# UCirKitBreadboardTop.net
KiCad netlist of a schematic drawn in EAGLE
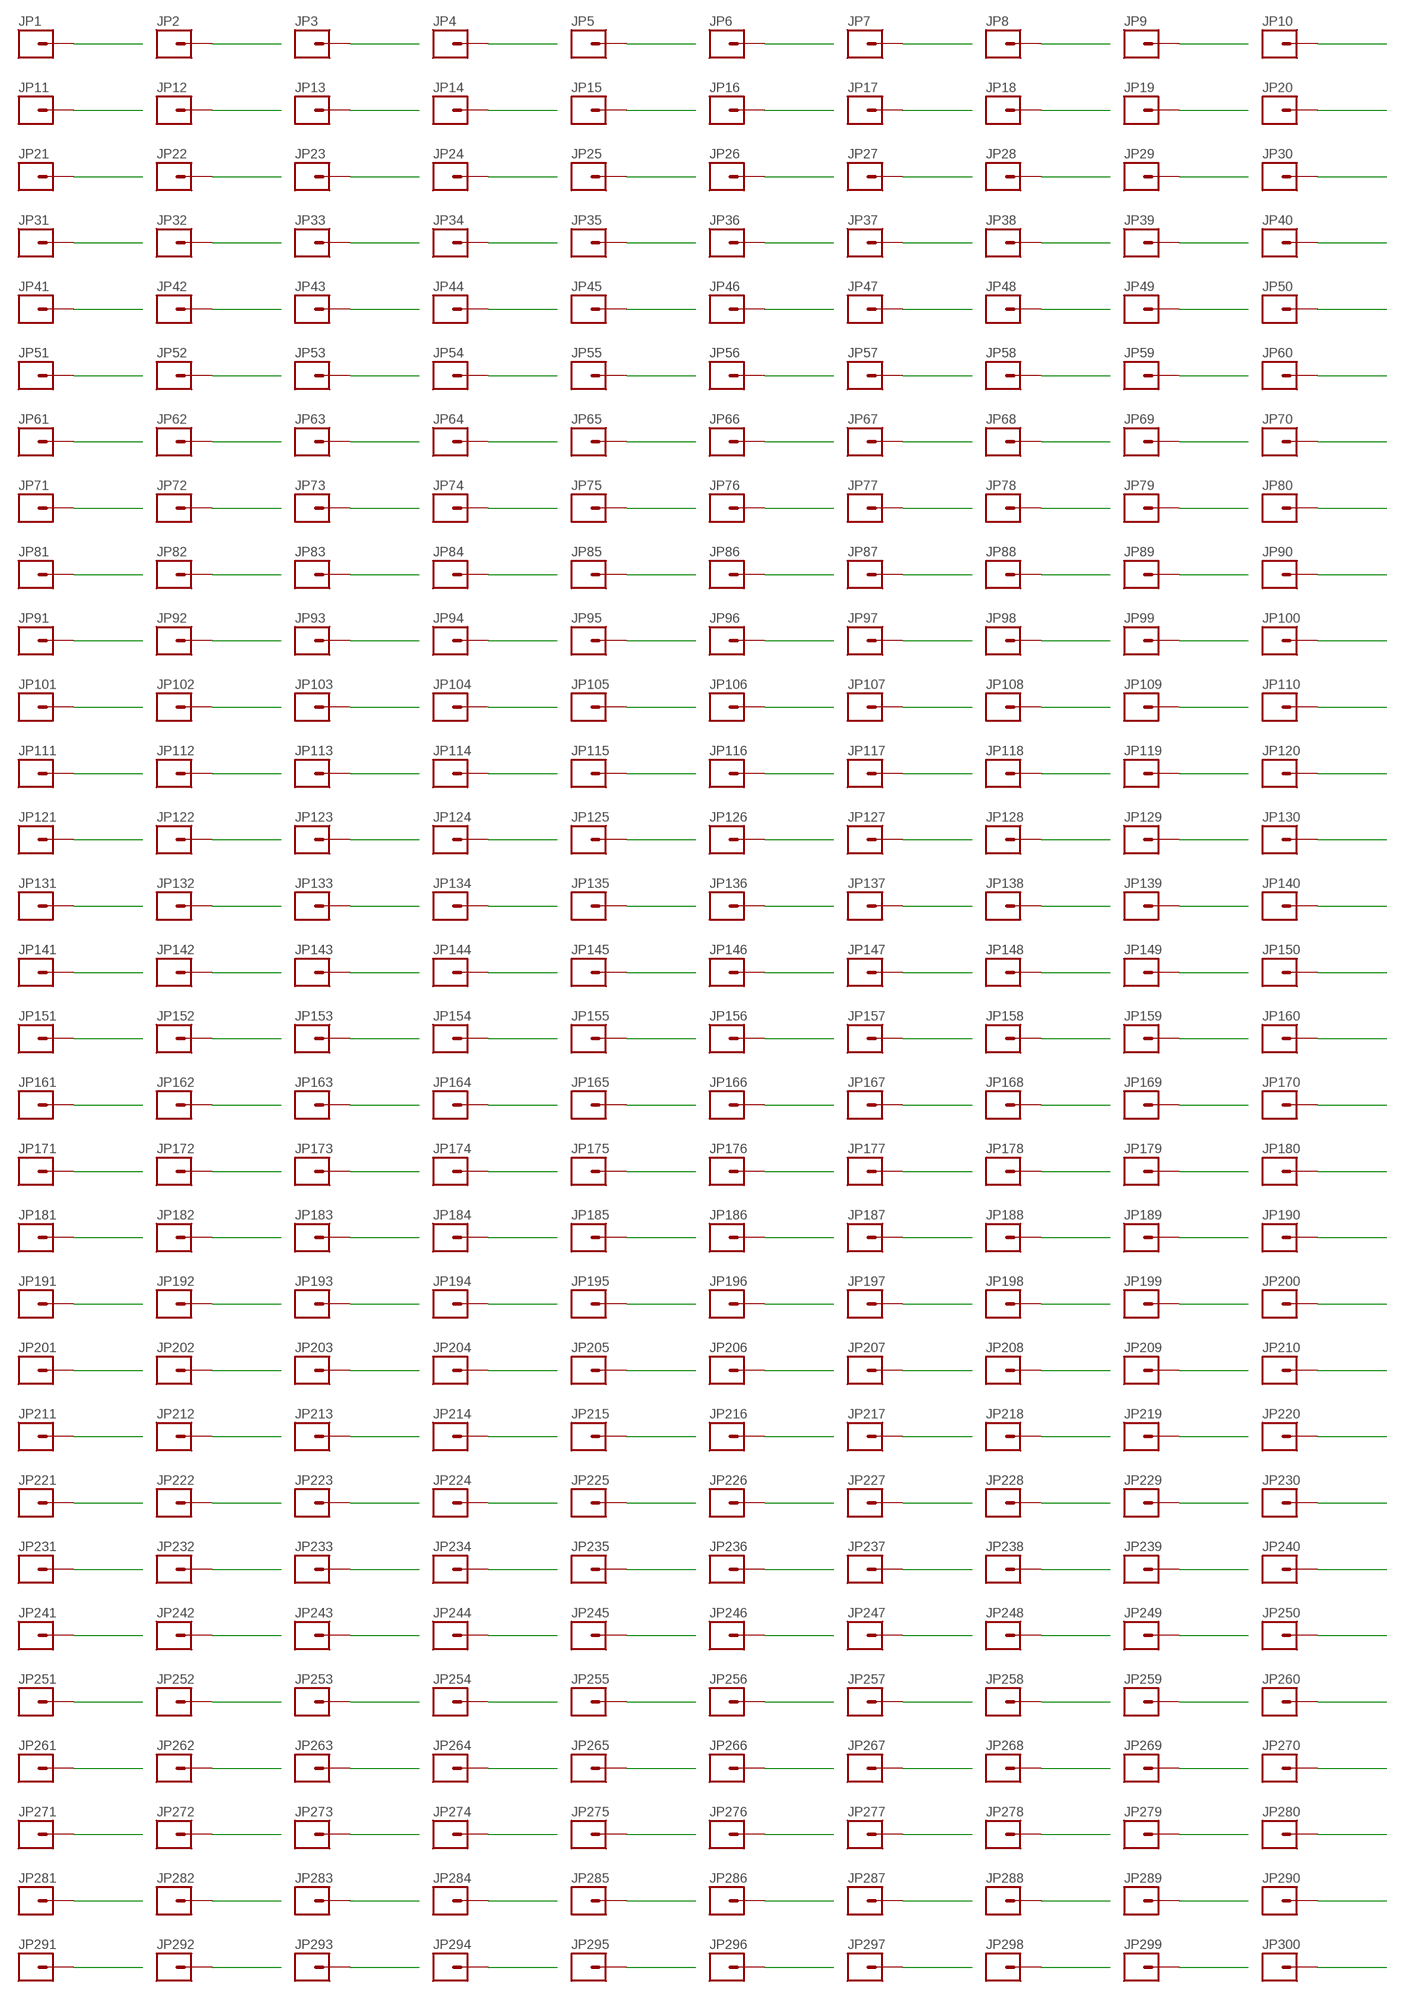
[diagram p0: schematic, sheet 1, part 1 of 2]
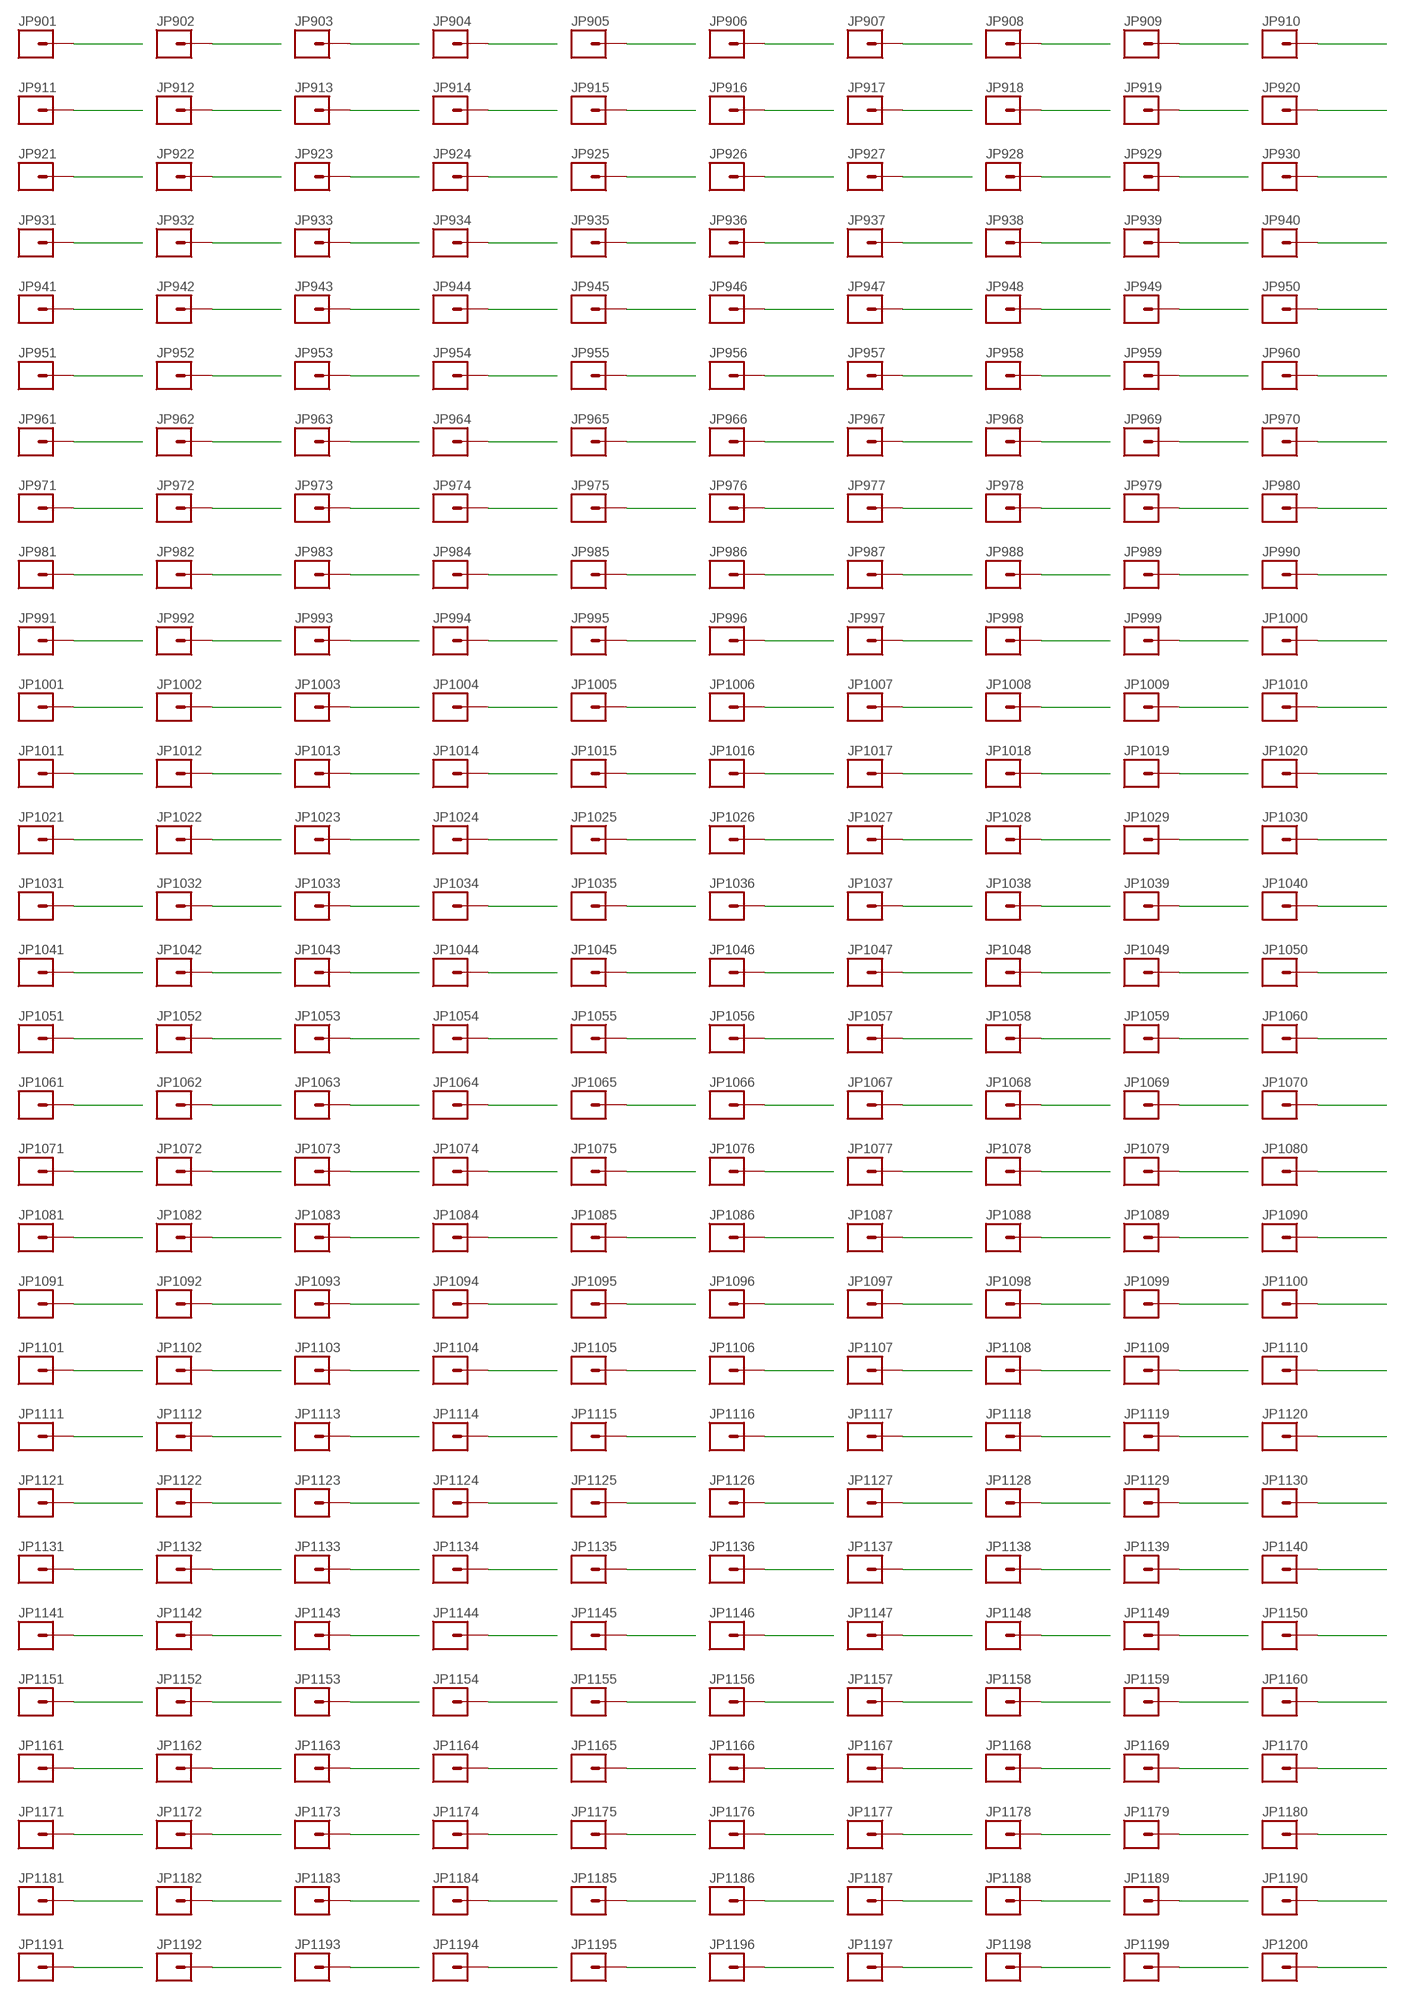
[diagram p1: schematic, sheet 1, part 2 of 2]

(export (version "E")
  (design (tool "Eeschema 10.0.6"))
  (components
    (comp (ref "JP1")
      (value "M01PTH_WITHOUT_TEXT")
      (footprint "eagle-import:1X01_WITHOUT_TEXT")
      (libsource (lib "eagle-import") (part "M01PTH_WITHOUT_TEXT"))
    )
    (comp (ref "JP2")
      (value "M01PTH_WITHOUT_TEXT")
      (footprint "eagle-import:1X01_WITHOUT_TEXT")
      (libsource (lib "eagle-import") (part "M01PTH_WITHOUT_TEXT"))
    )
    (comp (ref "JP3")
      (value "M01PTH_WITHOUT_TEXT")
      (footprint "eagle-import:1X01_WITHOUT_TEXT")
      (libsource (lib "eagle-import") (part "M01PTH_WITHOUT_TEXT"))
    )
    (comp (ref "JP4")
      (value "M01PTH_WITHOUT_TEXT")
      (footprint "eagle-import:1X01_WITHOUT_TEXT")
      (libsource (lib "eagle-import") (part "M01PTH_WITHOUT_TEXT"))
    )
    (comp (ref "JP5")
      (value "M01PTH_WITHOUT_TEXT")
      (footprint "eagle-import:1X01_WITHOUT_TEXT")
      (libsource (lib "eagle-import") (part "M01PTH_WITHOUT_TEXT"))
    )
    (comp (ref "JP6")
      (value "M01PTH_WITHOUT_TEXT")
      (footprint "eagle-import:1X01_WITHOUT_TEXT")
      (libsource (lib "eagle-import") (part "M01PTH_WITHOUT_TEXT"))
    )
    (comp (ref "JP7")
      (value "M01PTH_WITHOUT_TEXT")
      (footprint "eagle-import:1X01_WITHOUT_TEXT")
      (libsource (lib "eagle-import") (part "M01PTH_WITHOUT_TEXT"))
    )
    (comp (ref "JP8")
      (value "M01PTH_WITHOUT_TEXT")
      (footprint "eagle-import:1X01_WITHOUT_TEXT")
      (libsource (lib "eagle-import") (part "M01PTH_WITHOUT_TEXT"))
    )
    (comp (ref "JP9")
      (value "M01PTH_WITHOUT_TEXT")
      (footprint "eagle-import:1X01_WITHOUT_TEXT")
      (libsource (lib "eagle-import") (part "M01PTH_WITHOUT_TEXT"))
    )
    (comp (ref "JP10")
      (value "M01PTH_WITHOUT_TEXT")
      (footprint "eagle-import:1X01_WITHOUT_TEXT")
      (libsource (lib "eagle-import") (part "M01PTH_WITHOUT_TEXT"))
    )
    (comp (ref "JP11")
      (value "M01PTH_WITHOUT_TEXT")
      (footprint "eagle-import:1X01_WITHOUT_TEXT")
      (libsource (lib "eagle-import") (part "M01PTH_WITHOUT_TEXT"))
    )
    (comp (ref "JP12")
      (value "M01PTH_WITHOUT_TEXT")
      (footprint "eagle-import:1X01_WITHOUT_TEXT")
      (libsource (lib "eagle-import") (part "M01PTH_WITHOUT_TEXT"))
    )
    (comp (ref "JP13")
      (value "M01PTH_WITHOUT_TEXT")
      (footprint "eagle-import:1X01_WITHOUT_TEXT")
      (libsource (lib "eagle-import") (part "M01PTH_WITHOUT_TEXT"))
    )
    (comp (ref "JP14")
      (value "M01PTH_WITHOUT_TEXT")
      (footprint "eagle-import:1X01_WITHOUT_TEXT")
      (libsource (lib "eagle-import") (part "M01PTH_WITHOUT_TEXT"))
    )
    (comp (ref "JP15")
      (value "M01PTH_WITHOUT_TEXT")
      (footprint "eagle-import:1X01_WITHOUT_TEXT")
      (libsource (lib "eagle-import") (part "M01PTH_WITHOUT_TEXT"))
    )
    (comp (ref "JP16")
      (value "M01PTH_WITHOUT_TEXT")
      (footprint "eagle-import:1X01_WITHOUT_TEXT")
      (libsource (lib "eagle-import") (part "M01PTH_WITHOUT_TEXT"))
    )
    (comp (ref "JP17")
      (value "M01PTH_WITHOUT_TEXT")
      (footprint "eagle-import:1X01_WITHOUT_TEXT")
      (libsource (lib "eagle-import") (part "M01PTH_WITHOUT_TEXT"))
    )
    (comp (ref "JP18")
      (value "M01PTH_WITHOUT_TEXT")
      (footprint "eagle-import:1X01_WITHOUT_TEXT")
      (libsource (lib "eagle-import") (part "M01PTH_WITHOUT_TEXT"))
    )
    (comp (ref "JP19")
      (value "M01PTH_WITHOUT_TEXT")
      (footprint "eagle-import:1X01_WITHOUT_TEXT")
      (libsource (lib "eagle-import") (part "M01PTH_WITHOUT_TEXT"))
    )
    (comp (ref "JP20")
      (value "M01PTH_WITHOUT_TEXT")
      (footprint "eagle-import:1X01_WITHOUT_TEXT")
      (libsource (lib "eagle-import") (part "M01PTH_WITHOUT_TEXT"))
    )
    (comp (ref "JP21")
      (value "M01PTH_WITHOUT_TEXT")
      (footprint "eagle-import:1X01_WITHOUT_TEXT")
      (libsource (lib "eagle-import") (part "M01PTH_WITHOUT_TEXT"))
    )
    (comp (ref "JP22")
      (value "M01PTH_WITHOUT_TEXT")
      (footprint "eagle-import:1X01_WITHOUT_TEXT")
      (libsource (lib "eagle-import") (part "M01PTH_WITHOUT_TEXT"))
    )
    (comp (ref "JP23")
      (value "M01PTH_WITHOUT_TEXT")
      (footprint "eagle-import:1X01_WITHOUT_TEXT")
      (libsource (lib "eagle-import") (part "M01PTH_WITHOUT_TEXT"))
    )
    (comp (ref "JP24")
      (value "M01PTH_WITHOUT_TEXT")
      (footprint "eagle-import:1X01_WITHOUT_TEXT")
      (libsource (lib "eagle-import") (part "M01PTH_WITHOUT_TEXT"))
    )
    (comp (ref "JP25")
      (value "M01PTH_WITHOUT_TEXT")
      (footprint "eagle-import:1X01_WITHOUT_TEXT")
      (libsource (lib "eagle-import") (part "M01PTH_WITHOUT_TEXT"))
    )
    (comp (ref "JP26")
      (value "M01PTH_WITHOUT_TEXT")
      (footprint "eagle-import:1X01_WITHOUT_TEXT")
      (libsource (lib "eagle-import") (part "M01PTH_WITHOUT_TEXT"))
    )
    (comp (ref "JP27")
      (value "M01PTH_WITHOUT_TEXT")
      (footprint "eagle-import:1X01_WITHOUT_TEXT")
      (libsource (lib "eagle-import") (part "M01PTH_WITHOUT_TEXT"))
    )
    (comp (ref "JP28")
      (value "M01PTH_WITHOUT_TEXT")
      (footprint "eagle-import:1X01_WITHOUT_TEXT")
      (libsource (lib "eagle-import") (part "M01PTH_WITHOUT_TEXT"))
    )
    (comp (ref "JP29")
      (value "M01PTH_WITHOUT_TEXT")
      (footprint "eagle-import:1X01_WITHOUT_TEXT")
      (libsource (lib "eagle-import") (part "M01PTH_WITHOUT_TEXT"))
    )
    (comp (ref "JP30")
      (value "M01PTH_WITHOUT_TEXT")
      (footprint "eagle-import:1X01_WITHOUT_TEXT")
      (libsource (lib "eagle-import") (part "M01PTH_WITHOUT_TEXT"))
    )
    (comp (ref "JP31")
      (value "M01PTH_WITHOUT_TEXT")
      (footprint "eagle-import:1X01_WITHOUT_TEXT")
      (libsource (lib "eagle-import") (part "M01PTH_WITHOUT_TEXT"))
    )
    (comp (ref "JP32")
      (value "M01PTH_WITHOUT_TEXT")
      (footprint "eagle-import:1X01_WITHOUT_TEXT")
      (libsource (lib "eagle-import") (part "M01PTH_WITHOUT_TEXT"))
    )
    (comp (ref "JP33")
      (value "M01PTH_WITHOUT_TEXT")
      (footprint "eagle-import:1X01_WITHOUT_TEXT")
      (libsource (lib "eagle-import") (part "M01PTH_WITHOUT_TEXT"))
    )
    (comp (ref "JP34")
      (value "M01PTH_WITHOUT_TEXT")
      (footprint "eagle-import:1X01_WITHOUT_TEXT")
      (libsource (lib "eagle-import") (part "M01PTH_WITHOUT_TEXT"))
    )
    (comp (ref "JP35")
      (value "M01PTH_WITHOUT_TEXT")
      (footprint "eagle-import:1X01_WITHOUT_TEXT")
      (libsource (lib "eagle-import") (part "M01PTH_WITHOUT_TEXT"))
    )
    (comp (ref "JP36")
      (value "M01PTH_WITHOUT_TEXT")
      (footprint "eagle-import:1X01_WITHOUT_TEXT")
      (libsource (lib "eagle-import") (part "M01PTH_WITHOUT_TEXT"))
    )
    (comp (ref "JP37")
      (value "M01PTH_WITHOUT_TEXT")
      (footprint "eagle-import:1X01_WITHOUT_TEXT")
      (libsource (lib "eagle-import") (part "M01PTH_WITHOUT_TEXT"))
    )
    (comp (ref "JP38")
      (value "M01PTH_WITHOUT_TEXT")
      (footprint "eagle-import:1X01_WITHOUT_TEXT")
      (libsource (lib "eagle-import") (part "M01PTH_WITHOUT_TEXT"))
    )
    (comp (ref "JP39")
      (value "M01PTH_WITHOUT_TEXT")
      (footprint "eagle-import:1X01_WITHOUT_TEXT")
      (libsource (lib "eagle-import") (part "M01PTH_WITHOUT_TEXT"))
    )
    (comp (ref "JP40")
      (value "M01PTH_WITHOUT_TEXT")
      (footprint "eagle-import:1X01_WITHOUT_TEXT")
      (libsource (lib "eagle-import") (part "M01PTH_WITHOUT_TEXT"))
    )
    (comp (ref "JP41")
      (value "M01PTH_WITHOUT_TEXT")
      (footprint "eagle-import:1X01_WITHOUT_TEXT")
      (libsource (lib "eagle-import") (part "M01PTH_WITHOUT_TEXT"))
    )
    (comp (ref "JP42")
      (value "M01PTH_WITHOUT_TEXT")
      (footprint "eagle-import:1X01_WITHOUT_TEXT")
      (libsource (lib "eagle-import") (part "M01PTH_WITHOUT_TEXT"))
    )
    (comp (ref "JP43")
      (value "M01PTH_WITHOUT_TEXT")
      (footprint "eagle-import:1X01_WITHOUT_TEXT")
      (libsource (lib "eagle-import") (part "M01PTH_WITHOUT_TEXT"))
    )
    (comp (ref "JP44")
      (value "M01PTH_WITHOUT_TEXT")
      (footprint "eagle-import:1X01_WITHOUT_TEXT")
      (libsource (lib "eagle-import") (part "M01PTH_WITHOUT_TEXT"))
    )
    (comp (ref "JP45")
      (value "M01PTH_WITHOUT_TEXT")
      (footprint "eagle-import:1X01_WITHOUT_TEXT")
      (libsource (lib "eagle-import") (part "M01PTH_WITHOUT_TEXT"))
    )
    (comp (ref "JP46")
      (value "M01PTH_WITHOUT_TEXT")
      (footprint "eagle-import:1X01_WITHOUT_TEXT")
      (libsource (lib "eagle-import") (part "M01PTH_WITHOUT_TEXT"))
    )
    (comp (ref "JP47")
      (value "M01PTH_WITHOUT_TEXT")
      (footprint "eagle-import:1X01_WITHOUT_TEXT")
      (libsource (lib "eagle-import") (part "M01PTH_WITHOUT_TEXT"))
    )
    (comp (ref "JP48")
      (value "M01PTH_WITHOUT_TEXT")
      (footprint "eagle-import:1X01_WITHOUT_TEXT")
      (libsource (lib "eagle-import") (part "M01PTH_WITHOUT_TEXT"))
    )
    (comp (ref "JP49")
      (value "M01PTH_WITHOUT_TEXT")
      (footprint "eagle-import:1X01_WITHOUT_TEXT")
      (libsource (lib "eagle-import") (part "M01PTH_WITHOUT_TEXT"))
    )
    (comp (ref "JP50")
      (value "M01PTH_WITHOUT_TEXT")
      (footprint "eagle-import:1X01_WITHOUT_TEXT")
      (libsource (lib "eagle-import") (part "M01PTH_WITHOUT_TEXT"))
    )
    (comp (ref "JP51")
      (value "M01PTH_WITHOUT_TEXT")
      (footprint "eagle-import:1X01_WITHOUT_TEXT")
      (libsource (lib "eagle-import") (part "M01PTH_WITHOUT_TEXT"))
    )
    (comp (ref "JP52")
      (value "M01PTH_WITHOUT_TEXT")
      (footprint "eagle-import:1X01_WITHOUT_TEXT")
      (libsource (lib "eagle-import") (part "M01PTH_WITHOUT_TEXT"))
    )
    (comp (ref "JP53")
      (value "M01PTH_WITHOUT_TEXT")
      (footprint "eagle-import:1X01_WITHOUT_TEXT")
      (libsource (lib "eagle-import") (part "M01PTH_WITHOUT_TEXT"))
    )
    (comp (ref "JP54")
      (value "M01PTH_WITHOUT_TEXT")
      (footprint "eagle-import:1X01_WITHOUT_TEXT")
      (libsource (lib "eagle-import") (part "M01PTH_WITHOUT_TEXT"))
    )
    (comp (ref "JP55")
      (value "M01PTH_WITHOUT_TEXT")
      (footprint "eagle-import:1X01_WITHOUT_TEXT")
      (libsource (lib "eagle-import") (part "M01PTH_WITHOUT_TEXT"))
    )
    (comp (ref "JP56")
      (value "M01PTH_WITHOUT_TEXT")
      (footprint "eagle-import:1X01_WITHOUT_TEXT")
      (libsource (lib "eagle-import") (part "M01PTH_WITHOUT_TEXT"))
    )
    (comp (ref "JP57")
      (value "M01PTH_WITHOUT_TEXT")
      (footprint "eagle-import:1X01_WITHOUT_TEXT")
      (libsource (lib "eagle-import") (part "M01PTH_WITHOUT_TEXT"))
    )
    (comp (ref "JP58")
      (value "M01PTH_WITHOUT_TEXT")
      (footprint "eagle-import:1X01_WITHOUT_TEXT")
      (libsource (lib "eagle-import") (part "M01PTH_WITHOUT_TEXT"))
    )
    (comp (ref "JP59")
      (value "M01PTH_WITHOUT_TEXT")
      (footprint "eagle-import:1X01_WITHOUT_TEXT")
      (libsource (lib "eagle-import") (part "M01PTH_WITHOUT_TEXT"))
    )
    (comp (ref "JP60")
      (value "M01PTH_WITHOUT_TEXT")
      (footprint "eagle-import:1X01_WITHOUT_TEXT")
      (libsource (lib "eagle-import") (part "M01PTH_WITHOUT_TEXT"))
    )
    (comp (ref "JP61")
      (value "M01PTH_WITHOUT_TEXT")
      (footprint "eagle-import:1X01_WITHOUT_TEXT")
      (libsource (lib "eagle-import") (part "M01PTH_WITHOUT_TEXT"))
    )
    (comp (ref "JP62")
      (value "M01PTH_WITHOUT_TEXT")
      (footprint "eagle-import:1X01_WITHOUT_TEXT")
      (libsource (lib "eagle-import") (part "M01PTH_WITHOUT_TEXT"))
    )
    (comp (ref "JP63")
      (value "M01PTH_WITHOUT_TEXT")
      (footprint "eagle-import:1X01_WITHOUT_TEXT")
      (libsource (lib "eagle-import") (part "M01PTH_WITHOUT_TEXT"))
    )
    (comp (ref "JP64")
      (value "M01PTH_WITHOUT_TEXT")
      (footprint "eagle-import:1X01_WITHOUT_TEXT")
      (libsource (lib "eagle-import") (part "M01PTH_WITHOUT_TEXT"))
    )
    (comp (ref "JP65")
      (value "M01PTH_WITHOUT_TEXT")
      (footprint "eagle-import:1X01_WITHOUT_TEXT")
      (libsource (lib "eagle-import") (part "M01PTH_WITHOUT_TEXT"))
    )
    (comp (ref "JP66")
      (value "M01PTH_WITHOUT_TEXT")
      (footprint "eagle-import:1X01_WITHOUT_TEXT")
      (libsource (lib "eagle-import") (part "M01PTH_WITHOUT_TEXT"))
    )
    (comp (ref "JP67")
      (value "M01PTH_WITHOUT_TEXT")
      (footprint "eagle-import:1X01_WITHOUT_TEXT")
      (libsource (lib "eagle-import") (part "M01PTH_WITHOUT_TEXT"))
    )
    (comp (ref "JP68")
      (value "M01PTH_WITHOUT_TEXT")
      (footprint "eagle-import:1X01_WITHOUT_TEXT")
      (libsource (lib "eagle-import") (part "M01PTH_WITHOUT_TEXT"))
    )
    (comp (ref "JP69")
      (value "M01PTH_WITHOUT_TEXT")
      (footprint "eagle-import:1X01_WITHOUT_TEXT")
      (libsource (lib "eagle-import") (part "M01PTH_WITHOUT_TEXT"))
    )
    (comp (ref "JP70")
      (value "M01PTH_WITHOUT_TEXT")
      (footprint "eagle-import:1X01_WITHOUT_TEXT")
      (libsource (lib "eagle-import") (part "M01PTH_WITHOUT_TEXT"))
    )
    (comp (ref "JP71")
      (value "M01PTH_WITHOUT_TEXT")
      (footprint "eagle-import:1X01_WITHOUT_TEXT")
      (libsource (lib "eagle-import") (part "M01PTH_WITHOUT_TEXT"))
    )
    (comp (ref "JP72")
      (value "M01PTH_WITHOUT_TEXT")
      (footprint "eagle-import:1X01_WITHOUT_TEXT")
      (libsource (lib "eagle-import") (part "M01PTH_WITHOUT_TEXT"))
    )
    (comp (ref "JP73")
      (value "M01PTH_WITHOUT_TEXT")
      (footprint "eagle-import:1X01_WITHOUT_TEXT")
      (libsource (lib "eagle-import") (part "M01PTH_WITHOUT_TEXT"))
    )
    (comp (ref "JP74")
      (value "M01PTH_WITHOUT_TEXT")
      (footprint "eagle-import:1X01_WITHOUT_TEXT")
      (libsource (lib "eagle-import") (part "M01PTH_WITHOUT_TEXT"))
    )
    (comp (ref "JP75")
      (value "M01PTH_WITHOUT_TEXT")
      (footprint "eagle-import:1X01_WITHOUT_TEXT")
      (libsource (lib "eagle-import") (part "M01PTH_WITHOUT_TEXT"))
    )
    (comp (ref "JP76")
      (value "M01PTH_WITHOUT_TEXT")
      (footprint "eagle-import:1X01_WITHOUT_TEXT")
      (libsource (lib "eagle-import") (part "M01PTH_WITHOUT_TEXT"))
    )
    (comp (ref "JP77")
      (value "M01PTH_WITHOUT_TEXT")
      (footprint "eagle-import:1X01_WITHOUT_TEXT")
      (libsource (lib "eagle-import") (part "M01PTH_WITHOUT_TEXT"))
    )
    (comp (ref "JP78")
      (value "M01PTH_WITHOUT_TEXT")
      (footprint "eagle-import:1X01_WITHOUT_TEXT")
      (libsource (lib "eagle-import") (part "M01PTH_WITHOUT_TEXT"))
    )
    (comp (ref "JP79")
      (value "M01PTH_WITHOUT_TEXT")
      (footprint "eagle-import:1X01_WITHOUT_TEXT")
      (libsource (lib "eagle-import") (part "M01PTH_WITHOUT_TEXT"))
    )
    (comp (ref "JP80")
      (value "M01PTH_WITHOUT_TEXT")
      (footprint "eagle-import:1X01_WITHOUT_TEXT")
      (libsource (lib "eagle-import") (part "M01PTH_WITHOUT_TEXT"))
    )
    (comp (ref "JP81")
      (value "M01PTH_WITHOUT_TEXT")
      (footprint "eagle-import:1X01_WITHOUT_TEXT")
      (libsource (lib "eagle-import") (part "M01PTH_WITHOUT_TEXT"))
    )
    (comp (ref "JP82")
      (value "M01PTH_WITHOUT_TEXT")
      (footprint "eagle-import:1X01_WITHOUT_TEXT")
      (libsource (lib "eagle-import") (part "M01PTH_WITHOUT_TEXT"))
    )
    (comp (ref "JP83")
      (value "M01PTH_WITHOUT_TEXT")
      (footprint "eagle-import:1X01_WITHOUT_TEXT")
      (libsource (lib "eagle-import") (part "M01PTH_WITHOUT_TEXT"))
    )
    (comp (ref "JP84")
      (value "M01PTH_WITHOUT_TEXT")
      (footprint "eagle-import:1X01_WITHOUT_TEXT")
      (libsource (lib "eagle-import") (part "M01PTH_WITHOUT_TEXT"))
    )
    (comp (ref "JP85")
      (value "M01PTH_WITHOUT_TEXT")
      (footprint "eagle-import:1X01_WITHOUT_TEXT")
      (libsource (lib "eagle-import") (part "M01PTH_WITHOUT_TEXT"))
    )
    (comp (ref "JP86")
      (value "M01PTH_WITHOUT_TEXT")
      (footprint "eagle-import:1X01_WITHOUT_TEXT")
      (libsource (lib "eagle-import") (part "M01PTH_WITHOUT_TEXT"))
    )
    (comp (ref "JP87")
      (value "M01PTH_WITHOUT_TEXT")
      (footprint "eagle-import:1X01_WITHOUT_TEXT")
      (libsource (lib "eagle-import") (part "M01PTH_WITHOUT_TEXT"))
    )
    (comp (ref "JP88")
      (value "M01PTH_WITHOUT_TEXT")
      (footprint "eagle-import:1X01_WITHOUT_TEXT")
      (libsource (lib "eagle-import") (part "M01PTH_WITHOUT_TEXT"))
    )
    (comp (ref "JP89")
      (value "M01PTH_WITHOUT_TEXT")
      (footprint "eagle-import:1X01_WITHOUT_TEXT")
      (libsource (lib "eagle-import") (part "M01PTH_WITHOUT_TEXT"))
    )
    (comp (ref "JP90")
      (value "M01PTH_WITHOUT_TEXT")
      (footprint "eagle-import:1X01_WITHOUT_TEXT")
      (libsource (lib "eagle-import") (part "M01PTH_WITHOUT_TEXT"))
    )
    (comp (ref "JP91")
      (value "M01PTH_WITHOUT_TEXT")
      (footprint "eagle-import:1X01_WITHOUT_TEXT")
      (libsource (lib "eagle-import") (part "M01PTH_WITHOUT_TEXT"))
    )
    (comp (ref "JP92")
      (value "M01PTH_WITHOUT_TEXT")
      (footprint "eagle-import:1X01_WITHOUT_TEXT")
      (libsource (lib "eagle-import") (part "M01PTH_WITHOUT_TEXT"))
    )
    (comp (ref "JP93")
      (value "M01PTH_WITHOUT_TEXT")
      (footprint "eagle-import:1X01_WITHOUT_TEXT")
      (libsource (lib "eagle-import") (part "M01PTH_WITHOUT_TEXT"))
    )
    (comp (ref "JP94")
      (value "M01PTH_WITHOUT_TEXT")
      (footprint "eagle-import:1X01_WITHOUT_TEXT")
      (libsource (lib "eagle-import") (part "M01PTH_WITHOUT_TEXT"))
    )
    (comp (ref "JP95")
      (value "M01PTH_WITHOUT_TEXT")
      (footprint "eagle-import:1X01_WITHOUT_TEXT")
      (libsource (lib "eagle-import") (part "M01PTH_WITHOUT_TEXT"))
    )
    (comp (ref "JP96")
      (value "M01PTH_WITHOUT_TEXT")
      (footprint "eagle-import:1X01_WITHOUT_TEXT")
      (libsource (lib "eagle-import") (part "M01PTH_WITHOUT_TEXT"))
    )
    (comp (ref "JP97")
      (value "M01PTH_WITHOUT_TEXT")
      (footprint "eagle-import:1X01_WITHOUT_TEXT")
      (libsource (lib "eagle-import") (part "M01PTH_WITHOUT_TEXT"))
    )
    (comp (ref "JP98")
      (value "M01PTH_WITHOUT_TEXT")
      (footprint "eagle-import:1X01_WITHOUT_TEXT")
      (libsource (lib "eagle-import") (part "M01PTH_WITHOUT_TEXT"))
    )
    (comp (ref "JP99")
      (value "M01PTH_WITHOUT_TEXT")
      (footprint "eagle-import:1X01_WITHOUT_TEXT")
      (libsource (lib "eagle-import") (part "M01PTH_WITHOUT_TEXT"))
    )
    (comp (ref "JP100")
      (value "M01PTH_WITHOUT_TEXT")
      (footprint "eagle-import:1X01_WITHOUT_TEXT")
      (libsource (lib "eagle-import") (part "M01PTH_WITHOUT_TEXT"))
    )
    (comp (ref "JP101")
      (value "M01PTH_WITHOUT_TEXT")
      (footprint "eagle-import:1X01_WITHOUT_TEXT")
      (libsource (lib "eagle-import") (part "M01PTH_WITHOUT_TEXT"))
    )
    (comp (ref "JP102")
      (value "M01PTH_WITHOUT_TEXT")
      (footprint "eagle-import:1X01_WITHOUT_TEXT")
      (libsource (lib "eagle-import") (part "M01PTH_WITHOUT_TEXT"))
    )
    (comp (ref "JP103")
      (value "M01PTH_WITHOUT_TEXT")
      (footprint "eagle-import:1X01_WITHOUT_TEXT")
      (libsource (lib "eagle-import") (part "M01PTH_WITHOUT_TEXT"))
    )
    (comp (ref "JP104")
      (value "M01PTH_WITHOUT_TEXT")
      (footprint "eagle-import:1X01_WITHOUT_TEXT")
      (libsource (lib "eagle-import") (part "M01PTH_WITHOUT_TEXT"))
    )
    (comp (ref "JP105")
      (value "M01PTH_WITHOUT_TEXT")
      (footprint "eagle-import:1X01_WITHOUT_TEXT")
      (libsource (lib "eagle-import") (part "M01PTH_WITHOUT_TEXT"))
    )
    (comp (ref "JP106")
      (value "M01PTH_WITHOUT_TEXT")
      (footprint "eagle-import:1X01_WITHOUT_TEXT")
      (libsource (lib "eagle-import") (part "M01PTH_WITHOUT_TEXT"))
    )
    (comp (ref "JP107")
      (value "M01PTH_WITHOUT_TEXT")
      (footprint "eagle-import:1X01_WITHOUT_TEXT")
      (libsource (lib "eagle-import") (part "M01PTH_WITHOUT_TEXT"))
    )
    (comp (ref "JP108")
      (value "M01PTH_WITHOUT_TEXT")
      (footprint "eagle-import:1X01_WITHOUT_TEXT")
      (libsource (lib "eagle-import") (part "M01PTH_WITHOUT_TEXT"))
    )
    (comp (ref "JP109")
      (value "M01PTH_WITHOUT_TEXT")
      (footprint "eagle-import:1X01_WITHOUT_TEXT")
      (libsource (lib "eagle-import") (part "M01PTH_WITHOUT_TEXT"))
    )
    (comp (ref "JP110")
      (value "M01PTH_WITHOUT_TEXT")
      (footprint "eagle-import:1X01_WITHOUT_TEXT")
      (libsource (lib "eagle-import") (part "M01PTH_WITHOUT_TEXT"))
    )
    (comp (ref "JP111")
      (value "M01PTH_WITHOUT_TEXT")
      (footprint "eagle-import:1X01_WITHOUT_TEXT")
      (libsource (lib "eagle-import") (part "M01PTH_WITHOUT_TEXT"))
    )
    (comp (ref "JP112")
      (value "M01PTH_WITHOUT_TEXT")
      (footprint "eagle-import:1X01_WITHOUT_TEXT")
      (libsource (lib "eagle-import") (part "M01PTH_WITHOUT_TEXT"))
    )
    (comp (ref "JP113")
      (value "M01PTH_WITHOUT_TEXT")
      (footprint "eagle-import:1X01_WITHOUT_TEXT")
      (libsource (lib "eagle-import") (part "M01PTH_WITHOUT_TEXT"))
    )
    (comp (ref "JP114")
      (value "M01PTH_WITHOUT_TEXT")
      (footprint "eagle-import:1X01_WITHOUT_TEXT")
      (libsource (lib "eagle-import") (part "M01PTH_WITHOUT_TEXT"))
    )
    (comp (ref "JP115")
      (value "M01PTH_WITHOUT_TEXT")
      (footprint "eagle-import:1X01_WITHOUT_TEXT")
      (libsource (lib "eagle-import") (part "M01PTH_WITHOUT_TEXT"))
    )
    (comp (ref "JP116")
      (value "M01PTH_WITHOUT_TEXT")
      (footprint "eagle-import:1X01_WITHOUT_TEXT")
      (libsource (lib "eagle-import") (part "M01PTH_WITHOUT_TEXT"))
    )
    (comp (ref "JP117")
      (value "M01PTH_WITHOUT_TEXT")
      (footprint "eagle-import:1X01_WITHOUT_TEXT")
      (libsource (lib "eagle-import") (part "M01PTH_WITHOUT_TEXT"))
    )
    (comp (ref "JP118")
      (value "M01PTH_WITHOUT_TEXT")
      (footprint "eagle-import:1X01_WITHOUT_TEXT")
      (libsource (lib "eagle-import") (part "M01PTH_WITHOUT_TEXT"))
    )
    (comp (ref "JP119")
      (value "M01PTH_WITHOUT_TEXT")
      (footprint "eagle-import:1X01_WITHOUT_TEXT")
      (libsource (lib "eagle-import") (part "M01PTH_WITHOUT_TEXT"))
    )
    (comp (ref "JP120")
      (value "M01PTH_WITHOUT_TEXT")
      (footprint "eagle-import:1X01_WITHOUT_TEXT")
      (libsource (lib "eagle-import") (part "M01PTH_WITHOUT_TEXT"))
    )
    (comp (ref "JP121")
      (value "M01PTH_WITHOUT_TEXT")
      (footprint "eagle-import:1X01_WITHOUT_TEXT")
      (libsource (lib "eagle-import") (part "M01PTH_WITHOUT_TEXT"))
    )
    (comp (ref "JP122")
      (value "M01PTH_WITHOUT_TEXT")
      (footprint "eagle-import:1X01_WITHOUT_TEXT")
      (libsource (lib "eagle-import") (part "M01PTH_WITHOUT_TEXT"))
    )
    (comp (ref "JP123")
      (value "M01PTH_WITHOUT_TEXT")
      (footprint "eagle-import:1X01_WITHOUT_TEXT")
      (libsource (lib "eagle-import") (part "M01PTH_WITHOUT_TEXT"))
    )
    (comp (ref "JP124")
      (value "M01PTH_WITHOUT_TEXT")
      (footprint "eagle-import:1X01_WITHOUT_TEXT")
      (libsource (lib "eagle-import") (part "M01PTH_WITHOUT_TEXT"))
    )
    (comp (ref "JP125")
      (value "M01PTH_WITHOUT_TEXT")
      (footprint "eagle-import:1X01_WITHOUT_TEXT")
      (libsource (lib "eagle-import") (part "M01PTH_WITHOUT_TEXT"))
    )
    (comp (ref "JP126")
      (value "M01PTH_WITHOUT_TEXT")
      (footprint "eagle-import:1X01_WITHOUT_TEXT")
      (libsource (lib "eagle-import") (part "M01PTH_WITHOUT_TEXT"))
    )
    (comp (ref "JP127")
      (value "M01PTH_WITHOUT_TEXT")
      (footprint "eagle-import:1X01_WITHOUT_TEXT")
      (libsource (lib "eagle-import") (part "M01PTH_WITHOUT_TEXT"))
    )
    (comp (ref "JP128")
      (value "M01PTH_WITHOUT_TEXT")
      (footprint "eagle-import:1X01_WITHOUT_TEXT")
      (libsource (lib "eagle-import") (part "M01PTH_WITHOUT_TEXT"))
    )
    (comp (ref "JP129")
      (value "M01PTH_WITHOUT_TEXT")
      (footprint "eagle-import:1X01_WITHOUT_TEXT")
      (libsource (lib "eagle-import") (part "M01PTH_WITHOUT_TEXT"))
    )
    (comp (ref "JP130")
      (value "M01PTH_WITHOUT_TEXT")
      (footprint "eagle-import:1X01_WITHOUT_TEXT")
      (libsource (lib "eagle-import") (part "M01PTH_WITHOUT_TEXT"))
    )
    (comp (ref "JP131")
      (value "M01PTH_WITHOUT_TEXT")
      (footprint "eagle-import:1X01_WITHOUT_TEXT")
      (libsource (lib "eagle-import") (part "M01PTH_WITHOUT_TEXT"))
    )
    (comp (ref "JP132")
      (value "M01PTH_WITHOUT_TEXT")
      (footprint "eagle-import:1X01_WITHOUT_TEXT")
      (libsource (lib "eagle-import") (part "M01PTH_WITHOUT_TEXT"))
    )
    (comp (ref "JP133")
      (value "M01PTH_WITHOUT_TEXT")
      (footprint "eagle-import:1X01_WITHOUT_TEXT")
      (libsource (lib "eagle-import") (part "M01PTH_WITHOUT_TEXT"))
    )
    (comp (ref "JP134")
      (value "M01PTH_WITHOUT_TEXT")
      (footprint "eagle-import:1X01_WITHOUT_TEXT")
      (libsource (lib "eagle-import") (part "M01PTH_WITHOUT_TEXT"))
    )
    (comp (ref "JP135")
      (value "M01PTH_WITHOUT_TEXT")
      (footprint "eagle-import:1X01_WITHOUT_TEXT")
      (libsource (lib "eagle-import") (part "M01PTH_WITHOUT_TEXT"))
    )
    (comp (ref "JP136")
      (value "M01PTH_WITHOUT_TEXT")
      (footprint "eagle-import:1X01_WITHOUT_TEXT")
      (libsource (lib "eagle-import") (part "M01PTH_WITHOUT_TEXT"))
    )
    (comp (ref "JP137")
      (value "M01PTH_WITHOUT_TEXT")
      (footprint "eagle-import:1X01_WITHOUT_TEXT")
      (libsource (lib "eagle-import") (part "M01PTH_WITHOUT_TEXT"))
    )
    (comp (ref "JP138")
      (value "M01PTH_WITHOUT_TEXT")
      (footprint "eagle-import:1X01_WITHOUT_TEXT")
      (libsource (lib "eagle-import") (part "M01PTH_WITHOUT_TEXT"))
    )
    (comp (ref "JP139")
      (value "M01PTH_WITHOUT_TEXT")
      (footprint "eagle-import:1X01_WITHOUT_TEXT")
      (libsource (lib "eagle-import") (part "M01PTH_WITHOUT_TEXT"))
    )
    (comp (ref "JP140")
      (value "M01PTH_WITHOUT_TEXT")
      (footprint "eagle-import:1X01_WITHOUT_TEXT")
      (libsource (lib "eagle-import") (part "M01PTH_WITHOUT_TEXT"))
    )
    (comp (ref "JP141")
      (value "M01PTH_WITHOUT_TEXT")
      (footprint "eagle-import:1X01_WITHOUT_TEXT")
      (libsource (lib "eagle-import") (part "M01PTH_WITHOUT_TEXT"))
    )
    (comp (ref "JP142")
      (value "M01PTH_WITHOUT_TEXT")
      (footprint "eagle-import:1X01_WITHOUT_TEXT")
      (libsource (lib "eagle-import") (part "M01PTH_WITHOUT_TEXT"))
    )
    (comp (ref "JP143")
      (value "M01PTH_WITHOUT_TEXT")
      (footprint "eagle-import:1X01_WITHOUT_TEXT")
      (libsource (lib "eagle-import") (part "M01PTH_WITHOUT_TEXT"))
    )
    (comp (ref "JP144")
      (value "M01PTH_WITHOUT_TEXT")
      (footprint "eagle-import:1X01_WITHOUT_TEXT")
      (libsource (lib "eagle-import") (part "M01PTH_WITHOUT_TEXT"))
    )
    (comp (ref "JP145")
      (value "M01PTH_WITHOUT_TEXT")
      (footprint "eagle-import:1X01_WITHOUT_TEXT")
      (libsource (lib "eagle-import") (part "M01PTH_WITHOUT_TEXT"))
    )
    (comp (ref "JP146")
      (value "M01PTH_WITHOUT_TEXT")
      (footprint "eagle-import:1X01_WITHOUT_TEXT")
      (libsource (lib "eagle-import") (part "M01PTH_WITHOUT_TEXT"))
    )
    (comp (ref "JP147")
      (value "M01PTH_WITHOUT_TEXT")
      (footprint "eagle-import:1X01_WITHOUT_TEXT")
      (libsource (lib "eagle-import") (part "M01PTH_WITHOUT_TEXT"))
    )
    (comp (ref "JP148")
      (value "M01PTH_WITHOUT_TEXT")
      (footprint "eagle-import:1X01_WITHOUT_TEXT")
      (libsource (lib "eagle-import") (part "M01PTH_WITHOUT_TEXT"))
    )
    (comp (ref "JP149")
      (value "M01PTH_WITHOUT_TEXT")
      (footprint "eagle-import:1X01_WITHOUT_TEXT")
      (libsource (lib "eagle-import") (part "M01PTH_WITHOUT_TEXT"))
    )
    (comp (ref "JP150")
      (value "M01PTH_WITHOUT_TEXT")
      (footprint "eagle-import:1X01_WITHOUT_TEXT")
      (libsource (lib "eagle-import") (part "M01PTH_WITHOUT_TEXT"))
    )
    (comp (ref "JP151")
      (value "M01PTH_WITHOUT_TEXT")
      (footprint "eagle-import:1X01_WITHOUT_TEXT")
      (libsource (lib "eagle-import") (part "M01PTH_WITHOUT_TEXT"))
    )
    (comp (ref "JP152")
      (value "M01PTH_WITHOUT_TEXT")
      (footprint "eagle-import:1X01_WITHOUT_TEXT")
      (libsource (lib "eagle-import") (part "M01PTH_WITHOUT_TEXT"))
    )
    (comp (ref "JP153")
      (value "M01PTH_WITHOUT_TEXT")
      (footprint "eagle-import:1X01_WITHOUT_TEXT")
      (libsource (lib "eagle-import") (part "M01PTH_WITHOUT_TEXT"))
    )
    (comp (ref "JP154")
      (value "M01PTH_WITHOUT_TEXT")
      (footprint "eagle-import:1X01_WITHOUT_TEXT")
      (libsource (lib "eagle-import") (part "M01PTH_WITHOUT_TEXT"))
    )
    (comp (ref "JP155")
      (value "M01PTH_WITHOUT_TEXT")
      (footprint "eagle-import:1X01_WITHOUT_TEXT")
      (libsource (lib "eagle-import") (part "M01PTH_WITHOUT_TEXT"))
    )
    (comp (ref "JP156")
      (value "M01PTH_WITHOUT_TEXT")
      (footprint "eagle-import:1X01_WITHOUT_TEXT")
      (libsource (lib "eagle-import") (part "M01PTH_WITHOUT_TEXT"))
    )
    (comp (ref "JP157")
      (value "M01PTH_WITHOUT_TEXT")
      (footprint "eagle-import:1X01_WITHOUT_TEXT")
      (libsource (lib "eagle-import") (part "M01PTH_WITHOUT_TEXT"))
    )
    (comp (ref "JP158")
      (value "M01PTH_WITHOUT_TEXT")
      (footprint "eagle-import:1X01_WITHOUT_TEXT")
      (libsource (lib "eagle-import") (part "M01PTH_WITHOUT_TEXT"))
    )
    (comp (ref "JP159")
      (value "M01PTH_WITHOUT_TEXT")
      (footprint "eagle-import:1X01_WITHOUT_TEXT")
      (libsource (lib "eagle-import") (part "M01PTH_WITHOUT_TEXT"))
    )
    (comp (ref "JP160")
      (value "M01PTH_WITHOUT_TEXT")
      (footprint "eagle-import:1X01_WITHOUT_TEXT")
      (libsource (lib "eagle-import") (part "M01PTH_WITHOUT_TEXT"))
    )
    (comp (ref "JP161")
      (value "M01PTH_WITHOUT_TEXT")
      (footprint "eagle-import:1X01_WITHOUT_TEXT")
      (libsource (lib "eagle-import") (part "M01PTH_WITHOUT_TEXT"))
    )
    (comp (ref "JP162")
      (value "M01PTH_WITHOUT_TEXT")
      (footprint "eagle-import:1X01_WITHOUT_TEXT")
      (libsource (lib "eagle-import") (part "M01PTH_WITHOUT_TEXT"))
    )
    (comp (ref "JP163")
      (value "M01PTH_WITHOUT_TEXT")
      (footprint "eagle-import:1X01_WITHOUT_TEXT")
      (libsource (lib "eagle-import") (part "M01PTH_WITHOUT_TEXT"))
    )
    (comp (ref "JP164")
      (value "M01PTH_WITHOUT_TEXT")
      (footprint "eagle-import:1X01_WITHOUT_TEXT")
      (libsource (lib "eagle-import") (part "M01PTH_WITHOUT_TEXT"))
    )
    (comp (ref "JP165")
      (value "M01PTH_WITHOUT_TEXT")
      (footprint "eagle-import:1X01_WITHOUT_TEXT")
      (libsource (lib "eagle-import") (part "M01PTH_WITHOUT_TEXT"))
    )
    (comp (ref "JP166")
      (value "M01PTH_WITHOUT_TEXT")
      (footprint "eagle-import:1X01_WITHOUT_TEXT")
      (libsource (lib "eagle-import") (part "M01PTH_WITHOUT_TEXT"))
    )
    (comp (ref "JP167")
      (value "M01PTH_WITHOUT_TEXT")
      (footprint "eagle-import:1X01_WITHOUT_TEXT")
      (libsource (lib "eagle-import") (part "M01PTH_WITHOUT_TEXT"))
    )
    (comp (ref "JP168")
      (value "M01PTH_WITHOUT_TEXT")
      (footprint "eagle-import:1X01_WITHOUT_TEXT")
      (libsource (lib "eagle-import") (part "M01PTH_WITHOUT_TEXT"))
    )
    (comp (ref "JP169")
      (value "M01PTH_WITHOUT_TEXT")
      (footprint "eagle-import:1X01_WITHOUT_TEXT")
      (libsource (lib "eagle-import") (part "M01PTH_WITHOUT_TEXT"))
    )
    (comp (ref "JP170")
      (value "M01PTH_WITHOUT_TEXT")
      (footprint "eagle-import:1X01_WITHOUT_TEXT")
      (libsource (lib "eagle-import") (part "M01PTH_WITHOUT_TEXT"))
    )
    (comp (ref "JP171")
      (value "M01PTH_WITHOUT_TEXT")
      (footprint "eagle-import:1X01_WITHOUT_TEXT")
      (libsource (lib "eagle-import") (part "M01PTH_WITHOUT_TEXT"))
    )
    (comp (ref "JP172")
      (value "M01PTH_WITHOUT_TEXT")
      (footprint "eagle-import:1X01_WITHOUT_TEXT")
      (libsource (lib "eagle-import") (part "M01PTH_WITHOUT_TEXT"))
    )
    (comp (ref "JP173")
      (value "M01PTH_WITHOUT_TEXT")
      (footprint "eagle-import:1X01_WITHOUT_TEXT")
      (libsource (lib "eagle-import") (part "M01PTH_WITHOUT_TEXT"))
    )
    (comp (ref "JP174")
      (value "M01PTH_WITHOUT_TEXT")
      (footprint "eagle-import:1X01_WITHOUT_TEXT")
      (libsource (lib "eagle-import") (part "M01PTH_WITHOUT_TEXT"))
    )
    (comp (ref "JP175")
      (value "M01PTH_WITHOUT_TEXT")
      (footprint "eagle-import:1X01_WITHOUT_TEXT")
      (libsource (lib "eagle-import") (part "M01PTH_WITHOUT_TEXT"))
    )
    (comp (ref "JP176")
      (value "M01PTH_WITHOUT_TEXT")
      (footprint "eagle-import:1X01_WITHOUT_TEXT")
      (libsource (lib "eagle-import") (part "M01PTH_WITHOUT_TEXT"))
    )
    (comp (ref "JP177")
      (value "M01PTH_WITHOUT_TEXT")
      (footprint "eagle-import:1X01_WITHOUT_TEXT")
      (libsource (lib "eagle-import") (part "M01PTH_WITHOUT_TEXT"))
    )
    (comp (ref "JP178")
      (value "M01PTH_WITHOUT_TEXT")
      (footprint "eagle-import:1X01_WITHOUT_TEXT")
      (libsource (lib "eagle-import") (part "M01PTH_WITHOUT_TEXT"))
    )
    (comp (ref "JP179")
      (value "M01PTH_WITHOUT_TEXT")
      (footprint "eagle-import:1X01_WITHOUT_TEXT")
      (libsource (lib "eagle-import") (part "M01PTH_WITHOUT_TEXT"))
    )
    (comp (ref "JP180")
      (value "M01PTH_WITHOUT_TEXT")
      (footprint "eagle-import:1X01_WITHOUT_TEXT")
      (libsource (lib "eagle-import") (part "M01PTH_WITHOUT_TEXT"))
    )
    (comp (ref "JP181")
      (value "M01PTH_WITHOUT_TEXT")
      (footprint "eagle-import:1X01_WITHOUT_TEXT")
      (libsource (lib "eagle-import") (part "M01PTH_WITHOUT_TEXT"))
    )
    (comp (ref "JP182")
      (value "M01PTH_WITHOUT_TEXT")
      (footprint "eagle-import:1X01_WITHOUT_TEXT")
      (libsource (lib "eagle-import") (part "M01PTH_WITHOUT_TEXT"))
    )
    (comp (ref "JP183")
      (value "M01PTH_WITHOUT_TEXT")
      (footprint "eagle-import:1X01_WITHOUT_TEXT")
      (libsource (lib "eagle-import") (part "M01PTH_WITHOUT_TEXT"))
    )
    (comp (ref "JP184")
      (value "M01PTH_WITHOUT_TEXT")
      (footprint "eagle-import:1X01_WITHOUT_TEXT")
      (libsource (lib "eagle-import") (part "M01PTH_WITHOUT_TEXT"))
    )
    (comp (ref "JP185")
      (value "M01PTH_WITHOUT_TEXT")
      (footprint "eagle-import:1X01_WITHOUT_TEXT")
      (libsource (lib "eagle-import") (part "M01PTH_WITHOUT_TEXT"))
    )
    (comp (ref "JP186")
      (value "M01PTH_WITHOUT_TEXT")
      (footprint "eagle-import:1X01_WITHOUT_TEXT")
      (libsource (lib "eagle-import") (part "M01PTH_WITHOUT_TEXT"))
    )
    (comp (ref "JP187")
      (value "M01PTH_WITHOUT_TEXT")
      (footprint "eagle-import:1X01_WITHOUT_TEXT")
      (libsource (lib "eagle-import") (part "M01PTH_WITHOUT_TEXT"))
    )
    (comp (ref "JP188")
      (value "M01PTH_WITHOUT_TEXT")
      (footprint "eagle-import:1X01_WITHOUT_TEXT")
      (libsource (lib "eagle-import") (part "M01PTH_WITHOUT_TEXT"))
    )
    (comp (ref "JP189")
      (value "M01PTH_WITHOUT_TEXT")
      (footprint "eagle-import:1X01_WITHOUT_TEXT")
      (libsource (lib "eagle-import") (part "M01PTH_WITHOUT_TEXT"))
    )
    (comp (ref "JP190")
      (value "M01PTH_WITHOUT_TEXT")
      (footprint "eagle-import:1X01_WITHOUT_TEXT")
      (libsource (lib "eagle-import") (part "M01PTH_WITHOUT_TEXT"))
    )
    (comp (ref "JP191")
      (value "M01PTH_WITHOUT_TEXT")
      (footprint "eagle-import:1X01_WITHOUT_TEXT")
      (libsource (lib "eagle-import") (part "M01PTH_WITHOUT_TEXT"))
    )
    (comp (ref "JP192")
      (value "M01PTH_WITHOUT_TEXT")
      (footprint "eagle-import:1X01_WITHOUT_TEXT")
      (libsource (lib "eagle-import") (part "M01PTH_WITHOUT_TEXT"))
    )
    (comp (ref "JP193")
      (value "M01PTH_WITHOUT_TEXT")
      (footprint "eagle-import:1X01_WITHOUT_TEXT")
      (libsource (lib "eagle-import") (part "M01PTH_WITHOUT_TEXT"))
    )
    (comp (ref "JP194")
      (value "M01PTH_WITHOUT_TEXT")
      (footprint "eagle-import:1X01_WITHOUT_TEXT")
      (libsource (lib "eagle-import") (part "M01PTH_WITHOUT_TEXT"))
    )
    (comp (ref "JP195")
      (value "M01PTH_WITHOUT_TEXT")
      (footprint "eagle-import:1X01_WITHOUT_TEXT")
      (libsource (lib "eagle-import") (part "M01PTH_WITHOUT_TEXT"))
    )
    (comp (ref "JP196")
      (value "M01PTH_WITHOUT_TEXT")
      (footprint "eagle-import:1X01_WITHOUT_TEXT")
      (libsource (lib "eagle-import") (part "M01PTH_WITHOUT_TEXT"))
    )
    (comp (ref "JP197")
      (value "M01PTH_WITHOUT_TEXT")
      (footprint "eagle-import:1X01_WITHOUT_TEXT")
      (libsource (lib "eagle-import") (part "M01PTH_WITHOUT_TEXT"))
    )
    (comp (ref "JP198")
      (value "M01PTH_WITHOUT_TEXT")
      (footprint "eagle-import:1X01_WITHOUT_TEXT")
      (libsource (lib "eagle-import") (part "M01PTH_WITHOUT_TEXT"))
    )
    (comp (ref "JP199")
      (value "M01PTH_WITHOUT_TEXT")
      (footprint "eagle-import:1X01_WITHOUT_TEXT")
      (libsource (lib "eagle-import") (part "M01PTH_WITHOUT_TEXT"))
    )
    (comp (ref "JP200")
      (value "M01PTH_WITHOUT_TEXT")
      (footprint "eagle-import:1X01_WITHOUT_TEXT")
      (libsource (lib "eagle-import") (part "M01PTH_WITHOUT_TEXT"))
    )
    (comp (ref "JP201")
      (value "M01PTH_WITHOUT_TEXT")
      (footprint "eagle-import:1X01_WITHOUT_TEXT")
      (libsource (lib "eagle-import") (part "M01PTH_WITHOUT_TEXT"))
    )
    (comp (ref "JP202")
      (value "M01PTH_WITHOUT_TEXT")
      (footprint "eagle-import:1X01_WITHOUT_TEXT")
      (libsource (lib "eagle-import") (part "M01PTH_WITHOUT_TEXT"))
    )
    (comp (ref "JP203")
      (value "M01PTH_WITHOUT_TEXT")
      (footprint "eagle-import:1X01_WITHOUT_TEXT")
      (libsource (lib "eagle-import") (part "M01PTH_WITHOUT_TEXT"))
    )
    (comp (ref "JP204")
      (value "M01PTH_WITHOUT_TEXT")
      (footprint "eagle-import:1X01_WITHOUT_TEXT")
      (libsource (lib "eagle-import") (part "M01PTH_WITHOUT_TEXT"))
    )
    (comp (ref "JP205")
      (value "M01PTH_WITHOUT_TEXT")
      (footprint "eagle-import:1X01_WITHOUT_TEXT")
      (libsource (lib "eagle-import") (part "M01PTH_WITHOUT_TEXT"))
    )
    (comp (ref "JP206")
      (value "M01PTH_WITHOUT_TEXT")
      (footprint "eagle-import:1X01_WITHOUT_TEXT")
      (libsource (lib "eagle-import") (part "M01PTH_WITHOUT_TEXT"))
    )
    (comp (ref "JP207")
      (value "M01PTH_WITHOUT_TEXT")
      (footprint "eagle-import:1X01_WITHOUT_TEXT")
      (libsource (lib "eagle-import") (part "M01PTH_WITHOUT_TEXT"))
    )
    (comp (ref "JP208")
      (value "M01PTH_WITHOUT_TEXT")
      (footprint "eagle-import:1X01_WITHOUT_TEXT")
      (libsource (lib "eagle-import") (part "M01PTH_WITHOUT_TEXT"))
    )
    (comp (ref "JP209")
      (value "M01PTH_WITHOUT_TEXT")
      (footprint "eagle-import:1X01_WITHOUT_TEXT")
      (libsource (lib "eagle-import") (part "M01PTH_WITHOUT_TEXT"))
    )
    (comp (ref "JP210")
      (value "M01PTH_WITHOUT_TEXT")
      (footprint "eagle-import:1X01_WITHOUT_TEXT")
      (libsource (lib "eagle-import") (part "M01PTH_WITHOUT_TEXT"))
    )
    (comp (ref "JP211")
      (value "M01PTH_WITHOUT_TEXT")
      (footprint "eagle-import:1X01_WITHOUT_TEXT")
      (libsource (lib "eagle-import") (part "M01PTH_WITHOUT_TEXT"))
    )
    (comp (ref "JP212")
      (value "M01PTH_WITHOUT_TEXT")
      (footprint "eagle-import:1X01_WITHOUT_TEXT")
      (libsource (lib "eagle-import") (part "M01PTH_WITHOUT_TEXT"))
    )
    (comp (ref "JP213")
      (value "M01PTH_WITHOUT_TEXT")
      (footprint "eagle-import:1X01_WITHOUT_TEXT")
      (libsource (lib "eagle-import") (part "M01PTH_WITHOUT_TEXT"))
    )
    (comp (ref "JP214")
      (value "M01PTH_WITHOUT_TEXT")
      (footprint "eagle-import:1X01_WITHOUT_TEXT")
      (libsource (lib "eagle-import") (part "M01PTH_WITHOUT_TEXT"))
    )
    (comp (ref "JP215")
      (value "M01PTH_WITHOUT_TEXT")
      (footprint "eagle-import:1X01_WITHOUT_TEXT")
      (libsource (lib "eagle-import") (part "M01PTH_WITHOUT_TEXT"))
    )
    (comp (ref "JP216")
      (value "M01PTH_WITHOUT_TEXT")
      (footprint "eagle-import:1X01_WITHOUT_TEXT")
      (libsource (lib "eagle-import") (part "M01PTH_WITHOUT_TEXT"))
    )
    (comp (ref "JP217")
      (value "M01PTH_WITHOUT_TEXT")
      (footprint "eagle-import:1X01_WITHOUT_TEXT")
      (libsource (lib "eagle-import") (part "M01PTH_WITHOUT_TEXT"))
    )
    (comp (ref "JP218")
      (value "M01PTH_WITHOUT_TEXT")
      (footprint "eagle-import:1X01_WITHOUT_TEXT")
      (libsource (lib "eagle-import") (part "M01PTH_WITHOUT_TEXT"))
    )
    (comp (ref "JP219")
      (value "M01PTH_WITHOUT_TEXT")
      (footprint "eagle-import:1X01_WITHOUT_TEXT")
      (libsource (lib "eagle-import") (part "M01PTH_WITHOUT_TEXT"))
    )
    (comp (ref "JP220")
      (value "M01PTH_WITHOUT_TEXT")
      (footprint "eagle-import:1X01_WITHOUT_TEXT")
      (libsource (lib "eagle-import") (part "M01PTH_WITHOUT_TEXT"))
    )
    (comp (ref "JP221")
      (value "M01PTH_WITHOUT_TEXT")
      (footprint "eagle-import:1X01_WITHOUT_TEXT")
      (libsource (lib "eagle-import") (part "M01PTH_WITHOUT_TEXT"))
    )
    (comp (ref "JP222")
      (value "M01PTH_WITHOUT_TEXT")
      (footprint "eagle-import:1X01_WITHOUT_TEXT")
      (libsource (lib "eagle-import") (part "M01PTH_WITHOUT_TEXT"))
    )
    (comp (ref "JP223")
      (value "M01PTH_WITHOUT_TEXT")
      (footprint "eagle-import:1X01_WITHOUT_TEXT")
      (libsource (lib "eagle-import") (part "M01PTH_WITHOUT_TEXT"))
    )
    (comp (ref "JP224")
      (value "M01PTH_WITHOUT_TEXT")
      (footprint "eagle-import:1X01_WITHOUT_TEXT")
      (libsource (lib "eagle-import") (part "M01PTH_WITHOUT_TEXT"))
    )
    (comp (ref "JP225")
      (value "M01PTH_WITHOUT_TEXT")
      (footprint "eagle-import:1X01_WITHOUT_TEXT")
      (libsource (lib "eagle-import") (part "M01PTH_WITHOUT_TEXT"))
    )
    (comp (ref "JP226")
      (value "M01PTH_WITHOUT_TEXT")
      (footprint "eagle-import:1X01_WITHOUT_TEXT")
      (libsource (lib "eagle-import") (part "M01PTH_WITHOUT_TEXT"))
    )
    (comp (ref "JP227")
      (value "M01PTH_WITHOUT_TEXT")
      (footprint "eagle-import:1X01_WITHOUT_TEXT")
      (libsource (lib "eagle-import") (part "M01PTH_WITHOUT_TEXT"))
    )
    (comp (ref "JP228")
      (value "M01PTH_WITHOUT_TEXT")
      (footprint "eagle-import:1X01_WITHOUT_TEXT")
      (libsource (lib "eagle-import") (part "M01PTH_WITHOUT_TEXT"))
    )
    (comp (ref "JP229")
      (value "M01PTH_WITHOUT_TEXT")
      (footprint "eagle-import:1X01_WITHOUT_TEXT")
      (libsource (lib "eagle-import") (part "M01PTH_WITHOUT_TEXT"))
    )
    (comp (ref "JP230")
      (value "M01PTH_WITHOUT_TEXT")
      (footprint "eagle-import:1X01_WITHOUT_TEXT")
      (libsource (lib "eagle-import") (part "M01PTH_WITHOUT_TEXT"))
    )
    (comp (ref "JP231")
      (value "M01PTH_WITHOUT_TEXT")
      (footprint "eagle-import:1X01_WITHOUT_TEXT")
      (libsource (lib "eagle-import") (part "M01PTH_WITHOUT_TEXT"))
    )
    (comp (ref "JP232")
      (value "M01PTH_WITHOUT_TEXT")
      (footprint "eagle-import:1X01_WITHOUT_TEXT")
      (libsource (lib "eagle-import") (part "M01PTH_WITHOUT_TEXT"))
    )
    (comp (ref "JP233")
      (value "M01PTH_WITHOUT_TEXT")
      (footprint "eagle-import:1X01_WITHOUT_TEXT")
      (libsource (lib "eagle-import") (part "M01PTH_WITHOUT_TEXT"))
    )
    (comp (ref "JP234")
      (value "M01PTH_WITHOUT_TEXT")
      (footprint "eagle-import:1X01_WITHOUT_TEXT")
      (libsource (lib "eagle-import") (part "M01PTH_WITHOUT_TEXT"))
    )
    (comp (ref "JP235")
      (value "M01PTH_WITHOUT_TEXT")
      (footprint "eagle-import:1X01_WITHOUT_TEXT")
      (libsource (lib "eagle-import") (part "M01PTH_WITHOUT_TEXT"))
    )
    (comp (ref "JP236")
      (value "M01PTH_WITHOUT_TEXT")
      (footprint "eagle-import:1X01_WITHOUT_TEXT")
      (libsource (lib "eagle-import") (part "M01PTH_WITHOUT_TEXT"))
    )
    (comp (ref "JP237")
      (value "M01PTH_WITHOUT_TEXT")
      (footprint "eagle-import:1X01_WITHOUT_TEXT")
      (libsource (lib "eagle-import") (part "M01PTH_WITHOUT_TEXT"))
    )
    (comp (ref "JP238")
      (value "M01PTH_WITHOUT_TEXT")
      (footprint "eagle-import:1X01_WITHOUT_TEXT")
      (libsource (lib "eagle-import") (part "M01PTH_WITHOUT_TEXT"))
    )
    (comp (ref "JP239")
      (value "M01PTH_WITHOUT_TEXT")
      (footprint "eagle-import:1X01_WITHOUT_TEXT")
      (libsource (lib "eagle-import") (part "M01PTH_WITHOUT_TEXT"))
    )
    (comp (ref "JP240")
      (value "M01PTH_WITHOUT_TEXT")
      (footprint "eagle-import:1X01_WITHOUT_TEXT")
      (libsource (lib "eagle-import") (part "M01PTH_WITHOUT_TEXT"))
    )
    (comp (ref "JP241")
      (value "M01PTH_WITHOUT_TEXT")
      (footprint "eagle-import:1X01_WITHOUT_TEXT")
      (libsource (lib "eagle-import") (part "M01PTH_WITHOUT_TEXT"))
    )
    (comp (ref "JP242")
      (value "M01PTH_WITHOUT_TEXT")
      (footprint "eagle-import:1X01_WITHOUT_TEXT")
      (libsource (lib "eagle-import") (part "M01PTH_WITHOUT_TEXT"))
    )
    (comp (ref "JP243")
      (value "M01PTH_WITHOUT_TEXT")
      (footprint "eagle-import:1X01_WITHOUT_TEXT")
      (libsource (lib "eagle-import") (part "M01PTH_WITHOUT_TEXT"))
    )
    (comp (ref "JP244")
      (value "M01PTH_WITHOUT_TEXT")
      (footprint "eagle-import:1X01_WITHOUT_TEXT")
      (libsource (lib "eagle-import") (part "M01PTH_WITHOUT_TEXT"))
    )
    (comp (ref "JP245")
      (value "M01PTH_WITHOUT_TEXT")
      (footprint "eagle-import:1X01_WITHOUT_TEXT")
      (libsource (lib "eagle-import") (part "M01PTH_WITHOUT_TEXT"))
    )
    (comp (ref "JP246")
      (value "M01PTH_WITHOUT_TEXT")
      (footprint "eagle-import:1X01_WITHOUT_TEXT")
      (libsource (lib "eagle-import") (part "M01PTH_WITHOUT_TEXT"))
    )
    (comp (ref "JP247")
      (value "M01PTH_WITHOUT_TEXT")
      (footprint "eagle-import:1X01_WITHOUT_TEXT")
      (libsource (lib "eagle-import") (part "M01PTH_WITHOUT_TEXT"))
    )
    (comp (ref "JP248")
      (value "M01PTH_WITHOUT_TEXT")
      (footprint "eagle-import:1X01_WITHOUT_TEXT")
      (libsource (lib "eagle-import") (part "M01PTH_WITHOUT_TEXT"))
    )
    (comp (ref "JP249")
      (value "M01PTH_WITHOUT_TEXT")
      (footprint "eagle-import:1X01_WITHOUT_TEXT")
      (libsource (lib "eagle-import") (part "M01PTH_WITHOUT_TEXT"))
    )
    (comp (ref "JP250")
      (value "M01PTH_WITHOUT_TEXT")
      (footprint "eagle-import:1X01_WITHOUT_TEXT")
      (libsource (lib "eagle-import") (part "M01PTH_WITHOUT_TEXT"))
    )
    (comp (ref "JP251")
      (value "M01PTH_WITHOUT_TEXT")
      (footprint "eagle-import:1X01_WITHOUT_TEXT")
      (libsource (lib "eagle-import") (part "M01PTH_WITHOUT_TEXT"))
    )
    (comp (ref "JP252")
      (value "M01PTH_WITHOUT_TEXT")
      (footprint "eagle-import:1X01_WITHOUT_TEXT")
      (libsource (lib "eagle-import") (part "M01PTH_WITHOUT_TEXT"))
    )
    (comp (ref "JP253")
      (value "M01PTH_WITHOUT_TEXT")
      (footprint "eagle-import:1X01_WITHOUT_TEXT")
      (libsource (lib "eagle-import") (part "M01PTH_WITHOUT_TEXT"))
    )
    (comp (ref "JP254")
      (value "M01PTH_WITHOUT_TEXT")
      (footprint "eagle-import:1X01_WITHOUT_TEXT")
      (libsource (lib "eagle-import") (part "M01PTH_WITHOUT_TEXT"))
    )
    (comp (ref "JP255")
      (value "M01PTH_WITHOUT_TEXT")
      (footprint "eagle-import:1X01_WITHOUT_TEXT")
      (libsource (lib "eagle-import") (part "M01PTH_WITHOUT_TEXT"))
    )
    (comp (ref "JP256")
      (value "M01PTH_WITHOUT_TEXT")
      (footprint "eagle-import:1X01_WITHOUT_TEXT")
      (libsource (lib "eagle-import") (part "M01PTH_WITHOUT_TEXT"))
    )
    (comp (ref "JP257")
      (value "M01PTH_WITHOUT_TEXT")
      (footprint "eagle-import:1X01_WITHOUT_TEXT")
      (libsource (lib "eagle-import") (part "M01PTH_WITHOUT_TEXT"))
    )
    (comp (ref "JP258")
      (value "M01PTH_WITHOUT_TEXT")
      (footprint "eagle-import:1X01_WITHOUT_TEXT")
      (libsource (lib "eagle-import") (part "M01PTH_WITHOUT_TEXT"))
    )
    (comp (ref "JP259")
      (value "M01PTH_WITHOUT_TEXT")
      (footprint "eagle-import:1X01_WITHOUT_TEXT")
      (libsource (lib "eagle-import") (part "M01PTH_WITHOUT_TEXT"))
    )
    (comp (ref "JP260")
      (value "M01PTH_WITHOUT_TEXT")
      (footprint "eagle-import:1X01_WITHOUT_TEXT")
      (libsource (lib "eagle-import") (part "M01PTH_WITHOUT_TEXT"))
    )
    (comp (ref "JP261")
      (value "M01PTH_WITHOUT_TEXT")
      (footprint "eagle-import:1X01_WITHOUT_TEXT")
      (libsource (lib "eagle-import") (part "M01PTH_WITHOUT_TEXT"))
    )
    (comp (ref "JP262")
      (value "M01PTH_WITHOUT_TEXT")
      (footprint "eagle-import:1X01_WITHOUT_TEXT")
      (libsource (lib "eagle-import") (part "M01PTH_WITHOUT_TEXT"))
    )
    (comp (ref "JP263")
      (value "M01PTH_WITHOUT_TEXT")
      (footprint "eagle-import:1X01_WITHOUT_TEXT")
      (libsource (lib "eagle-import") (part "M01PTH_WITHOUT_TEXT"))
    )
    (comp (ref "JP264")
      (value "M01PTH_WITHOUT_TEXT")
      (footprint "eagle-import:1X01_WITHOUT_TEXT")
      (libsource (lib "eagle-import") (part "M01PTH_WITHOUT_TEXT"))
    )
    (comp (ref "JP265")
      (value "M01PTH_WITHOUT_TEXT")
      (footprint "eagle-import:1X01_WITHOUT_TEXT")
      (libsource (lib "eagle-import") (part "M01PTH_WITHOUT_TEXT"))
    )
    (comp (ref "JP266")
      (value "M01PTH_WITHOUT_TEXT")
      (footprint "eagle-import:1X01_WITHOUT_TEXT")
      (libsource (lib "eagle-import") (part "M01PTH_WITHOUT_TEXT"))
    )
    (comp (ref "JP267")
      (value "M01PTH_WITHOUT_TEXT")
      (footprint "eagle-import:1X01_WITHOUT_TEXT")
      (libsource (lib "eagle-import") (part "M01PTH_WITHOUT_TEXT"))
    )
    (comp (ref "JP268")
      (value "M01PTH_WITHOUT_TEXT")
      (footprint "eagle-import:1X01_WITHOUT_TEXT")
      (libsource (lib "eagle-import") (part "M01PTH_WITHOUT_TEXT"))
    )
    (comp (ref "JP269")
      (value "M01PTH_WITHOUT_TEXT")
      (footprint "eagle-import:1X01_WITHOUT_TEXT")
      (libsource (lib "eagle-import") (part "M01PTH_WITHOUT_TEXT"))
    )
    (comp (ref "JP270")
      (value "M01PTH_WITHOUT_TEXT")
      (footprint "eagle-import:1X01_WITHOUT_TEXT")
      (libsource (lib "eagle-import") (part "M01PTH_WITHOUT_TEXT"))
    )
    (comp (ref "JP271")
      (value "M01PTH_WITHOUT_TEXT")
      (footprint "eagle-import:1X01_WITHOUT_TEXT")
      (libsource (lib "eagle-import") (part "M01PTH_WITHOUT_TEXT"))
    )
    (comp (ref "JP272")
      (value "M01PTH_WITHOUT_TEXT")
      (footprint "eagle-import:1X01_WITHOUT_TEXT")
      (libsource (lib "eagle-import") (part "M01PTH_WITHOUT_TEXT"))
    )
    (comp (ref "JP273")
      (value "M01PTH_WITHOUT_TEXT")
      (footprint "eagle-import:1X01_WITHOUT_TEXT")
      (libsource (lib "eagle-import") (part "M01PTH_WITHOUT_TEXT"))
    )
    (comp (ref "JP274")
      (value "M01PTH_WITHOUT_TEXT")
      (footprint "eagle-import:1X01_WITHOUT_TEXT")
      (libsource (lib "eagle-import") (part "M01PTH_WITHOUT_TEXT"))
    )
    (comp (ref "JP275")
      (value "M01PTH_WITHOUT_TEXT")
      (footprint "eagle-import:1X01_WITHOUT_TEXT")
      (libsource (lib "eagle-import") (part "M01PTH_WITHOUT_TEXT"))
    )
    (comp (ref "JP276")
      (value "M01PTH_WITHOUT_TEXT")
      (footprint "eagle-import:1X01_WITHOUT_TEXT")
      (libsource (lib "eagle-import") (part "M01PTH_WITHOUT_TEXT"))
    )
    (comp (ref "JP277")
      (value "M01PTH_WITHOUT_TEXT")
      (footprint "eagle-import:1X01_WITHOUT_TEXT")
      (libsource (lib "eagle-import") (part "M01PTH_WITHOUT_TEXT"))
    )
    (comp (ref "JP278")
      (value "M01PTH_WITHOUT_TEXT")
      (footprint "eagle-import:1X01_WITHOUT_TEXT")
      (libsource (lib "eagle-import") (part "M01PTH_WITHOUT_TEXT"))
    )
    (comp (ref "JP279")
      (value "M01PTH_WITHOUT_TEXT")
      (footprint "eagle-import:1X01_WITHOUT_TEXT")
      (libsource (lib "eagle-import") (part "M01PTH_WITHOUT_TEXT"))
    )
    (comp (ref "JP280")
      (value "M01PTH_WITHOUT_TEXT")
      (footprint "eagle-import:1X01_WITHOUT_TEXT")
      (libsource (lib "eagle-import") (part "M01PTH_WITHOUT_TEXT"))
    )
    (comp (ref "JP281")
      (value "M01PTH_WITHOUT_TEXT")
      (footprint "eagle-import:1X01_WITHOUT_TEXT")
      (libsource (lib "eagle-import") (part "M01PTH_WITHOUT_TEXT"))
    )
    (comp (ref "JP282")
      (value "M01PTH_WITHOUT_TEXT")
      (footprint "eagle-import:1X01_WITHOUT_TEXT")
      (libsource (lib "eagle-import") (part "M01PTH_WITHOUT_TEXT"))
    )
    (comp (ref "JP283")
      (value "M01PTH_WITHOUT_TEXT")
      (footprint "eagle-import:1X01_WITHOUT_TEXT")
      (libsource (lib "eagle-import") (part "M01PTH_WITHOUT_TEXT"))
    )
    (comp (ref "JP284")
      (value "M01PTH_WITHOUT_TEXT")
      (footprint "eagle-import:1X01_WITHOUT_TEXT")
      (libsource (lib "eagle-import") (part "M01PTH_WITHOUT_TEXT"))
    )
    (comp (ref "JP285")
      (value "M01PTH_WITHOUT_TEXT")
      (footprint "eagle-import:1X01_WITHOUT_TEXT")
      (libsource (lib "eagle-import") (part "M01PTH_WITHOUT_TEXT"))
    )
    (comp (ref "JP286")
      (value "M01PTH_WITHOUT_TEXT")
      (footprint "eagle-import:1X01_WITHOUT_TEXT")
      (libsource (lib "eagle-import") (part "M01PTH_WITHOUT_TEXT"))
    )
    (comp (ref "JP287")
      (value "M01PTH_WITHOUT_TEXT")
      (footprint "eagle-import:1X01_WITHOUT_TEXT")
      (libsource (lib "eagle-import") (part "M01PTH_WITHOUT_TEXT"))
    )
    (comp (ref "JP288")
      (value "M01PTH_WITHOUT_TEXT")
      (footprint "eagle-import:1X01_WITHOUT_TEXT")
      (libsource (lib "eagle-import") (part "M01PTH_WITHOUT_TEXT"))
    )
    (comp (ref "JP289")
      (value "M01PTH_WITHOUT_TEXT")
      (footprint "eagle-import:1X01_WITHOUT_TEXT")
      (libsource (lib "eagle-import") (part "M01PTH_WITHOUT_TEXT"))
    )
    (comp (ref "JP290")
      (value "M01PTH_WITHOUT_TEXT")
      (footprint "eagle-import:1X01_WITHOUT_TEXT")
      (libsource (lib "eagle-import") (part "M01PTH_WITHOUT_TEXT"))
    )
    (comp (ref "JP291")
      (value "M01PTH_WITHOUT_TEXT")
      (footprint "eagle-import:1X01_WITHOUT_TEXT")
      (libsource (lib "eagle-import") (part "M01PTH_WITHOUT_TEXT"))
    )
    (comp (ref "JP292")
      (value "M01PTH_WITHOUT_TEXT")
      (footprint "eagle-import:1X01_WITHOUT_TEXT")
      (libsource (lib "eagle-import") (part "M01PTH_WITHOUT_TEXT"))
    )
    (comp (ref "JP293")
      (value "M01PTH_WITHOUT_TEXT")
      (footprint "eagle-import:1X01_WITHOUT_TEXT")
      (libsource (lib "eagle-import") (part "M01PTH_WITHOUT_TEXT"))
    )
    (comp (ref "JP294")
      (value "M01PTH_WITHOUT_TEXT")
      (footprint "eagle-import:1X01_WITHOUT_TEXT")
      (libsource (lib "eagle-import") (part "M01PTH_WITHOUT_TEXT"))
    )
    (comp (ref "JP295")
      (value "M01PTH_WITHOUT_TEXT")
      (footprint "eagle-import:1X01_WITHOUT_TEXT")
      (libsource (lib "eagle-import") (part "M01PTH_WITHOUT_TEXT"))
    )
    (comp (ref "JP296")
      (value "M01PTH_WITHOUT_TEXT")
      (footprint "eagle-import:1X01_WITHOUT_TEXT")
      (libsource (lib "eagle-import") (part "M01PTH_WITHOUT_TEXT"))
    )
    (comp (ref "JP297")
      (value "M01PTH_WITHOUT_TEXT")
      (footprint "eagle-import:1X01_WITHOUT_TEXT")
      (libsource (lib "eagle-import") (part "M01PTH_WITHOUT_TEXT"))
    )
    (comp (ref "JP298")
      (value "M01PTH_WITHOUT_TEXT")
      (footprint "eagle-import:1X01_WITHOUT_TEXT")
      (libsource (lib "eagle-import") (part "M01PTH_WITHOUT_TEXT"))
    )
    (comp (ref "JP299")
      (value "M01PTH_WITHOUT_TEXT")
      (footprint "eagle-import:1X01_WITHOUT_TEXT")
      (libsource (lib "eagle-import") (part "M01PTH_WITHOUT_TEXT"))
    )
    (comp (ref "JP300")
      (value "M01PTH_WITHOUT_TEXT")
      (footprint "eagle-import:1X01_WITHOUT_TEXT")
      (libsource (lib "eagle-import") (part "M01PTH_WITHOUT_TEXT"))
    )
    (comp (ref "JP901")
      (value "M01PTH_SMD_1.27X0.635MM_NO_SILK")
      (footprint "eagle-import:1X01_SMD_1.27X0.635MM_NO_SILK")
      (libsource (lib "eagle-import") (part "M01PTH_SMD_1.27X0.635MM_NO_SILK"))
    )
    (comp (ref "JP902")
      (value "M01PTH_SMD_1.27X0.635MM_NO_SILK")
      (footprint "eagle-import:1X01_SMD_1.27X0.635MM_NO_SILK")
      (libsource (lib "eagle-import") (part "M01PTH_SMD_1.27X0.635MM_NO_SILK"))
    )
    (comp (ref "JP903")
      (value "M01PTH_SMD_1.27X0.635MM_NO_SILK")
      (footprint "eagle-import:1X01_SMD_1.27X0.635MM_NO_SILK")
      (libsource (lib "eagle-import") (part "M01PTH_SMD_1.27X0.635MM_NO_SILK"))
    )
    (comp (ref "JP904")
      (value "M01PTH_SMD_1.27X0.635MM_NO_SILK")
      (footprint "eagle-import:1X01_SMD_1.27X0.635MM_NO_SILK")
      (libsource (lib "eagle-import") (part "M01PTH_SMD_1.27X0.635MM_NO_SILK"))
    )
    (comp (ref "JP905")
      (value "M01PTH_SMD_1.27X0.635MM_NO_SILK")
      (footprint "eagle-import:1X01_SMD_1.27X0.635MM_NO_SILK")
      (libsource (lib "eagle-import") (part "M01PTH_SMD_1.27X0.635MM_NO_SILK"))
    )
    (comp (ref "JP906")
      (value "M01PTH_SMD_1.27X0.635MM_NO_SILK")
      (footprint "eagle-import:1X01_SMD_1.27X0.635MM_NO_SILK")
      (libsource (lib "eagle-import") (part "M01PTH_SMD_1.27X0.635MM_NO_SILK"))
    )
    (comp (ref "JP907")
      (value "M01PTH_SMD_1.27X0.635MM_NO_SILK")
      (footprint "eagle-import:1X01_SMD_1.27X0.635MM_NO_SILK")
      (libsource (lib "eagle-import") (part "M01PTH_SMD_1.27X0.635MM_NO_SILK"))
    )
    (comp (ref "JP908")
      (value "M01PTH_SMD_1.27X0.635MM_NO_SILK")
      (footprint "eagle-import:1X01_SMD_1.27X0.635MM_NO_SILK")
      (libsource (lib "eagle-import") (part "M01PTH_SMD_1.27X0.635MM_NO_SILK"))
    )
    (comp (ref "JP909")
      (value "M01PTH_SMD_1.27X0.635MM_NO_SILK")
      (footprint "eagle-import:1X01_SMD_1.27X0.635MM_NO_SILK")
      (libsource (lib "eagle-import") (part "M01PTH_SMD_1.27X0.635MM_NO_SILK"))
    )
    (comp (ref "JP910")
      (value "M01PTH_SMD_1.27X0.635MM_NO_SILK")
      (footprint "eagle-import:1X01_SMD_1.27X0.635MM_NO_SILK")
      (libsource (lib "eagle-import") (part "M01PTH_SMD_1.27X0.635MM_NO_SILK"))
    )
    (comp (ref "JP911")
      (value "M01PTH_SMD_1.27X0.635MM_NO_SILK")
      (footprint "eagle-import:1X01_SMD_1.27X0.635MM_NO_SILK")
      (libsource (lib "eagle-import") (part "M01PTH_SMD_1.27X0.635MM_NO_SILK"))
    )
    (comp (ref "JP912")
      (value "M01PTH_SMD_1.27X0.635MM_NO_SILK")
      (footprint "eagle-import:1X01_SMD_1.27X0.635MM_NO_SILK")
      (libsource (lib "eagle-import") (part "M01PTH_SMD_1.27X0.635MM_NO_SILK"))
    )
    (comp (ref "JP913")
      (value "M01PTH_SMD_1.27X0.635MM_NO_SILK")
      (footprint "eagle-import:1X01_SMD_1.27X0.635MM_NO_SILK")
      (libsource (lib "eagle-import") (part "M01PTH_SMD_1.27X0.635MM_NO_SILK"))
    )
    (comp (ref "JP914")
      (value "M01PTH_SMD_1.27X0.635MM_NO_SILK")
      (footprint "eagle-import:1X01_SMD_1.27X0.635MM_NO_SILK")
      (libsource (lib "eagle-import") (part "M01PTH_SMD_1.27X0.635MM_NO_SILK"))
    )
    (comp (ref "JP915")
      (value "M01PTH_SMD_1.27X0.635MM_NO_SILK")
      (footprint "eagle-import:1X01_SMD_1.27X0.635MM_NO_SILK")
      (libsource (lib "eagle-import") (part "M01PTH_SMD_1.27X0.635MM_NO_SILK"))
    )
    (comp (ref "JP916")
      (value "M01PTH_SMD_1.27X0.635MM_NO_SILK")
      (footprint "eagle-import:1X01_SMD_1.27X0.635MM_NO_SILK")
      (libsource (lib "eagle-import") (part "M01PTH_SMD_1.27X0.635MM_NO_SILK"))
    )
    (comp (ref "JP917")
      (value "M01PTH_SMD_1.27X0.635MM_NO_SILK")
      (footprint "eagle-import:1X01_SMD_1.27X0.635MM_NO_SILK")
      (libsource (lib "eagle-import") (part "M01PTH_SMD_1.27X0.635MM_NO_SILK"))
    )
    (comp (ref "JP918")
      (value "M01PTH_SMD_1.27X0.635MM_NO_SILK")
      (footprint "eagle-import:1X01_SMD_1.27X0.635MM_NO_SILK")
      (libsource (lib "eagle-import") (part "M01PTH_SMD_1.27X0.635MM_NO_SILK"))
    )
    (comp (ref "JP919")
      (value "M01PTH_SMD_1.27X0.635MM_NO_SILK")
      (footprint "eagle-import:1X01_SMD_1.27X0.635MM_NO_SILK")
      (libsource (lib "eagle-import") (part "M01PTH_SMD_1.27X0.635MM_NO_SILK"))
    )
    (comp (ref "JP920")
      (value "M01PTH_SMD_1.27X0.635MM_NO_SILK")
      (footprint "eagle-import:1X01_SMD_1.27X0.635MM_NO_SILK")
      (libsource (lib "eagle-import") (part "M01PTH_SMD_1.27X0.635MM_NO_SILK"))
    )
    (comp (ref "JP921")
      (value "M01PTH_SMD_1.27X0.635MM_NO_SILK")
      (footprint "eagle-import:1X01_SMD_1.27X0.635MM_NO_SILK")
      (libsource (lib "eagle-import") (part "M01PTH_SMD_1.27X0.635MM_NO_SILK"))
    )
    (comp (ref "JP922")
      (value "M01PTH_SMD_1.27X0.635MM_NO_SILK")
      (footprint "eagle-import:1X01_SMD_1.27X0.635MM_NO_SILK")
      (libsource (lib "eagle-import") (part "M01PTH_SMD_1.27X0.635MM_NO_SILK"))
    )
    (comp (ref "JP923")
      (value "M01PTH_SMD_1.27X0.635MM_NO_SILK")
      (footprint "eagle-import:1X01_SMD_1.27X0.635MM_NO_SILK")
      (libsource (lib "eagle-import") (part "M01PTH_SMD_1.27X0.635MM_NO_SILK"))
    )
    (comp (ref "JP924")
      (value "M01PTH_SMD_1.27X0.635MM_NO_SILK")
      (footprint "eagle-import:1X01_SMD_1.27X0.635MM_NO_SILK")
      (libsource (lib "eagle-import") (part "M01PTH_SMD_1.27X0.635MM_NO_SILK"))
    )
    (comp (ref "JP925")
      (value "M01PTH_SMD_1.27X0.635MM_NO_SILK")
      (footprint "eagle-import:1X01_SMD_1.27X0.635MM_NO_SILK")
      (libsource (lib "eagle-import") (part "M01PTH_SMD_1.27X0.635MM_NO_SILK"))
    )
    (comp (ref "JP926")
      (value "M01PTH_SMD_1.27X0.635MM_NO_SILK")
      (footprint "eagle-import:1X01_SMD_1.27X0.635MM_NO_SILK")
      (libsource (lib "eagle-import") (part "M01PTH_SMD_1.27X0.635MM_NO_SILK"))
    )
    (comp (ref "JP927")
      (value "M01PTH_SMD_1.27X0.635MM_NO_SILK")
      (footprint "eagle-import:1X01_SMD_1.27X0.635MM_NO_SILK")
      (libsource (lib "eagle-import") (part "M01PTH_SMD_1.27X0.635MM_NO_SILK"))
    )
    (comp (ref "JP928")
      (value "M01PTH_SMD_1.27X0.635MM_NO_SILK")
      (footprint "eagle-import:1X01_SMD_1.27X0.635MM_NO_SILK")
      (libsource (lib "eagle-import") (part "M01PTH_SMD_1.27X0.635MM_NO_SILK"))
    )
    (comp (ref "JP929")
      (value "M01PTH_SMD_1.27X0.635MM_NO_SILK")
      (footprint "eagle-import:1X01_SMD_1.27X0.635MM_NO_SILK")
      (libsource (lib "eagle-import") (part "M01PTH_SMD_1.27X0.635MM_NO_SILK"))
    )
    (comp (ref "JP930")
      (value "M01PTH_SMD_1.27X0.635MM_NO_SILK")
      (footprint "eagle-import:1X01_SMD_1.27X0.635MM_NO_SILK")
      (libsource (lib "eagle-import") (part "M01PTH_SMD_1.27X0.635MM_NO_SILK"))
    )
    (comp (ref "JP931")
      (value "M01PTH_SMD_1.27X0.635MM_NO_SILK")
      (footprint "eagle-import:1X01_SMD_1.27X0.635MM_NO_SILK")
      (libsource (lib "eagle-import") (part "M01PTH_SMD_1.27X0.635MM_NO_SILK"))
    )
    (comp (ref "JP932")
      (value "M01PTH_SMD_1.27X0.635MM_NO_SILK")
      (footprint "eagle-import:1X01_SMD_1.27X0.635MM_NO_SILK")
      (libsource (lib "eagle-import") (part "M01PTH_SMD_1.27X0.635MM_NO_SILK"))
    )
    (comp (ref "JP933")
      (value "M01PTH_SMD_1.27X0.635MM_NO_SILK")
      (footprint "eagle-import:1X01_SMD_1.27X0.635MM_NO_SILK")
      (libsource (lib "eagle-import") (part "M01PTH_SMD_1.27X0.635MM_NO_SILK"))
    )
    (comp (ref "JP934")
      (value "M01PTH_SMD_1.27X0.635MM_NO_SILK")
      (footprint "eagle-import:1X01_SMD_1.27X0.635MM_NO_SILK")
      (libsource (lib "eagle-import") (part "M01PTH_SMD_1.27X0.635MM_NO_SILK"))
    )
    (comp (ref "JP935")
      (value "M01PTH_SMD_1.27X0.635MM_NO_SILK")
      (footprint "eagle-import:1X01_SMD_1.27X0.635MM_NO_SILK")
      (libsource (lib "eagle-import") (part "M01PTH_SMD_1.27X0.635MM_NO_SILK"))
    )
    (comp (ref "JP936")
      (value "M01PTH_SMD_1.27X0.635MM_NO_SILK")
      (footprint "eagle-import:1X01_SMD_1.27X0.635MM_NO_SILK")
      (libsource (lib "eagle-import") (part "M01PTH_SMD_1.27X0.635MM_NO_SILK"))
    )
    (comp (ref "JP937")
      (value "M01PTH_SMD_1.27X0.635MM_NO_SILK")
      (footprint "eagle-import:1X01_SMD_1.27X0.635MM_NO_SILK")
      (libsource (lib "eagle-import") (part "M01PTH_SMD_1.27X0.635MM_NO_SILK"))
    )
    (comp (ref "JP938")
      (value "M01PTH_SMD_1.27X0.635MM_NO_SILK")
      (footprint "eagle-import:1X01_SMD_1.27X0.635MM_NO_SILK")
      (libsource (lib "eagle-import") (part "M01PTH_SMD_1.27X0.635MM_NO_SILK"))
    )
    (comp (ref "JP939")
      (value "M01PTH_SMD_1.27X0.635MM_NO_SILK")
      (footprint "eagle-import:1X01_SMD_1.27X0.635MM_NO_SILK")
      (libsource (lib "eagle-import") (part "M01PTH_SMD_1.27X0.635MM_NO_SILK"))
    )
    (comp (ref "JP940")
      (value "M01PTH_SMD_1.27X0.635MM_NO_SILK")
      (footprint "eagle-import:1X01_SMD_1.27X0.635MM_NO_SILK")
      (libsource (lib "eagle-import") (part "M01PTH_SMD_1.27X0.635MM_NO_SILK"))
    )
    (comp (ref "JP941")
      (value "M01PTH_SMD_1.27X0.635MM_NO_SILK")
      (footprint "eagle-import:1X01_SMD_1.27X0.635MM_NO_SILK")
      (libsource (lib "eagle-import") (part "M01PTH_SMD_1.27X0.635MM_NO_SILK"))
    )
    (comp (ref "JP942")
      (value "M01PTH_SMD_1.27X0.635MM_NO_SILK")
      (footprint "eagle-import:1X01_SMD_1.27X0.635MM_NO_SILK")
      (libsource (lib "eagle-import") (part "M01PTH_SMD_1.27X0.635MM_NO_SILK"))
    )
    (comp (ref "JP943")
      (value "M01PTH_SMD_1.27X0.635MM_NO_SILK")
      (footprint "eagle-import:1X01_SMD_1.27X0.635MM_NO_SILK")
      (libsource (lib "eagle-import") (part "M01PTH_SMD_1.27X0.635MM_NO_SILK"))
    )
    (comp (ref "JP944")
      (value "M01PTH_SMD_1.27X0.635MM_NO_SILK")
      (footprint "eagle-import:1X01_SMD_1.27X0.635MM_NO_SILK")
      (libsource (lib "eagle-import") (part "M01PTH_SMD_1.27X0.635MM_NO_SILK"))
    )
    (comp (ref "JP945")
      (value "M01PTH_SMD_1.27X0.635MM_NO_SILK")
      (footprint "eagle-import:1X01_SMD_1.27X0.635MM_NO_SILK")
      (libsource (lib "eagle-import") (part "M01PTH_SMD_1.27X0.635MM_NO_SILK"))
    )
    (comp (ref "JP946")
      (value "M01PTH_SMD_1.27X0.635MM_NO_SILK")
      (footprint "eagle-import:1X01_SMD_1.27X0.635MM_NO_SILK")
      (libsource (lib "eagle-import") (part "M01PTH_SMD_1.27X0.635MM_NO_SILK"))
    )
    (comp (ref "JP947")
      (value "M01PTH_SMD_1.27X0.635MM_NO_SILK")
      (footprint "eagle-import:1X01_SMD_1.27X0.635MM_NO_SILK")
      (libsource (lib "eagle-import") (part "M01PTH_SMD_1.27X0.635MM_NO_SILK"))
    )
    (comp (ref "JP948")
      (value "M01PTH_SMD_1.27X0.635MM_NO_SILK")
      (footprint "eagle-import:1X01_SMD_1.27X0.635MM_NO_SILK")
      (libsource (lib "eagle-import") (part "M01PTH_SMD_1.27X0.635MM_NO_SILK"))
    )
    (comp (ref "JP949")
      (value "M01PTH_SMD_1.27X0.635MM_NO_SILK")
      (footprint "eagle-import:1X01_SMD_1.27X0.635MM_NO_SILK")
      (libsource (lib "eagle-import") (part "M01PTH_SMD_1.27X0.635MM_NO_SILK"))
    )
    (comp (ref "JP950")
      (value "M01PTH_SMD_1.27X0.635MM_NO_SILK")
      (footprint "eagle-import:1X01_SMD_1.27X0.635MM_NO_SILK")
      (libsource (lib "eagle-import") (part "M01PTH_SMD_1.27X0.635MM_NO_SILK"))
    )
    (comp (ref "JP951")
      (value "M01PTH_SMD_1.27X0.635MM_NO_SILK")
      (footprint "eagle-import:1X01_SMD_1.27X0.635MM_NO_SILK")
      (libsource (lib "eagle-import") (part "M01PTH_SMD_1.27X0.635MM_NO_SILK"))
    )
    (comp (ref "JP952")
      (value "M01PTH_SMD_1.27X0.635MM_NO_SILK")
      (footprint "eagle-import:1X01_SMD_1.27X0.635MM_NO_SILK")
      (libsource (lib "eagle-import") (part "M01PTH_SMD_1.27X0.635MM_NO_SILK"))
    )
    (comp (ref "JP953")
      (value "M01PTH_SMD_1.27X0.635MM_NO_SILK")
      (footprint "eagle-import:1X01_SMD_1.27X0.635MM_NO_SILK")
      (libsource (lib "eagle-import") (part "M01PTH_SMD_1.27X0.635MM_NO_SILK"))
    )
    (comp (ref "JP954")
      (value "M01PTH_SMD_1.27X0.635MM_NO_SILK")
      (footprint "eagle-import:1X01_SMD_1.27X0.635MM_NO_SILK")
      (libsource (lib "eagle-import") (part "M01PTH_SMD_1.27X0.635MM_NO_SILK"))
    )
    (comp (ref "JP955")
      (value "M01PTH_SMD_1.27X0.635MM_NO_SILK")
      (footprint "eagle-import:1X01_SMD_1.27X0.635MM_NO_SILK")
      (libsource (lib "eagle-import") (part "M01PTH_SMD_1.27X0.635MM_NO_SILK"))
    )
    (comp (ref "JP956")
      (value "M01PTH_SMD_1.27X0.635MM_NO_SILK")
      (footprint "eagle-import:1X01_SMD_1.27X0.635MM_NO_SILK")
      (libsource (lib "eagle-import") (part "M01PTH_SMD_1.27X0.635MM_NO_SILK"))
    )
    (comp (ref "JP957")
      (value "M01PTH_SMD_1.27X0.635MM_NO_SILK")
      (footprint "eagle-import:1X01_SMD_1.27X0.635MM_NO_SILK")
      (libsource (lib "eagle-import") (part "M01PTH_SMD_1.27X0.635MM_NO_SILK"))
    )
    (comp (ref "JP958")
      (value "M01PTH_SMD_1.27X0.635MM_NO_SILK")
      (footprint "eagle-import:1X01_SMD_1.27X0.635MM_NO_SILK")
      (libsource (lib "eagle-import") (part "M01PTH_SMD_1.27X0.635MM_NO_SILK"))
    )
    (comp (ref "JP959")
      (value "M01PTH_SMD_1.27X0.635MM_NO_SILK")
      (footprint "eagle-import:1X01_SMD_1.27X0.635MM_NO_SILK")
      (libsource (lib "eagle-import") (part "M01PTH_SMD_1.27X0.635MM_NO_SILK"))
    )
    (comp (ref "JP960")
      (value "M01PTH_SMD_1.27X0.635MM_NO_SILK")
      (footprint "eagle-import:1X01_SMD_1.27X0.635MM_NO_SILK")
      (libsource (lib "eagle-import") (part "M01PTH_SMD_1.27X0.635MM_NO_SILK"))
    )
    (comp (ref "JP961")
      (value "M01PTH_SMD_1.27X0.635MM_NO_SILK")
      (footprint "eagle-import:1X01_SMD_1.27X0.635MM_NO_SILK")
      (libsource (lib "eagle-import") (part "M01PTH_SMD_1.27X0.635MM_NO_SILK"))
    )
    (comp (ref "JP962")
      (value "M01PTH_SMD_1.27X0.635MM_NO_SILK")
      (footprint "eagle-import:1X01_SMD_1.27X0.635MM_NO_SILK")
      (libsource (lib "eagle-import") (part "M01PTH_SMD_1.27X0.635MM_NO_SILK"))
    )
    (comp (ref "JP963")
      (value "M01PTH_SMD_1.27X0.635MM_NO_SILK")
      (footprint "eagle-import:1X01_SMD_1.27X0.635MM_NO_SILK")
      (libsource (lib "eagle-import") (part "M01PTH_SMD_1.27X0.635MM_NO_SILK"))
    )
    (comp (ref "JP964")
      (value "M01PTH_SMD_1.27X0.635MM_NO_SILK")
      (footprint "eagle-import:1X01_SMD_1.27X0.635MM_NO_SILK")
      (libsource (lib "eagle-import") (part "M01PTH_SMD_1.27X0.635MM_NO_SILK"))
    )
    (comp (ref "JP965")
      (value "M01PTH_SMD_1.27X0.635MM_NO_SILK")
      (footprint "eagle-import:1X01_SMD_1.27X0.635MM_NO_SILK")
      (libsource (lib "eagle-import") (part "M01PTH_SMD_1.27X0.635MM_NO_SILK"))
    )
    (comp (ref "JP966")
      (value "M01PTH_SMD_1.27X0.635MM_NO_SILK")
      (footprint "eagle-import:1X01_SMD_1.27X0.635MM_NO_SILK")
      (libsource (lib "eagle-import") (part "M01PTH_SMD_1.27X0.635MM_NO_SILK"))
    )
    (comp (ref "JP967")
      (value "M01PTH_SMD_1.27X0.635MM_NO_SILK")
      (footprint "eagle-import:1X01_SMD_1.27X0.635MM_NO_SILK")
      (libsource (lib "eagle-import") (part "M01PTH_SMD_1.27X0.635MM_NO_SILK"))
    )
    (comp (ref "JP968")
      (value "M01PTH_SMD_1.27X0.635MM_NO_SILK")
      (footprint "eagle-import:1X01_SMD_1.27X0.635MM_NO_SILK")
      (libsource (lib "eagle-import") (part "M01PTH_SMD_1.27X0.635MM_NO_SILK"))
    )
    (comp (ref "JP969")
      (value "M01PTH_SMD_1.27X0.635MM_NO_SILK")
      (footprint "eagle-import:1X01_SMD_1.27X0.635MM_NO_SILK")
      (libsource (lib "eagle-import") (part "M01PTH_SMD_1.27X0.635MM_NO_SILK"))
    )
    (comp (ref "JP970")
      (value "M01PTH_SMD_1.27X0.635MM_NO_SILK")
      (footprint "eagle-import:1X01_SMD_1.27X0.635MM_NO_SILK")
      (libsource (lib "eagle-import") (part "M01PTH_SMD_1.27X0.635MM_NO_SILK"))
    )
    (comp (ref "JP971")
      (value "M01PTH_SMD_1.27X0.635MM_NO_SILK")
      (footprint "eagle-import:1X01_SMD_1.27X0.635MM_NO_SILK")
      (libsource (lib "eagle-import") (part "M01PTH_SMD_1.27X0.635MM_NO_SILK"))
    )
    (comp (ref "JP972")
      (value "M01PTH_SMD_1.27X0.635MM_NO_SILK")
      (footprint "eagle-import:1X01_SMD_1.27X0.635MM_NO_SILK")
      (libsource (lib "eagle-import") (part "M01PTH_SMD_1.27X0.635MM_NO_SILK"))
    )
    (comp (ref "JP973")
      (value "M01PTH_SMD_1.27X0.635MM_NO_SILK")
      (footprint "eagle-import:1X01_SMD_1.27X0.635MM_NO_SILK")
      (libsource (lib "eagle-import") (part "M01PTH_SMD_1.27X0.635MM_NO_SILK"))
    )
    (comp (ref "JP974")
      (value "M01PTH_SMD_1.27X0.635MM_NO_SILK")
      (footprint "eagle-import:1X01_SMD_1.27X0.635MM_NO_SILK")
      (libsource (lib "eagle-import") (part "M01PTH_SMD_1.27X0.635MM_NO_SILK"))
    )
    (comp (ref "JP975")
      (value "M01PTH_SMD_1.27X0.635MM_NO_SILK")
      (footprint "eagle-import:1X01_SMD_1.27X0.635MM_NO_SILK")
      (libsource (lib "eagle-import") (part "M01PTH_SMD_1.27X0.635MM_NO_SILK"))
    )
    (comp (ref "JP976")
      (value "M01PTH_SMD_1.27X0.635MM_NO_SILK")
      (footprint "eagle-import:1X01_SMD_1.27X0.635MM_NO_SILK")
      (libsource (lib "eagle-import") (part "M01PTH_SMD_1.27X0.635MM_NO_SILK"))
    )
    (comp (ref "JP977")
      (value "M01PTH_SMD_1.27X0.635MM_NO_SILK")
      (footprint "eagle-import:1X01_SMD_1.27X0.635MM_NO_SILK")
      (libsource (lib "eagle-import") (part "M01PTH_SMD_1.27X0.635MM_NO_SILK"))
    )
    (comp (ref "JP978")
      (value "M01PTH_SMD_1.27X0.635MM_NO_SILK")
      (footprint "eagle-import:1X01_SMD_1.27X0.635MM_NO_SILK")
      (libsource (lib "eagle-import") (part "M01PTH_SMD_1.27X0.635MM_NO_SILK"))
    )
    (comp (ref "JP979")
      (value "M01PTH_SMD_1.27X0.635MM_NO_SILK")
      (footprint "eagle-import:1X01_SMD_1.27X0.635MM_NO_SILK")
      (libsource (lib "eagle-import") (part "M01PTH_SMD_1.27X0.635MM_NO_SILK"))
    )
    (comp (ref "JP980")
      (value "M01PTH_SMD_1.27X0.635MM_NO_SILK")
      (footprint "eagle-import:1X01_SMD_1.27X0.635MM_NO_SILK")
      (libsource (lib "eagle-import") (part "M01PTH_SMD_1.27X0.635MM_NO_SILK"))
    )
    (comp (ref "JP981")
      (value "M01PTH_SMD_1.27X0.635MM_NO_SILK")
      (footprint "eagle-import:1X01_SMD_1.27X0.635MM_NO_SILK")
      (libsource (lib "eagle-import") (part "M01PTH_SMD_1.27X0.635MM_NO_SILK"))
    )
    (comp (ref "JP982")
      (value "M01PTH_SMD_1.27X0.635MM_NO_SILK")
      (footprint "eagle-import:1X01_SMD_1.27X0.635MM_NO_SILK")
      (libsource (lib "eagle-import") (part "M01PTH_SMD_1.27X0.635MM_NO_SILK"))
    )
    (comp (ref "JP983")
      (value "M01PTH_SMD_1.27X0.635MM_NO_SILK")
      (footprint "eagle-import:1X01_SMD_1.27X0.635MM_NO_SILK")
      (libsource (lib "eagle-import") (part "M01PTH_SMD_1.27X0.635MM_NO_SILK"))
    )
    (comp (ref "JP984")
      (value "M01PTH_SMD_1.27X0.635MM_NO_SILK")
      (footprint "eagle-import:1X01_SMD_1.27X0.635MM_NO_SILK")
      (libsource (lib "eagle-import") (part "M01PTH_SMD_1.27X0.635MM_NO_SILK"))
    )
    (comp (ref "JP985")
      (value "M01PTH_SMD_1.27X0.635MM_NO_SILK")
      (footprint "eagle-import:1X01_SMD_1.27X0.635MM_NO_SILK")
      (libsource (lib "eagle-import") (part "M01PTH_SMD_1.27X0.635MM_NO_SILK"))
    )
    (comp (ref "JP986")
      (value "M01PTH_SMD_1.27X0.635MM_NO_SILK")
      (footprint "eagle-import:1X01_SMD_1.27X0.635MM_NO_SILK")
      (libsource (lib "eagle-import") (part "M01PTH_SMD_1.27X0.635MM_NO_SILK"))
    )
    (comp (ref "JP987")
      (value "M01PTH_SMD_1.27X0.635MM_NO_SILK")
      (footprint "eagle-import:1X01_SMD_1.27X0.635MM_NO_SILK")
      (libsource (lib "eagle-import") (part "M01PTH_SMD_1.27X0.635MM_NO_SILK"))
    )
    (comp (ref "JP988")
      (value "M01PTH_SMD_1.27X0.635MM_NO_SILK")
      (footprint "eagle-import:1X01_SMD_1.27X0.635MM_NO_SILK")
      (libsource (lib "eagle-import") (part "M01PTH_SMD_1.27X0.635MM_NO_SILK"))
    )
    (comp (ref "JP989")
      (value "M01PTH_SMD_1.27X0.635MM_NO_SILK")
      (footprint "eagle-import:1X01_SMD_1.27X0.635MM_NO_SILK")
      (libsource (lib "eagle-import") (part "M01PTH_SMD_1.27X0.635MM_NO_SILK"))
    )
    (comp (ref "JP990")
      (value "M01PTH_SMD_1.27X0.635MM_NO_SILK")
      (footprint "eagle-import:1X01_SMD_1.27X0.635MM_NO_SILK")
      (libsource (lib "eagle-import") (part "M01PTH_SMD_1.27X0.635MM_NO_SILK"))
    )
    (comp (ref "JP991")
      (value "M01PTH_SMD_1.27X0.635MM_NO_SILK")
      (footprint "eagle-import:1X01_SMD_1.27X0.635MM_NO_SILK")
      (libsource (lib "eagle-import") (part "M01PTH_SMD_1.27X0.635MM_NO_SILK"))
    )
    (comp (ref "JP992")
      (value "M01PTH_SMD_1.27X0.635MM_NO_SILK")
      (footprint "eagle-import:1X01_SMD_1.27X0.635MM_NO_SILK")
      (libsource (lib "eagle-import") (part "M01PTH_SMD_1.27X0.635MM_NO_SILK"))
    )
    (comp (ref "JP993")
      (value "M01PTH_SMD_1.27X0.635MM_NO_SILK")
      (footprint "eagle-import:1X01_SMD_1.27X0.635MM_NO_SILK")
      (libsource (lib "eagle-import") (part "M01PTH_SMD_1.27X0.635MM_NO_SILK"))
    )
    (comp (ref "JP994")
      (value "M01PTH_SMD_1.27X0.635MM_NO_SILK")
      (footprint "eagle-import:1X01_SMD_1.27X0.635MM_NO_SILK")
      (libsource (lib "eagle-import") (part "M01PTH_SMD_1.27X0.635MM_NO_SILK"))
    )
    (comp (ref "JP995")
      (value "M01PTH_SMD_1.27X0.635MM_NO_SILK")
      (footprint "eagle-import:1X01_SMD_1.27X0.635MM_NO_SILK")
      (libsource (lib "eagle-import") (part "M01PTH_SMD_1.27X0.635MM_NO_SILK"))
    )
    (comp (ref "JP996")
      (value "M01PTH_SMD_1.27X0.635MM_NO_SILK")
      (footprint "eagle-import:1X01_SMD_1.27X0.635MM_NO_SILK")
      (libsource (lib "eagle-import") (part "M01PTH_SMD_1.27X0.635MM_NO_SILK"))
    )
    (comp (ref "JP997")
      (value "M01PTH_SMD_1.27X0.635MM_NO_SILK")
      (footprint "eagle-import:1X01_SMD_1.27X0.635MM_NO_SILK")
      (libsource (lib "eagle-import") (part "M01PTH_SMD_1.27X0.635MM_NO_SILK"))
    )
    (comp (ref "JP998")
      (value "M01PTH_SMD_1.27X0.635MM_NO_SILK")
      (footprint "eagle-import:1X01_SMD_1.27X0.635MM_NO_SILK")
      (libsource (lib "eagle-import") (part "M01PTH_SMD_1.27X0.635MM_NO_SILK"))
    )
    (comp (ref "JP999")
      (value "M01PTH_SMD_1.27X0.635MM_NO_SILK")
      (footprint "eagle-import:1X01_SMD_1.27X0.635MM_NO_SILK")
      (libsource (lib "eagle-import") (part "M01PTH_SMD_1.27X0.635MM_NO_SILK"))
    )
    (comp (ref "JP1000")
      (value "M01PTH_SMD_1.27X0.635MM_NO_SILK")
      (footprint "eagle-import:1X01_SMD_1.27X0.635MM_NO_SILK")
      (libsource (lib "eagle-import") (part "M01PTH_SMD_1.27X0.635MM_NO_SILK"))
    )
    (comp (ref "JP1001")
      (value "M01PTH_SMD_1.27X0.635MM_NO_SILK")
      (footprint "eagle-import:1X01_SMD_1.27X0.635MM_NO_SILK")
      (libsource (lib "eagle-import") (part "M01PTH_SMD_1.27X0.635MM_NO_SILK"))
    )
    (comp (ref "JP1002")
      (value "M01PTH_SMD_1.27X0.635MM_NO_SILK")
      (footprint "eagle-import:1X01_SMD_1.27X0.635MM_NO_SILK")
      (libsource (lib "eagle-import") (part "M01PTH_SMD_1.27X0.635MM_NO_SILK"))
    )
    (comp (ref "JP1003")
      (value "M01PTH_SMD_1.27X0.635MM_NO_SILK")
      (footprint "eagle-import:1X01_SMD_1.27X0.635MM_NO_SILK")
      (libsource (lib "eagle-import") (part "M01PTH_SMD_1.27X0.635MM_NO_SILK"))
    )
    (comp (ref "JP1004")
      (value "M01PTH_SMD_1.27X0.635MM_NO_SILK")
      (footprint "eagle-import:1X01_SMD_1.27X0.635MM_NO_SILK")
      (libsource (lib "eagle-import") (part "M01PTH_SMD_1.27X0.635MM_NO_SILK"))
    )
    (comp (ref "JP1005")
      (value "M01PTH_SMD_1.27X0.635MM_NO_SILK")
      (footprint "eagle-import:1X01_SMD_1.27X0.635MM_NO_SILK")
      (libsource (lib "eagle-import") (part "M01PTH_SMD_1.27X0.635MM_NO_SILK"))
    )
    (comp (ref "JP1006")
      (value "M01PTH_SMD_1.27X0.635MM_NO_SILK")
      (footprint "eagle-import:1X01_SMD_1.27X0.635MM_NO_SILK")
      (libsource (lib "eagle-import") (part "M01PTH_SMD_1.27X0.635MM_NO_SILK"))
    )
    (comp (ref "JP1007")
      (value "M01PTH_SMD_1.27X0.635MM_NO_SILK")
      (footprint "eagle-import:1X01_SMD_1.27X0.635MM_NO_SILK")
      (libsource (lib "eagle-import") (part "M01PTH_SMD_1.27X0.635MM_NO_SILK"))
    )
    (comp (ref "JP1008")
      (value "M01PTH_SMD_1.27X0.635MM_NO_SILK")
      (footprint "eagle-import:1X01_SMD_1.27X0.635MM_NO_SILK")
      (libsource (lib "eagle-import") (part "M01PTH_SMD_1.27X0.635MM_NO_SILK"))
    )
    (comp (ref "JP1009")
      (value "M01PTH_SMD_1.27X0.635MM_NO_SILK")
      (footprint "eagle-import:1X01_SMD_1.27X0.635MM_NO_SILK")
      (libsource (lib "eagle-import") (part "M01PTH_SMD_1.27X0.635MM_NO_SILK"))
    )
    (comp (ref "JP1010")
      (value "M01PTH_SMD_1.27X0.635MM_NO_SILK")
      (footprint "eagle-import:1X01_SMD_1.27X0.635MM_NO_SILK")
      (libsource (lib "eagle-import") (part "M01PTH_SMD_1.27X0.635MM_NO_SILK"))
    )
    (comp (ref "JP1011")
      (value "M01PTH_SMD_1.27X0.635MM_NO_SILK")
      (footprint "eagle-import:1X01_SMD_1.27X0.635MM_NO_SILK")
      (libsource (lib "eagle-import") (part "M01PTH_SMD_1.27X0.635MM_NO_SILK"))
    )
    (comp (ref "JP1012")
      (value "M01PTH_SMD_1.27X0.635MM_NO_SILK")
      (footprint "eagle-import:1X01_SMD_1.27X0.635MM_NO_SILK")
      (libsource (lib "eagle-import") (part "M01PTH_SMD_1.27X0.635MM_NO_SILK"))
    )
    (comp (ref "JP1013")
      (value "M01PTH_SMD_1.27X0.635MM_NO_SILK")
      (footprint "eagle-import:1X01_SMD_1.27X0.635MM_NO_SILK")
      (libsource (lib "eagle-import") (part "M01PTH_SMD_1.27X0.635MM_NO_SILK"))
    )
    (comp (ref "JP1014")
      (value "M01PTH_SMD_1.27X0.635MM_NO_SILK")
      (footprint "eagle-import:1X01_SMD_1.27X0.635MM_NO_SILK")
      (libsource (lib "eagle-import") (part "M01PTH_SMD_1.27X0.635MM_NO_SILK"))
    )
    (comp (ref "JP1015")
      (value "M01PTH_SMD_1.27X0.635MM_NO_SILK")
      (footprint "eagle-import:1X01_SMD_1.27X0.635MM_NO_SILK")
      (libsource (lib "eagle-import") (part "M01PTH_SMD_1.27X0.635MM_NO_SILK"))
    )
    (comp (ref "JP1016")
      (value "M01PTH_SMD_1.27X0.635MM_NO_SILK")
      (footprint "eagle-import:1X01_SMD_1.27X0.635MM_NO_SILK")
      (libsource (lib "eagle-import") (part "M01PTH_SMD_1.27X0.635MM_NO_SILK"))
    )
    (comp (ref "JP1017")
      (value "M01PTH_SMD_1.27X0.635MM_NO_SILK")
      (footprint "eagle-import:1X01_SMD_1.27X0.635MM_NO_SILK")
      (libsource (lib "eagle-import") (part "M01PTH_SMD_1.27X0.635MM_NO_SILK"))
    )
    (comp (ref "JP1018")
      (value "M01PTH_SMD_1.27X0.635MM_NO_SILK")
      (footprint "eagle-import:1X01_SMD_1.27X0.635MM_NO_SILK")
      (libsource (lib "eagle-import") (part "M01PTH_SMD_1.27X0.635MM_NO_SILK"))
    )
    (comp (ref "JP1019")
      (value "M01PTH_SMD_1.27X0.635MM_NO_SILK")
      (footprint "eagle-import:1X01_SMD_1.27X0.635MM_NO_SILK")
      (libsource (lib "eagle-import") (part "M01PTH_SMD_1.27X0.635MM_NO_SILK"))
    )
    (comp (ref "JP1020")
      (value "M01PTH_SMD_1.27X0.635MM_NO_SILK")
      (footprint "eagle-import:1X01_SMD_1.27X0.635MM_NO_SILK")
      (libsource (lib "eagle-import") (part "M01PTH_SMD_1.27X0.635MM_NO_SILK"))
    )
    (comp (ref "JP1021")
      (value "M01PTH_SMD_1.27X0.635MM_NO_SILK")
      (footprint "eagle-import:1X01_SMD_1.27X0.635MM_NO_SILK")
      (libsource (lib "eagle-import") (part "M01PTH_SMD_1.27X0.635MM_NO_SILK"))
    )
    (comp (ref "JP1022")
      (value "M01PTH_SMD_1.27X0.635MM_NO_SILK")
      (footprint "eagle-import:1X01_SMD_1.27X0.635MM_NO_SILK")
      (libsource (lib "eagle-import") (part "M01PTH_SMD_1.27X0.635MM_NO_SILK"))
    )
    (comp (ref "JP1023")
      (value "M01PTH_SMD_1.27X0.635MM_NO_SILK")
      (footprint "eagle-import:1X01_SMD_1.27X0.635MM_NO_SILK")
      (libsource (lib "eagle-import") (part "M01PTH_SMD_1.27X0.635MM_NO_SILK"))
    )
    (comp (ref "JP1024")
      (value "M01PTH_SMD_1.27X0.635MM_NO_SILK")
      (footprint "eagle-import:1X01_SMD_1.27X0.635MM_NO_SILK")
      (libsource (lib "eagle-import") (part "M01PTH_SMD_1.27X0.635MM_NO_SILK"))
    )
    (comp (ref "JP1025")
      (value "M01PTH_SMD_1.27X0.635MM_NO_SILK")
      (footprint "eagle-import:1X01_SMD_1.27X0.635MM_NO_SILK")
      (libsource (lib "eagle-import") (part "M01PTH_SMD_1.27X0.635MM_NO_SILK"))
    )
    (comp (ref "JP1026")
      (value "M01PTH_SMD_1.27X0.635MM_NO_SILK")
      (footprint "eagle-import:1X01_SMD_1.27X0.635MM_NO_SILK")
      (libsource (lib "eagle-import") (part "M01PTH_SMD_1.27X0.635MM_NO_SILK"))
    )
    (comp (ref "JP1027")
      (value "M01PTH_SMD_1.27X0.635MM_NO_SILK")
      (footprint "eagle-import:1X01_SMD_1.27X0.635MM_NO_SILK")
      (libsource (lib "eagle-import") (part "M01PTH_SMD_1.27X0.635MM_NO_SILK"))
    )
    (comp (ref "JP1028")
      (value "M01PTH_SMD_1.27X0.635MM_NO_SILK")
      (footprint "eagle-import:1X01_SMD_1.27X0.635MM_NO_SILK")
      (libsource (lib "eagle-import") (part "M01PTH_SMD_1.27X0.635MM_NO_SILK"))
    )
    (comp (ref "JP1029")
      (value "M01PTH_SMD_1.27X0.635MM_NO_SILK")
      (footprint "eagle-import:1X01_SMD_1.27X0.635MM_NO_SILK")
      (libsource (lib "eagle-import") (part "M01PTH_SMD_1.27X0.635MM_NO_SILK"))
    )
    (comp (ref "JP1030")
      (value "M01PTH_SMD_1.27X0.635MM_NO_SILK")
      (footprint "eagle-import:1X01_SMD_1.27X0.635MM_NO_SILK")
      (libsource (lib "eagle-import") (part "M01PTH_SMD_1.27X0.635MM_NO_SILK"))
    )
    (comp (ref "JP1031")
      (value "M01PTH_SMD_1.27X0.635MM_NO_SILK")
      (footprint "eagle-import:1X01_SMD_1.27X0.635MM_NO_SILK")
      (libsource (lib "eagle-import") (part "M01PTH_SMD_1.27X0.635MM_NO_SILK"))
    )
    (comp (ref "JP1032")
      (value "M01PTH_SMD_1.27X0.635MM_NO_SILK")
      (footprint "eagle-import:1X01_SMD_1.27X0.635MM_NO_SILK")
      (libsource (lib "eagle-import") (part "M01PTH_SMD_1.27X0.635MM_NO_SILK"))
    )
    (comp (ref "JP1033")
      (value "M01PTH_SMD_1.27X0.635MM_NO_SILK")
      (footprint "eagle-import:1X01_SMD_1.27X0.635MM_NO_SILK")
      (libsource (lib "eagle-import") (part "M01PTH_SMD_1.27X0.635MM_NO_SILK"))
    )
    (comp (ref "JP1034")
      (value "M01PTH_SMD_1.27X0.635MM_NO_SILK")
      (footprint "eagle-import:1X01_SMD_1.27X0.635MM_NO_SILK")
      (libsource (lib "eagle-import") (part "M01PTH_SMD_1.27X0.635MM_NO_SILK"))
    )
    (comp (ref "JP1035")
      (value "M01PTH_SMD_1.27X0.635MM_NO_SILK")
      (footprint "eagle-import:1X01_SMD_1.27X0.635MM_NO_SILK")
      (libsource (lib "eagle-import") (part "M01PTH_SMD_1.27X0.635MM_NO_SILK"))
    )
    (comp (ref "JP1036")
      (value "M01PTH_SMD_1.27X0.635MM_NO_SILK")
      (footprint "eagle-import:1X01_SMD_1.27X0.635MM_NO_SILK")
      (libsource (lib "eagle-import") (part "M01PTH_SMD_1.27X0.635MM_NO_SILK"))
    )
    (comp (ref "JP1037")
      (value "M01PTH_SMD_1.27X0.635MM_NO_SILK")
      (footprint "eagle-import:1X01_SMD_1.27X0.635MM_NO_SILK")
      (libsource (lib "eagle-import") (part "M01PTH_SMD_1.27X0.635MM_NO_SILK"))
    )
    (comp (ref "JP1038")
      (value "M01PTH_SMD_1.27X0.635MM_NO_SILK")
      (footprint "eagle-import:1X01_SMD_1.27X0.635MM_NO_SILK")
      (libsource (lib "eagle-import") (part "M01PTH_SMD_1.27X0.635MM_NO_SILK"))
    )
    (comp (ref "JP1039")
      (value "M01PTH_SMD_1.27X0.635MM_NO_SILK")
      (footprint "eagle-import:1X01_SMD_1.27X0.635MM_NO_SILK")
      (libsource (lib "eagle-import") (part "M01PTH_SMD_1.27X0.635MM_NO_SILK"))
    )
    (comp (ref "JP1040")
      (value "M01PTH_SMD_1.27X0.635MM_NO_SILK")
      (footprint "eagle-import:1X01_SMD_1.27X0.635MM_NO_SILK")
      (libsource (lib "eagle-import") (part "M01PTH_SMD_1.27X0.635MM_NO_SILK"))
    )
    (comp (ref "JP1041")
      (value "M01PTH_SMD_1.27X0.635MM_NO_SILK")
      (footprint "eagle-import:1X01_SMD_1.27X0.635MM_NO_SILK")
      (libsource (lib "eagle-import") (part "M01PTH_SMD_1.27X0.635MM_NO_SILK"))
    )
    (comp (ref "JP1042")
      (value "M01PTH_SMD_1.27X0.635MM_NO_SILK")
      (footprint "eagle-import:1X01_SMD_1.27X0.635MM_NO_SILK")
      (libsource (lib "eagle-import") (part "M01PTH_SMD_1.27X0.635MM_NO_SILK"))
    )
    (comp (ref "JP1043")
      (value "M01PTH_SMD_1.27X0.635MM_NO_SILK")
      (footprint "eagle-import:1X01_SMD_1.27X0.635MM_NO_SILK")
      (libsource (lib "eagle-import") (part "M01PTH_SMD_1.27X0.635MM_NO_SILK"))
    )
    (comp (ref "JP1044")
      (value "M01PTH_SMD_1.27X0.635MM_NO_SILK")
      (footprint "eagle-import:1X01_SMD_1.27X0.635MM_NO_SILK")
      (libsource (lib "eagle-import") (part "M01PTH_SMD_1.27X0.635MM_NO_SILK"))
    )
    (comp (ref "JP1045")
      (value "M01PTH_SMD_1.27X0.635MM_NO_SILK")
      (footprint "eagle-import:1X01_SMD_1.27X0.635MM_NO_SILK")
      (libsource (lib "eagle-import") (part "M01PTH_SMD_1.27X0.635MM_NO_SILK"))
    )
    (comp (ref "JP1046")
      (value "M01PTH_SMD_1.27X0.635MM_NO_SILK")
      (footprint "eagle-import:1X01_SMD_1.27X0.635MM_NO_SILK")
      (libsource (lib "eagle-import") (part "M01PTH_SMD_1.27X0.635MM_NO_SILK"))
    )
    (comp (ref "JP1047")
      (value "M01PTH_SMD_1.27X0.635MM_NO_SILK")
      (footprint "eagle-import:1X01_SMD_1.27X0.635MM_NO_SILK")
      (libsource (lib "eagle-import") (part "M01PTH_SMD_1.27X0.635MM_NO_SILK"))
    )
    (comp (ref "JP1048")
      (value "M01PTH_SMD_1.27X0.635MM_NO_SILK")
      (footprint "eagle-import:1X01_SMD_1.27X0.635MM_NO_SILK")
      (libsource (lib "eagle-import") (part "M01PTH_SMD_1.27X0.635MM_NO_SILK"))
    )
    (comp (ref "JP1049")
      (value "M01PTH_SMD_1.27X0.635MM_NO_SILK")
      (footprint "eagle-import:1X01_SMD_1.27X0.635MM_NO_SILK")
      (libsource (lib "eagle-import") (part "M01PTH_SMD_1.27X0.635MM_NO_SILK"))
    )
    (comp (ref "JP1050")
      (value "M01PTH_SMD_1.27X0.635MM_NO_SILK")
      (footprint "eagle-import:1X01_SMD_1.27X0.635MM_NO_SILK")
      (libsource (lib "eagle-import") (part "M01PTH_SMD_1.27X0.635MM_NO_SILK"))
    )
    (comp (ref "JP1051")
      (value "M01PTH_SMD_1.27X0.635MM_NO_SILK")
      (footprint "eagle-import:1X01_SMD_1.27X0.635MM_NO_SILK")
      (libsource (lib "eagle-import") (part "M01PTH_SMD_1.27X0.635MM_NO_SILK"))
    )
    (comp (ref "JP1052")
      (value "M01PTH_SMD_1.27X0.635MM_NO_SILK")
      (footprint "eagle-import:1X01_SMD_1.27X0.635MM_NO_SILK")
      (libsource (lib "eagle-import") (part "M01PTH_SMD_1.27X0.635MM_NO_SILK"))
    )
    (comp (ref "JP1053")
      (value "M01PTH_SMD_1.27X0.635MM_NO_SILK")
      (footprint "eagle-import:1X01_SMD_1.27X0.635MM_NO_SILK")
      (libsource (lib "eagle-import") (part "M01PTH_SMD_1.27X0.635MM_NO_SILK"))
    )
    (comp (ref "JP1054")
      (value "M01PTH_SMD_1.27X0.635MM_NO_SILK")
      (footprint "eagle-import:1X01_SMD_1.27X0.635MM_NO_SILK")
      (libsource (lib "eagle-import") (part "M01PTH_SMD_1.27X0.635MM_NO_SILK"))
    )
    (comp (ref "JP1055")
      (value "M01PTH_SMD_1.27X0.635MM_NO_SILK")
      (footprint "eagle-import:1X01_SMD_1.27X0.635MM_NO_SILK")
      (libsource (lib "eagle-import") (part "M01PTH_SMD_1.27X0.635MM_NO_SILK"))
    )
    (comp (ref "JP1056")
      (value "M01PTH_SMD_1.27X0.635MM_NO_SILK")
      (footprint "eagle-import:1X01_SMD_1.27X0.635MM_NO_SILK")
      (libsource (lib "eagle-import") (part "M01PTH_SMD_1.27X0.635MM_NO_SILK"))
    )
    (comp (ref "JP1057")
      (value "M01PTH_SMD_1.27X0.635MM_NO_SILK")
      (footprint "eagle-import:1X01_SMD_1.27X0.635MM_NO_SILK")
      (libsource (lib "eagle-import") (part "M01PTH_SMD_1.27X0.635MM_NO_SILK"))
    )
    (comp (ref "JP1058")
      (value "M01PTH_SMD_1.27X0.635MM_NO_SILK")
      (footprint "eagle-import:1X01_SMD_1.27X0.635MM_NO_SILK")
      (libsource (lib "eagle-import") (part "M01PTH_SMD_1.27X0.635MM_NO_SILK"))
    )
    (comp (ref "JP1059")
      (value "M01PTH_SMD_1.27X0.635MM_NO_SILK")
      (footprint "eagle-import:1X01_SMD_1.27X0.635MM_NO_SILK")
      (libsource (lib "eagle-import") (part "M01PTH_SMD_1.27X0.635MM_NO_SILK"))
    )
    (comp (ref "JP1060")
      (value "M01PTH_SMD_1.27X0.635MM_NO_SILK")
      (footprint "eagle-import:1X01_SMD_1.27X0.635MM_NO_SILK")
      (libsource (lib "eagle-import") (part "M01PTH_SMD_1.27X0.635MM_NO_SILK"))
    )
    (comp (ref "JP1061")
      (value "M01PTH_SMD_1.27X0.635MM_NO_SILK")
      (footprint "eagle-import:1X01_SMD_1.27X0.635MM_NO_SILK")
      (libsource (lib "eagle-import") (part "M01PTH_SMD_1.27X0.635MM_NO_SILK"))
    )
    (comp (ref "JP1062")
      (value "M01PTH_SMD_1.27X0.635MM_NO_SILK")
      (footprint "eagle-import:1X01_SMD_1.27X0.635MM_NO_SILK")
      (libsource (lib "eagle-import") (part "M01PTH_SMD_1.27X0.635MM_NO_SILK"))
    )
    (comp (ref "JP1063")
      (value "M01PTH_SMD_1.27X0.635MM_NO_SILK")
      (footprint "eagle-import:1X01_SMD_1.27X0.635MM_NO_SILK")
      (libsource (lib "eagle-import") (part "M01PTH_SMD_1.27X0.635MM_NO_SILK"))
    )
    (comp (ref "JP1064")
      (value "M01PTH_SMD_1.27X0.635MM_NO_SILK")
      (footprint "eagle-import:1X01_SMD_1.27X0.635MM_NO_SILK")
      (libsource (lib "eagle-import") (part "M01PTH_SMD_1.27X0.635MM_NO_SILK"))
    )
    (comp (ref "JP1065")
      (value "M01PTH_SMD_1.27X0.635MM_NO_SILK")
      (footprint "eagle-import:1X01_SMD_1.27X0.635MM_NO_SILK")
      (libsource (lib "eagle-import") (part "M01PTH_SMD_1.27X0.635MM_NO_SILK"))
    )
    (comp (ref "JP1066")
      (value "M01PTH_SMD_1.27X0.635MM_NO_SILK")
      (footprint "eagle-import:1X01_SMD_1.27X0.635MM_NO_SILK")
      (libsource (lib "eagle-import") (part "M01PTH_SMD_1.27X0.635MM_NO_SILK"))
    )
    (comp (ref "JP1067")
      (value "M01PTH_SMD_1.27X0.635MM_NO_SILK")
      (footprint "eagle-import:1X01_SMD_1.27X0.635MM_NO_SILK")
      (libsource (lib "eagle-import") (part "M01PTH_SMD_1.27X0.635MM_NO_SILK"))
    )
    (comp (ref "JP1068")
      (value "M01PTH_SMD_1.27X0.635MM_NO_SILK")
      (footprint "eagle-import:1X01_SMD_1.27X0.635MM_NO_SILK")
      (libsource (lib "eagle-import") (part "M01PTH_SMD_1.27X0.635MM_NO_SILK"))
    )
    (comp (ref "JP1069")
      (value "M01PTH_SMD_1.27X0.635MM_NO_SILK")
      (footprint "eagle-import:1X01_SMD_1.27X0.635MM_NO_SILK")
      (libsource (lib "eagle-import") (part "M01PTH_SMD_1.27X0.635MM_NO_SILK"))
    )
    (comp (ref "JP1070")
      (value "M01PTH_SMD_1.27X0.635MM_NO_SILK")
      (footprint "eagle-import:1X01_SMD_1.27X0.635MM_NO_SILK")
      (libsource (lib "eagle-import") (part "M01PTH_SMD_1.27X0.635MM_NO_SILK"))
    )
    (comp (ref "JP1071")
      (value "M01PTH_SMD_1.27X0.635MM_NO_SILK")
      (footprint "eagle-import:1X01_SMD_1.27X0.635MM_NO_SILK")
      (libsource (lib "eagle-import") (part "M01PTH_SMD_1.27X0.635MM_NO_SILK"))
    )
    (comp (ref "JP1072")
      (value "M01PTH_SMD_1.27X0.635MM_NO_SILK")
      (footprint "eagle-import:1X01_SMD_1.27X0.635MM_NO_SILK")
      (libsource (lib "eagle-import") (part "M01PTH_SMD_1.27X0.635MM_NO_SILK"))
    )
    (comp (ref "JP1073")
      (value "M01PTH_SMD_1.27X0.635MM_NO_SILK")
      (footprint "eagle-import:1X01_SMD_1.27X0.635MM_NO_SILK")
      (libsource (lib "eagle-import") (part "M01PTH_SMD_1.27X0.635MM_NO_SILK"))
    )
    (comp (ref "JP1074")
      (value "M01PTH_SMD_1.27X0.635MM_NO_SILK")
      (footprint "eagle-import:1X01_SMD_1.27X0.635MM_NO_SILK")
      (libsource (lib "eagle-import") (part "M01PTH_SMD_1.27X0.635MM_NO_SILK"))
    )
    (comp (ref "JP1075")
      (value "M01PTH_SMD_1.27X0.635MM_NO_SILK")
      (footprint "eagle-import:1X01_SMD_1.27X0.635MM_NO_SILK")
      (libsource (lib "eagle-import") (part "M01PTH_SMD_1.27X0.635MM_NO_SILK"))
    )
    (comp (ref "JP1076")
      (value "M01PTH_SMD_1.27X0.635MM_NO_SILK")
      (footprint "eagle-import:1X01_SMD_1.27X0.635MM_NO_SILK")
      (libsource (lib "eagle-import") (part "M01PTH_SMD_1.27X0.635MM_NO_SILK"))
    )
    (comp (ref "JP1077")
      (value "M01PTH_SMD_1.27X0.635MM_NO_SILK")
      (footprint "eagle-import:1X01_SMD_1.27X0.635MM_NO_SILK")
      (libsource (lib "eagle-import") (part "M01PTH_SMD_1.27X0.635MM_NO_SILK"))
    )
    (comp (ref "JP1078")
      (value "M01PTH_SMD_1.27X0.635MM_NO_SILK")
      (footprint "eagle-import:1X01_SMD_1.27X0.635MM_NO_SILK")
      (libsource (lib "eagle-import") (part "M01PTH_SMD_1.27X0.635MM_NO_SILK"))
    )
    (comp (ref "JP1079")
      (value "M01PTH_SMD_1.27X0.635MM_NO_SILK")
      (footprint "eagle-import:1X01_SMD_1.27X0.635MM_NO_SILK")
      (libsource (lib "eagle-import") (part "M01PTH_SMD_1.27X0.635MM_NO_SILK"))
    )
    (comp (ref "JP1080")
      (value "M01PTH_SMD_1.27X0.635MM_NO_SILK")
      (footprint "eagle-import:1X01_SMD_1.27X0.635MM_NO_SILK")
      (libsource (lib "eagle-import") (part "M01PTH_SMD_1.27X0.635MM_NO_SILK"))
    )
    (comp (ref "JP1081")
      (value "M01PTH_SMD_1.27X0.635MM_NO_SILK")
      (footprint "eagle-import:1X01_SMD_1.27X0.635MM_NO_SILK")
      (libsource (lib "eagle-import") (part "M01PTH_SMD_1.27X0.635MM_NO_SILK"))
    )
    (comp (ref "JP1082")
      (value "M01PTH_SMD_1.27X0.635MM_NO_SILK")
      (footprint "eagle-import:1X01_SMD_1.27X0.635MM_NO_SILK")
      (libsource (lib "eagle-import") (part "M01PTH_SMD_1.27X0.635MM_NO_SILK"))
    )
    (comp (ref "JP1083")
      (value "M01PTH_SMD_1.27X0.635MM_NO_SILK")
      (footprint "eagle-import:1X01_SMD_1.27X0.635MM_NO_SILK")
      (libsource (lib "eagle-import") (part "M01PTH_SMD_1.27X0.635MM_NO_SILK"))
    )
    (comp (ref "JP1084")
      (value "M01PTH_SMD_1.27X0.635MM_NO_SILK")
      (footprint "eagle-import:1X01_SMD_1.27X0.635MM_NO_SILK")
      (libsource (lib "eagle-import") (part "M01PTH_SMD_1.27X0.635MM_NO_SILK"))
    )
    (comp (ref "JP1085")
      (value "M01PTH_SMD_1.27X0.635MM_NO_SILK")
      (footprint "eagle-import:1X01_SMD_1.27X0.635MM_NO_SILK")
      (libsource (lib "eagle-import") (part "M01PTH_SMD_1.27X0.635MM_NO_SILK"))
    )
    (comp (ref "JP1086")
      (value "M01PTH_SMD_1.27X0.635MM_NO_SILK")
      (footprint "eagle-import:1X01_SMD_1.27X0.635MM_NO_SILK")
      (libsource (lib "eagle-import") (part "M01PTH_SMD_1.27X0.635MM_NO_SILK"))
    )
    (comp (ref "JP1087")
      (value "M01PTH_SMD_1.27X0.635MM_NO_SILK")
      (footprint "eagle-import:1X01_SMD_1.27X0.635MM_NO_SILK")
      (libsource (lib "eagle-import") (part "M01PTH_SMD_1.27X0.635MM_NO_SILK"))
    )
    (comp (ref "JP1088")
      (value "M01PTH_SMD_1.27X0.635MM_NO_SILK")
      (footprint "eagle-import:1X01_SMD_1.27X0.635MM_NO_SILK")
      (libsource (lib "eagle-import") (part "M01PTH_SMD_1.27X0.635MM_NO_SILK"))
    )
    (comp (ref "JP1089")
      (value "M01PTH_SMD_1.27X0.635MM_NO_SILK")
      (footprint "eagle-import:1X01_SMD_1.27X0.635MM_NO_SILK")
      (libsource (lib "eagle-import") (part "M01PTH_SMD_1.27X0.635MM_NO_SILK"))
    )
    (comp (ref "JP1090")
      (value "M01PTH_SMD_1.27X0.635MM_NO_SILK")
      (footprint "eagle-import:1X01_SMD_1.27X0.635MM_NO_SILK")
      (libsource (lib "eagle-import") (part "M01PTH_SMD_1.27X0.635MM_NO_SILK"))
    )
    (comp (ref "JP1091")
      (value "M01PTH_SMD_1.27X0.635MM_NO_SILK")
      (footprint "eagle-import:1X01_SMD_1.27X0.635MM_NO_SILK")
      (libsource (lib "eagle-import") (part "M01PTH_SMD_1.27X0.635MM_NO_SILK"))
    )
    (comp (ref "JP1092")
      (value "M01PTH_SMD_1.27X0.635MM_NO_SILK")
      (footprint "eagle-import:1X01_SMD_1.27X0.635MM_NO_SILK")
      (libsource (lib "eagle-import") (part "M01PTH_SMD_1.27X0.635MM_NO_SILK"))
    )
    (comp (ref "JP1093")
      (value "M01PTH_SMD_1.27X0.635MM_NO_SILK")
      (footprint "eagle-import:1X01_SMD_1.27X0.635MM_NO_SILK")
      (libsource (lib "eagle-import") (part "M01PTH_SMD_1.27X0.635MM_NO_SILK"))
    )
    (comp (ref "JP1094")
      (value "M01PTH_SMD_1.27X0.635MM_NO_SILK")
      (footprint "eagle-import:1X01_SMD_1.27X0.635MM_NO_SILK")
      (libsource (lib "eagle-import") (part "M01PTH_SMD_1.27X0.635MM_NO_SILK"))
    )
    (comp (ref "JP1095")
      (value "M01PTH_SMD_1.27X0.635MM_NO_SILK")
      (footprint "eagle-import:1X01_SMD_1.27X0.635MM_NO_SILK")
      (libsource (lib "eagle-import") (part "M01PTH_SMD_1.27X0.635MM_NO_SILK"))
    )
    (comp (ref "JP1096")
      (value "M01PTH_SMD_1.27X0.635MM_NO_SILK")
      (footprint "eagle-import:1X01_SMD_1.27X0.635MM_NO_SILK")
      (libsource (lib "eagle-import") (part "M01PTH_SMD_1.27X0.635MM_NO_SILK"))
    )
    (comp (ref "JP1097")
      (value "M01PTH_SMD_1.27X0.635MM_NO_SILK")
      (footprint "eagle-import:1X01_SMD_1.27X0.635MM_NO_SILK")
      (libsource (lib "eagle-import") (part "M01PTH_SMD_1.27X0.635MM_NO_SILK"))
    )
    (comp (ref "JP1098")
      (value "M01PTH_SMD_1.27X0.635MM_NO_SILK")
      (footprint "eagle-import:1X01_SMD_1.27X0.635MM_NO_SILK")
      (libsource (lib "eagle-import") (part "M01PTH_SMD_1.27X0.635MM_NO_SILK"))
    )
    (comp (ref "JP1099")
      (value "M01PTH_SMD_1.27X0.635MM_NO_SILK")
      (footprint "eagle-import:1X01_SMD_1.27X0.635MM_NO_SILK")
      (libsource (lib "eagle-import") (part "M01PTH_SMD_1.27X0.635MM_NO_SILK"))
    )
    (comp (ref "JP1100")
      (value "M01PTH_SMD_1.27X0.635MM_NO_SILK")
      (footprint "eagle-import:1X01_SMD_1.27X0.635MM_NO_SILK")
      (libsource (lib "eagle-import") (part "M01PTH_SMD_1.27X0.635MM_NO_SILK"))
    )
    (comp (ref "JP1101")
      (value "M01PTH_SMD_1.27X0.635MM_NO_SILK")
      (footprint "eagle-import:1X01_SMD_1.27X0.635MM_NO_SILK")
      (libsource (lib "eagle-import") (part "M01PTH_SMD_1.27X0.635MM_NO_SILK"))
    )
    (comp (ref "JP1102")
      (value "M01PTH_SMD_1.27X0.635MM_NO_SILK")
      (footprint "eagle-import:1X01_SMD_1.27X0.635MM_NO_SILK")
      (libsource (lib "eagle-import") (part "M01PTH_SMD_1.27X0.635MM_NO_SILK"))
    )
    (comp (ref "JP1103")
      (value "M01PTH_SMD_1.27X0.635MM_NO_SILK")
      (footprint "eagle-import:1X01_SMD_1.27X0.635MM_NO_SILK")
      (libsource (lib "eagle-import") (part "M01PTH_SMD_1.27X0.635MM_NO_SILK"))
    )
    (comp (ref "JP1104")
      (value "M01PTH_SMD_1.27X0.635MM_NO_SILK")
      (footprint "eagle-import:1X01_SMD_1.27X0.635MM_NO_SILK")
      (libsource (lib "eagle-import") (part "M01PTH_SMD_1.27X0.635MM_NO_SILK"))
    )
    (comp (ref "JP1105")
      (value "M01PTH_SMD_1.27X0.635MM_NO_SILK")
      (footprint "eagle-import:1X01_SMD_1.27X0.635MM_NO_SILK")
      (libsource (lib "eagle-import") (part "M01PTH_SMD_1.27X0.635MM_NO_SILK"))
    )
    (comp (ref "JP1106")
      (value "M01PTH_SMD_1.27X0.635MM_NO_SILK")
      (footprint "eagle-import:1X01_SMD_1.27X0.635MM_NO_SILK")
      (libsource (lib "eagle-import") (part "M01PTH_SMD_1.27X0.635MM_NO_SILK"))
    )
    (comp (ref "JP1107")
      (value "M01PTH_SMD_1.27X0.635MM_NO_SILK")
      (footprint "eagle-import:1X01_SMD_1.27X0.635MM_NO_SILK")
      (libsource (lib "eagle-import") (part "M01PTH_SMD_1.27X0.635MM_NO_SILK"))
    )
    (comp (ref "JP1108")
      (value "M01PTH_SMD_1.27X0.635MM_NO_SILK")
      (footprint "eagle-import:1X01_SMD_1.27X0.635MM_NO_SILK")
      (libsource (lib "eagle-import") (part "M01PTH_SMD_1.27X0.635MM_NO_SILK"))
    )
    (comp (ref "JP1109")
      (value "M01PTH_SMD_1.27X0.635MM_NO_SILK")
      (footprint "eagle-import:1X01_SMD_1.27X0.635MM_NO_SILK")
      (libsource (lib "eagle-import") (part "M01PTH_SMD_1.27X0.635MM_NO_SILK"))
    )
    (comp (ref "JP1110")
      (value "M01PTH_SMD_1.27X0.635MM_NO_SILK")
      (footprint "eagle-import:1X01_SMD_1.27X0.635MM_NO_SILK")
      (libsource (lib "eagle-import") (part "M01PTH_SMD_1.27X0.635MM_NO_SILK"))
    )
    (comp (ref "JP1111")
      (value "M01PTH_SMD_1.27X0.635MM_NO_SILK")
      (footprint "eagle-import:1X01_SMD_1.27X0.635MM_NO_SILK")
      (libsource (lib "eagle-import") (part "M01PTH_SMD_1.27X0.635MM_NO_SILK"))
    )
    (comp (ref "JP1112")
      (value "M01PTH_SMD_1.27X0.635MM_NO_SILK")
      (footprint "eagle-import:1X01_SMD_1.27X0.635MM_NO_SILK")
      (libsource (lib "eagle-import") (part "M01PTH_SMD_1.27X0.635MM_NO_SILK"))
    )
    (comp (ref "JP1113")
      (value "M01PTH_SMD_1.27X0.635MM_NO_SILK")
      (footprint "eagle-import:1X01_SMD_1.27X0.635MM_NO_SILK")
      (libsource (lib "eagle-import") (part "M01PTH_SMD_1.27X0.635MM_NO_SILK"))
    )
    (comp (ref "JP1114")
      (value "M01PTH_SMD_1.27X0.635MM_NO_SILK")
      (footprint "eagle-import:1X01_SMD_1.27X0.635MM_NO_SILK")
      (libsource (lib "eagle-import") (part "M01PTH_SMD_1.27X0.635MM_NO_SILK"))
    )
    (comp (ref "JP1115")
      (value "M01PTH_SMD_1.27X0.635MM_NO_SILK")
      (footprint "eagle-import:1X01_SMD_1.27X0.635MM_NO_SILK")
      (libsource (lib "eagle-import") (part "M01PTH_SMD_1.27X0.635MM_NO_SILK"))
    )
    (comp (ref "JP1116")
      (value "M01PTH_SMD_1.27X0.635MM_NO_SILK")
      (footprint "eagle-import:1X01_SMD_1.27X0.635MM_NO_SILK")
      (libsource (lib "eagle-import") (part "M01PTH_SMD_1.27X0.635MM_NO_SILK"))
    )
    (comp (ref "JP1117")
      (value "M01PTH_SMD_1.27X0.635MM_NO_SILK")
      (footprint "eagle-import:1X01_SMD_1.27X0.635MM_NO_SILK")
      (libsource (lib "eagle-import") (part "M01PTH_SMD_1.27X0.635MM_NO_SILK"))
    )
    (comp (ref "JP1118")
      (value "M01PTH_SMD_1.27X0.635MM_NO_SILK")
      (footprint "eagle-import:1X01_SMD_1.27X0.635MM_NO_SILK")
      (libsource (lib "eagle-import") (part "M01PTH_SMD_1.27X0.635MM_NO_SILK"))
    )
    (comp (ref "JP1119")
      (value "M01PTH_SMD_1.27X0.635MM_NO_SILK")
      (footprint "eagle-import:1X01_SMD_1.27X0.635MM_NO_SILK")
      (libsource (lib "eagle-import") (part "M01PTH_SMD_1.27X0.635MM_NO_SILK"))
    )
    (comp (ref "JP1120")
      (value "M01PTH_SMD_1.27X0.635MM_NO_SILK")
      (footprint "eagle-import:1X01_SMD_1.27X0.635MM_NO_SILK")
      (libsource (lib "eagle-import") (part "M01PTH_SMD_1.27X0.635MM_NO_SILK"))
    )
    (comp (ref "JP1121")
      (value "M01PTH_SMD_1.27X0.635MM_NO_SILK")
      (footprint "eagle-import:1X01_SMD_1.27X0.635MM_NO_SILK")
      (libsource (lib "eagle-import") (part "M01PTH_SMD_1.27X0.635MM_NO_SILK"))
    )
    (comp (ref "JP1122")
      (value "M01PTH_SMD_1.27X0.635MM_NO_SILK")
      (footprint "eagle-import:1X01_SMD_1.27X0.635MM_NO_SILK")
      (libsource (lib "eagle-import") (part "M01PTH_SMD_1.27X0.635MM_NO_SILK"))
    )
    (comp (ref "JP1123")
      (value "M01PTH_SMD_1.27X0.635MM_NO_SILK")
      (footprint "eagle-import:1X01_SMD_1.27X0.635MM_NO_SILK")
      (libsource (lib "eagle-import") (part "M01PTH_SMD_1.27X0.635MM_NO_SILK"))
    )
    (comp (ref "JP1124")
      (value "M01PTH_SMD_1.27X0.635MM_NO_SILK")
      (footprint "eagle-import:1X01_SMD_1.27X0.635MM_NO_SILK")
      (libsource (lib "eagle-import") (part "M01PTH_SMD_1.27X0.635MM_NO_SILK"))
    )
    (comp (ref "JP1125")
      (value "M01PTH_SMD_1.27X0.635MM_NO_SILK")
      (footprint "eagle-import:1X01_SMD_1.27X0.635MM_NO_SILK")
      (libsource (lib "eagle-import") (part "M01PTH_SMD_1.27X0.635MM_NO_SILK"))
    )
    (comp (ref "JP1126")
      (value "M01PTH_SMD_1.27X0.635MM_NO_SILK")
      (footprint "eagle-import:1X01_SMD_1.27X0.635MM_NO_SILK")
      (libsource (lib "eagle-import") (part "M01PTH_SMD_1.27X0.635MM_NO_SILK"))
    )
    (comp (ref "JP1127")
      (value "M01PTH_SMD_1.27X0.635MM_NO_SILK")
      (footprint "eagle-import:1X01_SMD_1.27X0.635MM_NO_SILK")
      (libsource (lib "eagle-import") (part "M01PTH_SMD_1.27X0.635MM_NO_SILK"))
    )
    (comp (ref "JP1128")
      (value "M01PTH_SMD_1.27X0.635MM_NO_SILK")
      (footprint "eagle-import:1X01_SMD_1.27X0.635MM_NO_SILK")
      (libsource (lib "eagle-import") (part "M01PTH_SMD_1.27X0.635MM_NO_SILK"))
    )
    (comp (ref "JP1129")
      (value "M01PTH_SMD_1.27X0.635MM_NO_SILK")
      (footprint "eagle-import:1X01_SMD_1.27X0.635MM_NO_SILK")
      (libsource (lib "eagle-import") (part "M01PTH_SMD_1.27X0.635MM_NO_SILK"))
    )
    (comp (ref "JP1130")
      (value "M01PTH_SMD_1.27X0.635MM_NO_SILK")
      (footprint "eagle-import:1X01_SMD_1.27X0.635MM_NO_SILK")
      (libsource (lib "eagle-import") (part "M01PTH_SMD_1.27X0.635MM_NO_SILK"))
    )
    (comp (ref "JP1131")
      (value "M01PTH_SMD_1.27X0.635MM_NO_SILK")
      (footprint "eagle-import:1X01_SMD_1.27X0.635MM_NO_SILK")
      (libsource (lib "eagle-import") (part "M01PTH_SMD_1.27X0.635MM_NO_SILK"))
    )
    (comp (ref "JP1132")
      (value "M01PTH_SMD_1.27X0.635MM_NO_SILK")
      (footprint "eagle-import:1X01_SMD_1.27X0.635MM_NO_SILK")
      (libsource (lib "eagle-import") (part "M01PTH_SMD_1.27X0.635MM_NO_SILK"))
    )
    (comp (ref "JP1133")
      (value "M01PTH_SMD_1.27X0.635MM_NO_SILK")
      (footprint "eagle-import:1X01_SMD_1.27X0.635MM_NO_SILK")
      (libsource (lib "eagle-import") (part "M01PTH_SMD_1.27X0.635MM_NO_SILK"))
    )
    (comp (ref "JP1134")
      (value "M01PTH_SMD_1.27X0.635MM_NO_SILK")
      (footprint "eagle-import:1X01_SMD_1.27X0.635MM_NO_SILK")
      (libsource (lib "eagle-import") (part "M01PTH_SMD_1.27X0.635MM_NO_SILK"))
    )
    (comp (ref "JP1135")
      (value "M01PTH_SMD_1.27X0.635MM_NO_SILK")
      (footprint "eagle-import:1X01_SMD_1.27X0.635MM_NO_SILK")
      (libsource (lib "eagle-import") (part "M01PTH_SMD_1.27X0.635MM_NO_SILK"))
    )
    (comp (ref "JP1136")
      (value "M01PTH_SMD_1.27X0.635MM_NO_SILK")
      (footprint "eagle-import:1X01_SMD_1.27X0.635MM_NO_SILK")
      (libsource (lib "eagle-import") (part "M01PTH_SMD_1.27X0.635MM_NO_SILK"))
    )
    (comp (ref "JP1137")
      (value "M01PTH_SMD_1.27X0.635MM_NO_SILK")
      (footprint "eagle-import:1X01_SMD_1.27X0.635MM_NO_SILK")
      (libsource (lib "eagle-import") (part "M01PTH_SMD_1.27X0.635MM_NO_SILK"))
    )
    (comp (ref "JP1138")
      (value "M01PTH_SMD_1.27X0.635MM_NO_SILK")
      (footprint "eagle-import:1X01_SMD_1.27X0.635MM_NO_SILK")
      (libsource (lib "eagle-import") (part "M01PTH_SMD_1.27X0.635MM_NO_SILK"))
    )
    (comp (ref "JP1139")
      (value "M01PTH_SMD_1.27X0.635MM_NO_SILK")
      (footprint "eagle-import:1X01_SMD_1.27X0.635MM_NO_SILK")
      (libsource (lib "eagle-import") (part "M01PTH_SMD_1.27X0.635MM_NO_SILK"))
    )
    (comp (ref "JP1140")
      (value "M01PTH_SMD_1.27X0.635MM_NO_SILK")
      (footprint "eagle-import:1X01_SMD_1.27X0.635MM_NO_SILK")
      (libsource (lib "eagle-import") (part "M01PTH_SMD_1.27X0.635MM_NO_SILK"))
    )
    (comp (ref "JP1141")
      (value "M01PTH_SMD_1.27X0.635MM_NO_SILK")
      (footprint "eagle-import:1X01_SMD_1.27X0.635MM_NO_SILK")
      (libsource (lib "eagle-import") (part "M01PTH_SMD_1.27X0.635MM_NO_SILK"))
    )
    (comp (ref "JP1142")
      (value "M01PTH_SMD_1.27X0.635MM_NO_SILK")
      (footprint "eagle-import:1X01_SMD_1.27X0.635MM_NO_SILK")
      (libsource (lib "eagle-import") (part "M01PTH_SMD_1.27X0.635MM_NO_SILK"))
    )
    (comp (ref "JP1143")
      (value "M01PTH_SMD_1.27X0.635MM_NO_SILK")
      (footprint "eagle-import:1X01_SMD_1.27X0.635MM_NO_SILK")
      (libsource (lib "eagle-import") (part "M01PTH_SMD_1.27X0.635MM_NO_SILK"))
    )
    (comp (ref "JP1144")
      (value "M01PTH_SMD_1.27X0.635MM_NO_SILK")
      (footprint "eagle-import:1X01_SMD_1.27X0.635MM_NO_SILK")
      (libsource (lib "eagle-import") (part "M01PTH_SMD_1.27X0.635MM_NO_SILK"))
    )
    (comp (ref "JP1145")
      (value "M01PTH_SMD_1.27X0.635MM_NO_SILK")
      (footprint "eagle-import:1X01_SMD_1.27X0.635MM_NO_SILK")
      (libsource (lib "eagle-import") (part "M01PTH_SMD_1.27X0.635MM_NO_SILK"))
    )
    (comp (ref "JP1146")
      (value "M01PTH_SMD_1.27X0.635MM_NO_SILK")
      (footprint "eagle-import:1X01_SMD_1.27X0.635MM_NO_SILK")
      (libsource (lib "eagle-import") (part "M01PTH_SMD_1.27X0.635MM_NO_SILK"))
    )
    (comp (ref "JP1147")
      (value "M01PTH_SMD_1.27X0.635MM_NO_SILK")
      (footprint "eagle-import:1X01_SMD_1.27X0.635MM_NO_SILK")
      (libsource (lib "eagle-import") (part "M01PTH_SMD_1.27X0.635MM_NO_SILK"))
    )
    (comp (ref "JP1148")
      (value "M01PTH_SMD_1.27X0.635MM_NO_SILK")
      (footprint "eagle-import:1X01_SMD_1.27X0.635MM_NO_SILK")
      (libsource (lib "eagle-import") (part "M01PTH_SMD_1.27X0.635MM_NO_SILK"))
    )
    (comp (ref "JP1149")
      (value "M01PTH_SMD_1.27X0.635MM_NO_SILK")
      (footprint "eagle-import:1X01_SMD_1.27X0.635MM_NO_SILK")
      (libsource (lib "eagle-import") (part "M01PTH_SMD_1.27X0.635MM_NO_SILK"))
    )
    (comp (ref "JP1150")
      (value "M01PTH_SMD_1.27X0.635MM_NO_SILK")
      (footprint "eagle-import:1X01_SMD_1.27X0.635MM_NO_SILK")
      (libsource (lib "eagle-import") (part "M01PTH_SMD_1.27X0.635MM_NO_SILK"))
    )
    (comp (ref "JP1151")
      (value "M01PTH_SMD_1.27X0.635MM_NO_SILK")
      (footprint "eagle-import:1X01_SMD_1.27X0.635MM_NO_SILK")
      (libsource (lib "eagle-import") (part "M01PTH_SMD_1.27X0.635MM_NO_SILK"))
    )
    (comp (ref "JP1152")
      (value "M01PTH_SMD_1.27X0.635MM_NO_SILK")
      (footprint "eagle-import:1X01_SMD_1.27X0.635MM_NO_SILK")
      (libsource (lib "eagle-import") (part "M01PTH_SMD_1.27X0.635MM_NO_SILK"))
    )
    (comp (ref "JP1153")
      (value "M01PTH_SMD_1.27X0.635MM_NO_SILK")
      (footprint "eagle-import:1X01_SMD_1.27X0.635MM_NO_SILK")
      (libsource (lib "eagle-import") (part "M01PTH_SMD_1.27X0.635MM_NO_SILK"))
    )
    (comp (ref "JP1154")
      (value "M01PTH_SMD_1.27X0.635MM_NO_SILK")
      (footprint "eagle-import:1X01_SMD_1.27X0.635MM_NO_SILK")
      (libsource (lib "eagle-import") (part "M01PTH_SMD_1.27X0.635MM_NO_SILK"))
    )
    (comp (ref "JP1155")
      (value "M01PTH_SMD_1.27X0.635MM_NO_SILK")
      (footprint "eagle-import:1X01_SMD_1.27X0.635MM_NO_SILK")
      (libsource (lib "eagle-import") (part "M01PTH_SMD_1.27X0.635MM_NO_SILK"))
    )
    (comp (ref "JP1156")
      (value "M01PTH_SMD_1.27X0.635MM_NO_SILK")
      (footprint "eagle-import:1X01_SMD_1.27X0.635MM_NO_SILK")
      (libsource (lib "eagle-import") (part "M01PTH_SMD_1.27X0.635MM_NO_SILK"))
    )
    (comp (ref "JP1157")
      (value "M01PTH_SMD_1.27X0.635MM_NO_SILK")
      (footprint "eagle-import:1X01_SMD_1.27X0.635MM_NO_SILK")
      (libsource (lib "eagle-import") (part "M01PTH_SMD_1.27X0.635MM_NO_SILK"))
    )
    (comp (ref "JP1158")
      (value "M01PTH_SMD_1.27X0.635MM_NO_SILK")
      (footprint "eagle-import:1X01_SMD_1.27X0.635MM_NO_SILK")
      (libsource (lib "eagle-import") (part "M01PTH_SMD_1.27X0.635MM_NO_SILK"))
    )
    (comp (ref "JP1159")
      (value "M01PTH_SMD_1.27X0.635MM_NO_SILK")
      (footprint "eagle-import:1X01_SMD_1.27X0.635MM_NO_SILK")
      (libsource (lib "eagle-import") (part "M01PTH_SMD_1.27X0.635MM_NO_SILK"))
    )
    (comp (ref "JP1160")
      (value "M01PTH_SMD_1.27X0.635MM_NO_SILK")
      (footprint "eagle-import:1X01_SMD_1.27X0.635MM_NO_SILK")
      (libsource (lib "eagle-import") (part "M01PTH_SMD_1.27X0.635MM_NO_SILK"))
    )
    (comp (ref "JP1161")
      (value "M01PTH_SMD_1.27X0.635MM_NO_SILK")
      (footprint "eagle-import:1X01_SMD_1.27X0.635MM_NO_SILK")
      (libsource (lib "eagle-import") (part "M01PTH_SMD_1.27X0.635MM_NO_SILK"))
    )
    (comp (ref "JP1162")
      (value "M01PTH_SMD_1.27X0.635MM_NO_SILK")
      (footprint "eagle-import:1X01_SMD_1.27X0.635MM_NO_SILK")
      (libsource (lib "eagle-import") (part "M01PTH_SMD_1.27X0.635MM_NO_SILK"))
    )
    (comp (ref "JP1163")
      (value "M01PTH_SMD_1.27X0.635MM_NO_SILK")
      (footprint "eagle-import:1X01_SMD_1.27X0.635MM_NO_SILK")
      (libsource (lib "eagle-import") (part "M01PTH_SMD_1.27X0.635MM_NO_SILK"))
    )
    (comp (ref "JP1164")
      (value "M01PTH_SMD_1.27X0.635MM_NO_SILK")
      (footprint "eagle-import:1X01_SMD_1.27X0.635MM_NO_SILK")
      (libsource (lib "eagle-import") (part "M01PTH_SMD_1.27X0.635MM_NO_SILK"))
    )
    (comp (ref "JP1165")
      (value "M01PTH_SMD_1.27X0.635MM_NO_SILK")
      (footprint "eagle-import:1X01_SMD_1.27X0.635MM_NO_SILK")
      (libsource (lib "eagle-import") (part "M01PTH_SMD_1.27X0.635MM_NO_SILK"))
    )
    (comp (ref "JP1166")
      (value "M01PTH_SMD_1.27X0.635MM_NO_SILK")
      (footprint "eagle-import:1X01_SMD_1.27X0.635MM_NO_SILK")
      (libsource (lib "eagle-import") (part "M01PTH_SMD_1.27X0.635MM_NO_SILK"))
    )
    (comp (ref "JP1167")
      (value "M01PTH_SMD_1.27X0.635MM_NO_SILK")
      (footprint "eagle-import:1X01_SMD_1.27X0.635MM_NO_SILK")
      (libsource (lib "eagle-import") (part "M01PTH_SMD_1.27X0.635MM_NO_SILK"))
    )
    (comp (ref "JP1168")
      (value "M01PTH_SMD_1.27X0.635MM_NO_SILK")
      (footprint "eagle-import:1X01_SMD_1.27X0.635MM_NO_SILK")
      (libsource (lib "eagle-import") (part "M01PTH_SMD_1.27X0.635MM_NO_SILK"))
    )
    (comp (ref "JP1169")
      (value "M01PTH_SMD_1.27X0.635MM_NO_SILK")
      (footprint "eagle-import:1X01_SMD_1.27X0.635MM_NO_SILK")
      (libsource (lib "eagle-import") (part "M01PTH_SMD_1.27X0.635MM_NO_SILK"))
    )
    (comp (ref "JP1170")
      (value "M01PTH_SMD_1.27X0.635MM_NO_SILK")
      (footprint "eagle-import:1X01_SMD_1.27X0.635MM_NO_SILK")
      (libsource (lib "eagle-import") (part "M01PTH_SMD_1.27X0.635MM_NO_SILK"))
    )
    (comp (ref "JP1171")
      (value "M01PTH_SMD_1.27X0.635MM_NO_SILK")
      (footprint "eagle-import:1X01_SMD_1.27X0.635MM_NO_SILK")
      (libsource (lib "eagle-import") (part "M01PTH_SMD_1.27X0.635MM_NO_SILK"))
    )
    (comp (ref "JP1172")
      (value "M01PTH_SMD_1.27X0.635MM_NO_SILK")
      (footprint "eagle-import:1X01_SMD_1.27X0.635MM_NO_SILK")
      (libsource (lib "eagle-import") (part "M01PTH_SMD_1.27X0.635MM_NO_SILK"))
    )
    (comp (ref "JP1173")
      (value "M01PTH_SMD_1.27X0.635MM_NO_SILK")
      (footprint "eagle-import:1X01_SMD_1.27X0.635MM_NO_SILK")
      (libsource (lib "eagle-import") (part "M01PTH_SMD_1.27X0.635MM_NO_SILK"))
    )
    (comp (ref "JP1174")
      (value "M01PTH_SMD_1.27X0.635MM_NO_SILK")
      (footprint "eagle-import:1X01_SMD_1.27X0.635MM_NO_SILK")
      (libsource (lib "eagle-import") (part "M01PTH_SMD_1.27X0.635MM_NO_SILK"))
    )
    (comp (ref "JP1175")
      (value "M01PTH_SMD_1.27X0.635MM_NO_SILK")
      (footprint "eagle-import:1X01_SMD_1.27X0.635MM_NO_SILK")
      (libsource (lib "eagle-import") (part "M01PTH_SMD_1.27X0.635MM_NO_SILK"))
    )
    (comp (ref "JP1176")
      (value "M01PTH_SMD_1.27X0.635MM_NO_SILK")
      (footprint "eagle-import:1X01_SMD_1.27X0.635MM_NO_SILK")
      (libsource (lib "eagle-import") (part "M01PTH_SMD_1.27X0.635MM_NO_SILK"))
    )
    (comp (ref "JP1177")
      (value "M01PTH_SMD_1.27X0.635MM_NO_SILK")
      (footprint "eagle-import:1X01_SMD_1.27X0.635MM_NO_SILK")
      (libsource (lib "eagle-import") (part "M01PTH_SMD_1.27X0.635MM_NO_SILK"))
    )
    (comp (ref "JP1178")
      (value "M01PTH_SMD_1.27X0.635MM_NO_SILK")
      (footprint "eagle-import:1X01_SMD_1.27X0.635MM_NO_SILK")
      (libsource (lib "eagle-import") (part "M01PTH_SMD_1.27X0.635MM_NO_SILK"))
    )
    (comp (ref "JP1179")
      (value "M01PTH_SMD_1.27X0.635MM_NO_SILK")
      (footprint "eagle-import:1X01_SMD_1.27X0.635MM_NO_SILK")
      (libsource (lib "eagle-import") (part "M01PTH_SMD_1.27X0.635MM_NO_SILK"))
    )
    (comp (ref "JP1180")
      (value "M01PTH_SMD_1.27X0.635MM_NO_SILK")
      (footprint "eagle-import:1X01_SMD_1.27X0.635MM_NO_SILK")
      (libsource (lib "eagle-import") (part "M01PTH_SMD_1.27X0.635MM_NO_SILK"))
    )
    (comp (ref "JP1181")
      (value "M01PTH_SMD_1.27X0.635MM_NO_SILK")
      (footprint "eagle-import:1X01_SMD_1.27X0.635MM_NO_SILK")
      (libsource (lib "eagle-import") (part "M01PTH_SMD_1.27X0.635MM_NO_SILK"))
    )
    (comp (ref "JP1182")
      (value "M01PTH_SMD_1.27X0.635MM_NO_SILK")
      (footprint "eagle-import:1X01_SMD_1.27X0.635MM_NO_SILK")
      (libsource (lib "eagle-import") (part "M01PTH_SMD_1.27X0.635MM_NO_SILK"))
    )
    (comp (ref "JP1183")
      (value "M01PTH_SMD_1.27X0.635MM_NO_SILK")
      (footprint "eagle-import:1X01_SMD_1.27X0.635MM_NO_SILK")
      (libsource (lib "eagle-import") (part "M01PTH_SMD_1.27X0.635MM_NO_SILK"))
    )
    (comp (ref "JP1184")
      (value "M01PTH_SMD_1.27X0.635MM_NO_SILK")
      (footprint "eagle-import:1X01_SMD_1.27X0.635MM_NO_SILK")
      (libsource (lib "eagle-import") (part "M01PTH_SMD_1.27X0.635MM_NO_SILK"))
    )
    (comp (ref "JP1185")
      (value "M01PTH_SMD_1.27X0.635MM_NO_SILK")
      (footprint "eagle-import:1X01_SMD_1.27X0.635MM_NO_SILK")
      (libsource (lib "eagle-import") (part "M01PTH_SMD_1.27X0.635MM_NO_SILK"))
    )
    (comp (ref "JP1186")
      (value "M01PTH_SMD_1.27X0.635MM_NO_SILK")
      (footprint "eagle-import:1X01_SMD_1.27X0.635MM_NO_SILK")
      (libsource (lib "eagle-import") (part "M01PTH_SMD_1.27X0.635MM_NO_SILK"))
    )
    (comp (ref "JP1187")
      (value "M01PTH_SMD_1.27X0.635MM_NO_SILK")
      (footprint "eagle-import:1X01_SMD_1.27X0.635MM_NO_SILK")
      (libsource (lib "eagle-import") (part "M01PTH_SMD_1.27X0.635MM_NO_SILK"))
    )
    (comp (ref "JP1188")
      (value "M01PTH_SMD_1.27X0.635MM_NO_SILK")
      (footprint "eagle-import:1X01_SMD_1.27X0.635MM_NO_SILK")
      (libsource (lib "eagle-import") (part "M01PTH_SMD_1.27X0.635MM_NO_SILK"))
    )
    (comp (ref "JP1189")
      (value "M01PTH_SMD_1.27X0.635MM_NO_SILK")
      (footprint "eagle-import:1X01_SMD_1.27X0.635MM_NO_SILK")
      (libsource (lib "eagle-import") (part "M01PTH_SMD_1.27X0.635MM_NO_SILK"))
    )
    (comp (ref "JP1190")
      (value "M01PTH_SMD_1.27X0.635MM_NO_SILK")
      (footprint "eagle-import:1X01_SMD_1.27X0.635MM_NO_SILK")
      (libsource (lib "eagle-import") (part "M01PTH_SMD_1.27X0.635MM_NO_SILK"))
    )
    (comp (ref "JP1191")
      (value "M01PTH_SMD_1.27X0.635MM_NO_SILK")
      (footprint "eagle-import:1X01_SMD_1.27X0.635MM_NO_SILK")
      (libsource (lib "eagle-import") (part "M01PTH_SMD_1.27X0.635MM_NO_SILK"))
    )
    (comp (ref "JP1192")
      (value "M01PTH_SMD_1.27X0.635MM_NO_SILK")
      (footprint "eagle-import:1X01_SMD_1.27X0.635MM_NO_SILK")
      (libsource (lib "eagle-import") (part "M01PTH_SMD_1.27X0.635MM_NO_SILK"))
    )
    (comp (ref "JP1193")
      (value "M01PTH_SMD_1.27X0.635MM_NO_SILK")
      (footprint "eagle-import:1X01_SMD_1.27X0.635MM_NO_SILK")
      (libsource (lib "eagle-import") (part "M01PTH_SMD_1.27X0.635MM_NO_SILK"))
    )
    (comp (ref "JP1194")
      (value "M01PTH_SMD_1.27X0.635MM_NO_SILK")
      (footprint "eagle-import:1X01_SMD_1.27X0.635MM_NO_SILK")
      (libsource (lib "eagle-import") (part "M01PTH_SMD_1.27X0.635MM_NO_SILK"))
    )
    (comp (ref "JP1195")
      (value "M01PTH_SMD_1.27X0.635MM_NO_SILK")
      (footprint "eagle-import:1X01_SMD_1.27X0.635MM_NO_SILK")
      (libsource (lib "eagle-import") (part "M01PTH_SMD_1.27X0.635MM_NO_SILK"))
    )
    (comp (ref "JP1196")
      (value "M01PTH_SMD_1.27X0.635MM_NO_SILK")
      (footprint "eagle-import:1X01_SMD_1.27X0.635MM_NO_SILK")
      (libsource (lib "eagle-import") (part "M01PTH_SMD_1.27X0.635MM_NO_SILK"))
    )
    (comp (ref "JP1197")
      (value "M01PTH_SMD_1.27X0.635MM_NO_SILK")
      (footprint "eagle-import:1X01_SMD_1.27X0.635MM_NO_SILK")
      (libsource (lib "eagle-import") (part "M01PTH_SMD_1.27X0.635MM_NO_SILK"))
    )
    (comp (ref "JP1198")
      (value "M01PTH_SMD_1.27X0.635MM_NO_SILK")
      (footprint "eagle-import:1X01_SMD_1.27X0.635MM_NO_SILK")
      (libsource (lib "eagle-import") (part "M01PTH_SMD_1.27X0.635MM_NO_SILK"))
    )
    (comp (ref "JP1199")
      (value "M01PTH_SMD_1.27X0.635MM_NO_SILK")
      (footprint "eagle-import:1X01_SMD_1.27X0.635MM_NO_SILK")
      (libsource (lib "eagle-import") (part "M01PTH_SMD_1.27X0.635MM_NO_SILK"))
    )
    (comp (ref "JP1200")
      (value "M01PTH_SMD_1.27X0.635MM_NO_SILK")
      (footprint "eagle-import:1X01_SMD_1.27X0.635MM_NO_SILK")
      (libsource (lib "eagle-import") (part "M01PTH_SMD_1.27X0.635MM_NO_SILK"))
    )
  )
  (nets
    (net (code "1") (name "/0_1439385713") (class "Default")
      (node (ref "JP1") (pin "1") (pinfunction "1_1") (pintype "passive"))
      (node (ref "JP961") (pin "P$2") (pinfunction "1_P$2") (pintype "passive"))
    )
    (net (code "2") (name "/0_1439385741") (class "Default")
      (node (ref "JP1141") (pin "P$2") (pinfunction "1_P$2") (pintype "passive"))
      (node (ref "JP2") (pin "1") (pinfunction "1_1") (pintype "passive"))
    )
    (net (code "3") (name "/0_1439385772") (class "Default")
      (node (ref "JP63") (pin "1") (pinfunction "1_1") (pintype "passive"))
      (node (ref "JP901") (pin "P$2") (pinfunction "1_P$2") (pintype "passive"))
    )
    (net (code "4") (name "/0_1439385798") (class "Default")
      (node (ref "JP10") (pin "1") (pinfunction "1_1") (pintype "passive"))
      (node (ref "JP1021") (pin "P$2") (pinfunction "1_P$2") (pintype "passive"))
    )
    (net (code "5") (name "/0_1439385823") (class "Default")
      (node (ref "JP1161") (pin "P$2") (pinfunction "1_P$2") (pintype "passive"))
      (node (ref "JP6") (pin "1") (pinfunction "1_1") (pintype "passive"))
    )
    (net (code "6") (name "/0_1439385849") (class "Default")
      (node (ref "JP1081") (pin "P$2") (pinfunction "1_P$2") (pintype "passive"))
      (node (ref "JP68") (pin "1") (pinfunction "1_1") (pintype "passive"))
    )
    (net (code "7") (name "/1_1439385713") (class "Default")
      (node (ref "JP11") (pin "1") (pinfunction "1_1") (pintype "passive"))
      (node (ref "JP962") (pin "P$2") (pinfunction "1_P$2") (pintype "passive"))
    )
    (net (code "8") (name "/1_1439385741") (class "Default")
      (node (ref "JP1142") (pin "P$2") (pinfunction "1_P$2") (pintype "passive"))
      (node (ref "JP3") (pin "1") (pinfunction "1_1") (pintype "passive"))
    )
    (net (code "9") (name "/1_1439385772") (class "Default")
      (node (ref "JP73") (pin "1") (pinfunction "1_1") (pintype "passive"))
      (node (ref "JP902") (pin "P$2") (pinfunction "1_P$2") (pintype "passive"))
    )
    (net (code "10") (name "/1_1439385798") (class "Default")
      (node (ref "JP1022") (pin "P$2") (pinfunction "1_P$2") (pintype "passive"))
      (node (ref "JP20") (pin "1") (pinfunction "1_1") (pintype "passive"))
    )
    (net (code "11") (name "/1_1439385823") (class "Default")
      (node (ref "JP1162") (pin "P$2") (pinfunction "1_P$2") (pintype "passive"))
      (node (ref "JP7") (pin "1") (pinfunction "1_1") (pintype "passive"))
    )
    (net (code "12") (name "/1_1439385849") (class "Default")
      (node (ref "JP1082") (pin "P$2") (pinfunction "1_P$2") (pintype "passive"))
      (node (ref "JP78") (pin "1") (pinfunction "1_1") (pintype "passive"))
    )
    (net (code "13") (name "/2_1439385713") (class "Default")
      (node (ref "JP21") (pin "1") (pinfunction "1_1") (pintype "passive"))
      (node (ref "JP963") (pin "P$2") (pinfunction "1_P$2") (pintype "passive"))
    )
    (net (code "14") (name "/2_1439385741") (class "Default")
      (node (ref "JP1143") (pin "P$2") (pinfunction "1_P$2") (pintype "passive"))
      (node (ref "JP4") (pin "1") (pinfunction "1_1") (pintype "passive"))
    )
    (net (code "15") (name "/2_1439385772") (class "Default")
      (node (ref "JP64") (pin "1") (pinfunction "1_1") (pintype "passive"))
      (node (ref "JP903") (pin "P$2") (pinfunction "1_P$2") (pintype "passive"))
    )
    (net (code "16") (name "/2_1439385798") (class "Default")
      (node (ref "JP1023") (pin "P$2") (pinfunction "1_P$2") (pintype "passive"))
      (node (ref "JP30") (pin "1") (pinfunction "1_1") (pintype "passive"))
    )
    (net (code "17") (name "/2_1439385823") (class "Default")
      (node (ref "JP1163") (pin "P$2") (pinfunction "1_P$2") (pintype "passive"))
      (node (ref "JP8") (pin "1") (pinfunction "1_1") (pintype "passive"))
    )
    (net (code "18") (name "/2_1439385849") (class "Default")
      (node (ref "JP1083") (pin "P$2") (pinfunction "1_P$2") (pintype "passive"))
      (node (ref "JP67") (pin "1") (pinfunction "1_1") (pintype "passive"))
    )
    (net (code "19") (name "/3_1439385713") (class "Default")
      (node (ref "JP31") (pin "1") (pinfunction "1_1") (pintype "passive"))
      (node (ref "JP964") (pin "P$2") (pinfunction "1_P$2") (pintype "passive"))
    )
    (net (code "20") (name "/3_1439385741") (class "Default")
      (node (ref "JP1144") (pin "P$2") (pinfunction "1_P$2") (pintype "passive"))
      (node (ref "JP5") (pin "1") (pinfunction "1_1") (pintype "passive"))
    )
    (net (code "21") (name "/3_1439385772") (class "Default")
      (node (ref "JP83") (pin "1") (pinfunction "1_1") (pintype "passive"))
      (node (ref "JP904") (pin "P$2") (pinfunction "1_P$2") (pintype "passive"))
    )
    (net (code "22") (name "/3_1439385798") (class "Default")
      (node (ref "JP1024") (pin "P$2") (pinfunction "1_P$2") (pintype "passive"))
      (node (ref "JP40") (pin "1") (pinfunction "1_1") (pintype "passive"))
    )
    (net (code "23") (name "/3_1439385823") (class "Default")
      (node (ref "JP1164") (pin "P$2") (pinfunction "1_P$2") (pintype "passive"))
      (node (ref "JP9") (pin "1") (pinfunction "1_1") (pintype "passive"))
    )
    (net (code "24") (name "/3_1439385849") (class "Default")
      (node (ref "JP1084") (pin "P$2") (pinfunction "1_P$2") (pintype "passive"))
      (node (ref "JP88") (pin "1") (pinfunction "1_1") (pintype "passive"))
    )
    (net (code "25") (name "/4_1439385713") (class "Default")
      (node (ref "JP41") (pin "1") (pinfunction "1_1") (pintype "passive"))
      (node (ref "JP965") (pin "P$2") (pinfunction "1_P$2") (pintype "passive"))
    )
    (net (code "26") (name "/4_1439385741") (class "Default")
      (node (ref "JP1145") (pin "P$2") (pinfunction "1_P$2") (pintype "passive"))
      (node (ref "JP13") (pin "1") (pinfunction "1_1") (pintype "passive"))
    )
    (net (code "27") (name "/4_1439385772") (class "Default")
      (node (ref "JP74") (pin "1") (pinfunction "1_1") (pintype "passive"))
      (node (ref "JP905") (pin "P$2") (pinfunction "1_P$2") (pintype "passive"))
    )
    (net (code "28") (name "/4_1439385798") (class "Default")
      (node (ref "JP1025") (pin "P$2") (pinfunction "1_P$2") (pintype "passive"))
      (node (ref "JP50") (pin "1") (pinfunction "1_1") (pintype "passive"))
    )
    (net (code "29") (name "/4_1439385823") (class "Default")
      (node (ref "JP1165") (pin "P$2") (pinfunction "1_P$2") (pintype "passive"))
      (node (ref "JP18") (pin "1") (pinfunction "1_1") (pintype "passive"))
    )
    (net (code "30") (name "/4_1439385849") (class "Default")
      (node (ref "JP1085") (pin "P$2") (pinfunction "1_P$2") (pintype "passive"))
      (node (ref "JP77") (pin "1") (pinfunction "1_1") (pintype "passive"))
    )
    (net (code "31") (name "/5_1439385713") (class "Default")
      (node (ref "JP22") (pin "1") (pinfunction "1_1") (pintype "passive"))
      (node (ref "JP966") (pin "P$2") (pinfunction "1_P$2") (pintype "passive"))
    )
    (net (code "32") (name "/5_1439385741") (class "Default")
      (node (ref "JP1146") (pin "P$2") (pinfunction "1_P$2") (pintype "passive"))
      (node (ref "JP14") (pin "1") (pinfunction "1_1") (pintype "passive"))
    )
    (net (code "33") (name "/5_1439385772") (class "Default")
      (node (ref "JP65") (pin "1") (pinfunction "1_1") (pintype "passive"))
      (node (ref "JP906") (pin "P$2") (pinfunction "1_P$2") (pintype "passive"))
    )
    (net (code "34") (name "/5_1439385798") (class "Default")
      (node (ref "JP1026") (pin "P$2") (pinfunction "1_P$2") (pintype "passive"))
      (node (ref "JP29") (pin "1") (pinfunction "1_1") (pintype "passive"))
    )
    (net (code "35") (name "/5_1439385823") (class "Default")
      (node (ref "JP1166") (pin "P$2") (pinfunction "1_P$2") (pintype "passive"))
      (node (ref "JP19") (pin "1") (pinfunction "1_1") (pintype "passive"))
    )
    (net (code "36") (name "/5_1439385849") (class "Default")
      (node (ref "JP1086") (pin "P$2") (pinfunction "1_P$2") (pintype "passive"))
      (node (ref "JP66") (pin "1") (pinfunction "1_1") (pintype "passive"))
    )
    (net (code "37") (name "/6_1439385713") (class "Default")
      (node (ref "JP51") (pin "1") (pinfunction "1_1") (pintype "passive"))
      (node (ref "JP967") (pin "P$2") (pinfunction "1_P$2") (pintype "passive"))
    )
    (net (code "38") (name "/6_1439385741") (class "Default")
      (node (ref "JP1147") (pin "P$2") (pinfunction "1_P$2") (pintype "passive"))
      (node (ref "JP15") (pin "1") (pinfunction "1_1") (pintype "passive"))
    )
    (net (code "39") (name "/6_1439385772") (class "Default")
      (node (ref "JP907") (pin "P$2") (pinfunction "1_P$2") (pintype "passive"))
      (node (ref "JP93") (pin "1") (pinfunction "1_1") (pintype "passive"))
    )
    (net (code "40") (name "/6_1439385798") (class "Default")
      (node (ref "JP1027") (pin "P$2") (pinfunction "1_P$2") (pintype "passive"))
      (node (ref "JP60") (pin "1") (pinfunction "1_1") (pintype "passive"))
    )
    (net (code "41") (name "/6_1439385823") (class "Default")
      (node (ref "JP1167") (pin "P$2") (pinfunction "1_P$2") (pintype "passive"))
      (node (ref "JP17") (pin "1") (pinfunction "1_1") (pintype "passive"))
    )
    (net (code "42") (name "/6_1439385849") (class "Default")
      (node (ref "JP1087") (pin "P$2") (pinfunction "1_P$2") (pintype "passive"))
      (node (ref "JP98") (pin "1") (pinfunction "1_1") (pintype "passive"))
    )
    (net (code "43") (name "/7_1439385713") (class "Default")
      (node (ref "JP32") (pin "1") (pinfunction "1_1") (pintype "passive"))
      (node (ref "JP968") (pin "P$2") (pinfunction "1_P$2") (pintype "passive"))
    )
    (net (code "44") (name "/7_1439385741") (class "Default")
      (node (ref "JP1148") (pin "P$2") (pinfunction "1_P$2") (pintype "passive"))
      (node (ref "JP12") (pin "1") (pinfunction "1_1") (pintype "passive"))
    )
    (net (code "45") (name "/7_1439385772") (class "Default")
      (node (ref "JP84") (pin "1") (pinfunction "1_1") (pintype "passive"))
      (node (ref "JP908") (pin "P$2") (pinfunction "1_P$2") (pintype "passive"))
    )
    (net (code "46") (name "/7_1439385798") (class "Default")
      (node (ref "JP1028") (pin "P$2") (pinfunction "1_P$2") (pintype "passive"))
      (node (ref "JP39") (pin "1") (pinfunction "1_1") (pintype "passive"))
    )
    (net (code "47") (name "/7_1439385823") (class "Default")
      (node (ref "JP1168") (pin "P$2") (pinfunction "1_P$2") (pintype "passive"))
      (node (ref "JP16") (pin "1") (pinfunction "1_1") (pintype "passive"))
    )
    (net (code "48") (name "/7_1439385849") (class "Default")
      (node (ref "JP1088") (pin "P$2") (pinfunction "1_P$2") (pintype "passive"))
      (node (ref "JP87") (pin "1") (pinfunction "1_1") (pintype "passive"))
    )
    (net (code "49") (name "/8_1439385713") (class "Default")
      (node (ref "JP61") (pin "1") (pinfunction "1_1") (pintype "passive"))
      (node (ref "JP969") (pin "P$2") (pinfunction "1_P$2") (pintype "passive"))
    )
    (net (code "50") (name "/8_1439385741") (class "Default")
      (node (ref "JP1149") (pin "P$2") (pinfunction "1_P$2") (pintype "passive"))
      (node (ref "JP25") (pin "1") (pinfunction "1_1") (pintype "passive"))
    )
    (net (code "51") (name "/8_1439385772") (class "Default")
      (node (ref "JP75") (pin "1") (pinfunction "1_1") (pintype "passive"))
      (node (ref "JP909") (pin "P$2") (pinfunction "1_P$2") (pintype "passive"))
    )
    (net (code "52") (name "/8_1439385798") (class "Default")
      (node (ref "JP1029") (pin "P$2") (pinfunction "1_P$2") (pintype "passive"))
      (node (ref "JP70") (pin "1") (pinfunction "1_1") (pintype "passive"))
    )
    (net (code "53") (name "/8_1439385823") (class "Default")
      (node (ref "JP1169") (pin "P$2") (pinfunction "1_P$2") (pintype "passive"))
      (node (ref "JP28") (pin "1") (pinfunction "1_1") (pintype "passive"))
    )
    (net (code "54") (name "/8_1439385849") (class "Default")
      (node (ref "JP1089") (pin "P$2") (pinfunction "1_P$2") (pintype "passive"))
      (node (ref "JP76") (pin "1") (pinfunction "1_1") (pintype "passive"))
    )
    (net (code "55") (name "/9_1439385713") (class "Default")
      (node (ref "JP42") (pin "1") (pinfunction "1_1") (pintype "passive"))
      (node (ref "JP970") (pin "P$2") (pinfunction "1_P$2") (pintype "passive"))
    )
    (net (code "56") (name "/9_1439385741") (class "Default")
      (node (ref "JP1150") (pin "P$2") (pinfunction "1_P$2") (pintype "passive"))
      (node (ref "JP24") (pin "1") (pinfunction "1_1") (pintype "passive"))
    )
    (net (code "57") (name "/9_1439385772") (class "Default")
      (node (ref "JP103") (pin "1") (pinfunction "1_1") (pintype "passive"))
      (node (ref "JP910") (pin "P$2") (pinfunction "1_P$2") (pintype "passive"))
    )
    (net (code "58") (name "/9_1439385798") (class "Default")
      (node (ref "JP1030") (pin "P$2") (pinfunction "1_P$2") (pintype "passive"))
      (node (ref "JP49") (pin "1") (pinfunction "1_1") (pintype "passive"))
    )
    (net (code "59") (name "/9_1439385823") (class "Default")
      (node (ref "JP1170") (pin "P$2") (pinfunction "1_P$2") (pintype "passive"))
      (node (ref "JP27") (pin "1") (pinfunction "1_1") (pintype "passive"))
    )
    (net (code "60") (name "/9_1439385849") (class "Default")
      (node (ref "JP108") (pin "1") (pinfunction "1_1") (pintype "passive"))
      (node (ref "JP1090") (pin "P$2") (pinfunction "1_P$2") (pintype "passive"))
    )
    (net (code "61") (name "/10_1439385713") (class "Default")
      (node (ref "JP71") (pin "1") (pinfunction "1_1") (pintype "passive"))
      (node (ref "JP971") (pin "P$2") (pinfunction "1_P$2") (pintype "passive"))
    )
    (net (code "62") (name "/10_1439385741") (class "Default")
      (node (ref "JP1151") (pin "P$2") (pinfunction "1_P$2") (pintype "passive"))
      (node (ref "JP23") (pin "1") (pinfunction "1_1") (pintype "passive"))
    )
    (net (code "63") (name "/10_1439385772") (class "Default")
      (node (ref "JP911") (pin "P$2") (pinfunction "1_P$2") (pintype "passive"))
      (node (ref "JP94") (pin "1") (pinfunction "1_1") (pintype "passive"))
    )
    (net (code "64") (name "/10_1439385798") (class "Default")
      (node (ref "JP1031") (pin "P$2") (pinfunction "1_P$2") (pintype "passive"))
      (node (ref "JP80") (pin "1") (pinfunction "1_1") (pintype "passive"))
    )
    (net (code "65") (name "/10_1439385823") (class "Default")
      (node (ref "JP1171") (pin "P$2") (pinfunction "1_P$2") (pintype "passive"))
      (node (ref "JP26") (pin "1") (pinfunction "1_1") (pintype "passive"))
    )
    (net (code "66") (name "/10_1439385849") (class "Default")
      (node (ref "JP1091") (pin "P$2") (pinfunction "1_P$2") (pintype "passive"))
      (node (ref "JP97") (pin "1") (pinfunction "1_1") (pintype "passive"))
    )
    (net (code "67") (name "/11_1439385713") (class "Default")
      (node (ref "JP52") (pin "1") (pinfunction "1_1") (pintype "passive"))
      (node (ref "JP972") (pin "P$2") (pinfunction "1_P$2") (pintype "passive"))
    )
    (net (code "68") (name "/11_1439385741") (class "Default")
      (node (ref "JP1152") (pin "P$2") (pinfunction "1_P$2") (pintype "passive"))
      (node (ref "JP33") (pin "1") (pinfunction "1_1") (pintype "passive"))
    )
    (net (code "69") (name "/11_1439385772") (class "Default")
      (node (ref "JP113") (pin "1") (pinfunction "1_1") (pintype "passive"))
      (node (ref "JP912") (pin "P$2") (pinfunction "1_P$2") (pintype "passive"))
    )
    (net (code "70") (name "/11_1439385798") (class "Default")
      (node (ref "JP1032") (pin "P$2") (pinfunction "1_P$2") (pintype "passive"))
      (node (ref "JP59") (pin "1") (pinfunction "1_1") (pintype "passive"))
    )
    (net (code "71") (name "/11_1439385823") (class "Default")
      (node (ref "JP1172") (pin "P$2") (pinfunction "1_P$2") (pintype "passive"))
      (node (ref "JP36") (pin "1") (pinfunction "1_1") (pintype "passive"))
    )
    (net (code "72") (name "/11_1439385849") (class "Default")
      (node (ref "JP1092") (pin "P$2") (pinfunction "1_P$2") (pintype "passive"))
      (node (ref "JP118") (pin "1") (pinfunction "1_1") (pintype "passive"))
    )
    (net (code "73") (name "/12_1439385713") (class "Default")
      (node (ref "JP81") (pin "1") (pinfunction "1_1") (pintype "passive"))
      (node (ref "JP973") (pin "P$2") (pinfunction "1_P$2") (pintype "passive"))
    )
    (net (code "74") (name "/12_1439385741") (class "Default")
      (node (ref "JP1153") (pin "P$2") (pinfunction "1_P$2") (pintype "passive"))
      (node (ref "JP34") (pin "1") (pinfunction "1_1") (pintype "passive"))
    )
    (net (code "75") (name "/12_1439385772") (class "Default")
      (node (ref "JP104") (pin "1") (pinfunction "1_1") (pintype "passive"))
      (node (ref "JP913") (pin "P$2") (pinfunction "1_P$2") (pintype "passive"))
    )
    (net (code "76") (name "/12_1439385798") (class "Default")
      (node (ref "JP1033") (pin "P$2") (pinfunction "1_P$2") (pintype "passive"))
      (node (ref "JP90") (pin "1") (pinfunction "1_1") (pintype "passive"))
    )
    (net (code "77") (name "/12_1439385823") (class "Default")
      (node (ref "JP1173") (pin "P$2") (pinfunction "1_P$2") (pintype "passive"))
      (node (ref "JP37") (pin "1") (pinfunction "1_1") (pintype "passive"))
    )
    (net (code "78") (name "/12_1439385849") (class "Default")
      (node (ref "JP107") (pin "1") (pinfunction "1_1") (pintype "passive"))
      (node (ref "JP1093") (pin "P$2") (pinfunction "1_P$2") (pintype "passive"))
    )
    (net (code "79") (name "/13_1439385713") (class "Default")
      (node (ref "JP62") (pin "1") (pinfunction "1_1") (pintype "passive"))
      (node (ref "JP974") (pin "P$2") (pinfunction "1_P$2") (pintype "passive"))
    )
    (net (code "80") (name "/13_1439385741") (class "Default")
      (node (ref "JP1154") (pin "P$2") (pinfunction "1_P$2") (pintype "passive"))
      (node (ref "JP35") (pin "1") (pinfunction "1_1") (pintype "passive"))
    )
    (net (code "81") (name "/13_1439385772") (class "Default")
      (node (ref "JP85") (pin "1") (pinfunction "1_1") (pintype "passive"))
      (node (ref "JP914") (pin "P$2") (pinfunction "1_P$2") (pintype "passive"))
    )
    (net (code "82") (name "/13_1439385798") (class "Default")
      (node (ref "JP1034") (pin "P$2") (pinfunction "1_P$2") (pintype "passive"))
      (node (ref "JP69") (pin "1") (pinfunction "1_1") (pintype "passive"))
    )
    (net (code "83") (name "/13_1439385823") (class "Default")
      (node (ref "JP1174") (pin "P$2") (pinfunction "1_P$2") (pintype "passive"))
      (node (ref "JP38") (pin "1") (pinfunction "1_1") (pintype "passive"))
    )
    (net (code "84") (name "/13_1439385849") (class "Default")
      (node (ref "JP1094") (pin "P$2") (pinfunction "1_P$2") (pintype "passive"))
      (node (ref "JP86") (pin "1") (pinfunction "1_1") (pintype "passive"))
    )
    (net (code "85") (name "/14_1439385713") (class "Default")
      (node (ref "JP91") (pin "1") (pinfunction "1_1") (pintype "passive"))
      (node (ref "JP975") (pin "P$2") (pinfunction "1_P$2") (pintype "passive"))
    )
    (net (code "86") (name "/14_1439385741") (class "Default")
      (node (ref "JP1155") (pin "P$2") (pinfunction "1_P$2") (pintype "passive"))
      (node (ref "JP43") (pin "1") (pinfunction "1_1") (pintype "passive"))
    )
    (net (code "87") (name "/14_1439385772") (class "Default")
      (node (ref "JP123") (pin "1") (pinfunction "1_1") (pintype "passive"))
      (node (ref "JP915") (pin "P$2") (pinfunction "1_P$2") (pintype "passive"))
    )
    (net (code "88") (name "/14_1439385798") (class "Default")
      (node (ref "JP100") (pin "1") (pinfunction "1_1") (pintype "passive"))
      (node (ref "JP1035") (pin "P$2") (pinfunction "1_P$2") (pintype "passive"))
    )
    (net (code "89") (name "/14_1439385823") (class "Default")
      (node (ref "JP1175") (pin "P$2") (pinfunction "1_P$2") (pintype "passive"))
      (node (ref "JP48") (pin "1") (pinfunction "1_1") (pintype "passive"))
    )
    (net (code "90") (name "/14_1439385849") (class "Default")
      (node (ref "JP1095") (pin "P$2") (pinfunction "1_P$2") (pintype "passive"))
      (node (ref "JP128") (pin "1") (pinfunction "1_1") (pintype "passive"))
    )
    (net (code "91") (name "/15_1439385713") (class "Default")
      (node (ref "JP72") (pin "1") (pinfunction "1_1") (pintype "passive"))
      (node (ref "JP976") (pin "P$2") (pinfunction "1_P$2") (pintype "passive"))
    )
    (net (code "92") (name "/15_1439385741") (class "Default")
      (node (ref "JP1156") (pin "P$2") (pinfunction "1_P$2") (pintype "passive"))
      (node (ref "JP44") (pin "1") (pinfunction "1_1") (pintype "passive"))
    )
    (net (code "93") (name "/15_1439385772") (class "Default")
      (node (ref "JP114") (pin "1") (pinfunction "1_1") (pintype "passive"))
      (node (ref "JP916") (pin "P$2") (pinfunction "1_P$2") (pintype "passive"))
    )
    (net (code "94") (name "/15_1439385798") (class "Default")
      (node (ref "JP1036") (pin "P$2") (pinfunction "1_P$2") (pintype "passive"))
      (node (ref "JP79") (pin "1") (pinfunction "1_1") (pintype "passive"))
    )
    (net (code "95") (name "/15_1439385823") (class "Default")
      (node (ref "JP1176") (pin "P$2") (pinfunction "1_P$2") (pintype "passive"))
      (node (ref "JP47") (pin "1") (pinfunction "1_1") (pintype "passive"))
    )
    (net (code "96") (name "/15_1439385849") (class "Default")
      (node (ref "JP1096") (pin "P$2") (pinfunction "1_P$2") (pintype "passive"))
      (node (ref "JP117") (pin "1") (pinfunction "1_1") (pintype "passive"))
    )
    (net (code "97") (name "/16_1439385713") (class "Default")
      (node (ref "JP101") (pin "1") (pinfunction "1_1") (pintype "passive"))
      (node (ref "JP977") (pin "P$2") (pinfunction "1_P$2") (pintype "passive"))
    )
    (net (code "98") (name "/16_1439385741") (class "Default")
      (node (ref "JP1157") (pin "P$2") (pinfunction "1_P$2") (pintype "passive"))
      (node (ref "JP45") (pin "1") (pinfunction "1_1") (pintype "passive"))
    )
    (net (code "99") (name "/16_1439385772") (class "Default")
      (node (ref "JP133") (pin "1") (pinfunction "1_1") (pintype "passive"))
      (node (ref "JP917") (pin "P$2") (pinfunction "1_P$2") (pintype "passive"))
    )
    (net (code "100") (name "/16_1439385798") (class "Default")
      (node (ref "JP1037") (pin "P$2") (pinfunction "1_P$2") (pintype "passive"))
      (node (ref "JP110") (pin "1") (pinfunction "1_1") (pintype "passive"))
    )
    (net (code "101") (name "/16_1439385823") (class "Default")
      (node (ref "JP1177") (pin "P$2") (pinfunction "1_P$2") (pintype "passive"))
      (node (ref "JP46") (pin "1") (pinfunction "1_1") (pintype "passive"))
    )
    (net (code "102") (name "/16_1439385849") (class "Default")
      (node (ref "JP1097") (pin "P$2") (pinfunction "1_P$2") (pintype "passive"))
      (node (ref "JP138") (pin "1") (pinfunction "1_1") (pintype "passive"))
    )
    (net (code "103") (name "/17_1439385713") (class "Default")
      (node (ref "JP82") (pin "1") (pinfunction "1_1") (pintype "passive"))
      (node (ref "JP978") (pin "P$2") (pinfunction "1_P$2") (pintype "passive"))
    )
    (net (code "104") (name "/17_1439385741") (class "Default")
      (node (ref "JP1158") (pin "P$2") (pinfunction "1_P$2") (pintype "passive"))
      (node (ref "JP54") (pin "1") (pinfunction "1_1") (pintype "passive"))
    )
    (net (code "105") (name "/17_1439385772") (class "Default")
      (node (ref "JP124") (pin "1") (pinfunction "1_1") (pintype "passive"))
      (node (ref "JP918") (pin "P$2") (pinfunction "1_P$2") (pintype "passive"))
    )
    (net (code "106") (name "/17_1439385798") (class "Default")
      (node (ref "JP1038") (pin "P$2") (pinfunction "1_P$2") (pintype "passive"))
      (node (ref "JP89") (pin "1") (pinfunction "1_1") (pintype "passive"))
    )
    (net (code "107") (name "/17_1439385823") (class "Default")
      (node (ref "JP1178") (pin "P$2") (pinfunction "1_P$2") (pintype "passive"))
      (node (ref "JP58") (pin "1") (pinfunction "1_1") (pintype "passive"))
    )
    (net (code "108") (name "/17_1439385849") (class "Default")
      (node (ref "JP1098") (pin "P$2") (pinfunction "1_P$2") (pintype "passive"))
      (node (ref "JP127") (pin "1") (pinfunction "1_1") (pintype "passive"))
    )
    (net (code "109") (name "/18_1439385713") (class "Default")
      (node (ref "JP111") (pin "1") (pinfunction "1_1") (pintype "passive"))
      (node (ref "JP979") (pin "P$2") (pinfunction "1_P$2") (pintype "passive"))
    )
    (net (code "110") (name "/18_1439385741") (class "Default")
      (node (ref "JP1159") (pin "P$2") (pinfunction "1_P$2") (pintype "passive"))
      (node (ref "JP55") (pin "1") (pinfunction "1_1") (pintype "passive"))
    )
    (net (code "111") (name "/18_1439385772") (class "Default")
      (node (ref "JP143") (pin "1") (pinfunction "1_1") (pintype "passive"))
      (node (ref "JP919") (pin "P$2") (pinfunction "1_P$2") (pintype "passive"))
    )
    (net (code "112") (name "/18_1439385798") (class "Default")
      (node (ref "JP1039") (pin "P$2") (pinfunction "1_P$2") (pintype "passive"))
      (node (ref "JP120") (pin "1") (pinfunction "1_1") (pintype "passive"))
    )
    (net (code "113") (name "/18_1439385823") (class "Default")
      (node (ref "JP1179") (pin "P$2") (pinfunction "1_P$2") (pintype "passive"))
      (node (ref "JP57") (pin "1") (pinfunction "1_1") (pintype "passive"))
    )
    (net (code "114") (name "/18_1439385849") (class "Default")
      (node (ref "JP1099") (pin "P$2") (pinfunction "1_P$2") (pintype "passive"))
      (node (ref "JP96") (pin "1") (pinfunction "1_1") (pintype "passive"))
    )
    (net (code "115") (name "/19_1439385713") (class "Default")
      (node (ref "JP92") (pin "1") (pinfunction "1_1") (pintype "passive"))
      (node (ref "JP980") (pin "P$2") (pinfunction "1_P$2") (pintype "passive"))
    )
    (net (code "116") (name "/19_1439385741") (class "Default")
      (node (ref "JP1160") (pin "P$2") (pinfunction "1_P$2") (pintype "passive"))
      (node (ref "JP53") (pin "1") (pinfunction "1_1") (pintype "passive"))
    )
    (net (code "117") (name "/19_1439385772") (class "Default")
      (node (ref "JP134") (pin "1") (pinfunction "1_1") (pintype "passive"))
      (node (ref "JP920") (pin "P$2") (pinfunction "1_P$2") (pintype "passive"))
    )
    (net (code "118") (name "/19_1439385798") (class "Default")
      (node (ref "JP1040") (pin "P$2") (pinfunction "1_P$2") (pintype "passive"))
      (node (ref "JP99") (pin "1") (pinfunction "1_1") (pintype "passive"))
    )
    (net (code "119") (name "/19_1439385823") (class "Default")
      (node (ref "JP1180") (pin "P$2") (pinfunction "1_P$2") (pintype "passive"))
      (node (ref "JP56") (pin "1") (pinfunction "1_1") (pintype "passive"))
    )
    (net (code "120") (name "/19_1439385849") (class "Default")
      (node (ref "JP1100") (pin "P$2") (pinfunction "1_P$2") (pintype "passive"))
      (node (ref "JP148") (pin "1") (pinfunction "1_1") (pintype "passive"))
    )
    (net (code "121") (name "/20_1439385713") (class "Default")
      (node (ref "JP121") (pin "1") (pinfunction "1_1") (pintype "passive"))
      (node (ref "JP981") (pin "P$2") (pinfunction "1_P$2") (pintype "passive"))
    )
    (net (code "122") (name "/20_1439385741") (class "Default")
      (node (ref "JP1181") (pin "P$2") (pinfunction "1_P$2") (pintype "passive"))
      (node (ref "JP294") (pin "1") (pinfunction "1_1") (pintype "passive"))
    )
    (net (code "123") (name "/20_1439385772") (class "Default")
      (node (ref "JP153") (pin "1") (pinfunction "1_1") (pintype "passive"))
      (node (ref "JP921") (pin "P$2") (pinfunction "1_P$2") (pintype "passive"))
    )
    (net (code "124") (name "/20_1439385798") (class "Default")
      (node (ref "JP1041") (pin "P$2") (pinfunction "1_P$2") (pintype "passive"))
      (node (ref "JP130") (pin "1") (pinfunction "1_1") (pintype "passive"))
    )
    (net (code "125") (name "/20_1439385823") (class "Default")
      (node (ref "JP1191") (pin "P$2") (pinfunction "1_P$2") (pintype "passive"))
      (node (ref "JP296") (pin "1") (pinfunction "1_1") (pintype "passive"))
    )
    (net (code "126") (name "/20_1439385849") (class "Default")
      (node (ref "JP1101") (pin "P$2") (pinfunction "1_P$2") (pintype "passive"))
      (node (ref "JP137") (pin "1") (pinfunction "1_1") (pintype "passive"))
    )
    (net (code "127") (name "/21_1439385713") (class "Default")
      (node (ref "JP102") (pin "1") (pinfunction "1_1") (pintype "passive"))
      (node (ref "JP982") (pin "P$2") (pinfunction "1_P$2") (pintype "passive"))
    )
    (net (code "128") (name "/21_1439385741") (class "Default")
      (node (ref "JP1182") (pin "P$2") (pinfunction "1_P$2") (pintype "passive"))
      (node (ref "JP284") (pin "1") (pinfunction "1_1") (pintype "passive"))
    )
    (net (code "129") (name "/21_1439385772") (class "Default")
      (node (ref "JP144") (pin "1") (pinfunction "1_1") (pintype "passive"))
      (node (ref "JP922") (pin "P$2") (pinfunction "1_P$2") (pintype "passive"))
    )
    (net (code "130") (name "/21_1439385798") (class "Default")
      (node (ref "JP1042") (pin "P$2") (pinfunction "1_P$2") (pintype "passive"))
      (node (ref "JP109") (pin "1") (pinfunction "1_1") (pintype "passive"))
    )
    (net (code "131") (name "/21_1439385823") (class "Default")
      (node (ref "JP1192") (pin "P$2") (pinfunction "1_P$2") (pintype "passive"))
      (node (ref "JP297") (pin "1") (pinfunction "1_1") (pintype "passive"))
    )
    (net (code "132") (name "/21_1439385849") (class "Default")
      (node (ref "JP1102") (pin "P$2") (pinfunction "1_P$2") (pintype "passive"))
      (node (ref "JP158") (pin "1") (pinfunction "1_1") (pintype "passive"))
    )
    (net (code "133") (name "/22_1439385713") (class "Default")
      (node (ref "JP131") (pin "1") (pinfunction "1_1") (pintype "passive"))
      (node (ref "JP983") (pin "P$2") (pinfunction "1_P$2") (pintype "passive"))
    )
    (net (code "134") (name "/22_1439385741") (class "Default")
      (node (ref "JP1183") (pin "P$2") (pinfunction "1_P$2") (pintype "passive"))
      (node (ref "JP295") (pin "1") (pinfunction "1_1") (pintype "passive"))
    )
    (net (code "135") (name "/22_1439385772") (class "Default")
      (node (ref "JP163") (pin "1") (pinfunction "1_1") (pintype "passive"))
      (node (ref "JP923") (pin "P$2") (pinfunction "1_P$2") (pintype "passive"))
    )
    (net (code "136") (name "/22_1439385798") (class "Default")
      (node (ref "JP1043") (pin "P$2") (pinfunction "1_P$2") (pintype "passive"))
      (node (ref "JP140") (pin "1") (pinfunction "1_1") (pintype "passive"))
    )
    (net (code "137") (name "/22_1439385823") (class "Default")
      (node (ref "JP1193") (pin "P$2") (pinfunction "1_P$2") (pintype "passive"))
      (node (ref "JP287") (pin "1") (pinfunction "1_1") (pintype "passive"))
    )
    (net (code "138") (name "/22_1439385849") (class "Default")
      (node (ref "JP1103") (pin "P$2") (pinfunction "1_P$2") (pintype "passive"))
      (node (ref "JP147") (pin "1") (pinfunction "1_1") (pintype "passive"))
    )
    (net (code "139") (name "/23_1439385713") (class "Default")
      (node (ref "JP112") (pin "1") (pinfunction "1_1") (pintype "passive"))
      (node (ref "JP984") (pin "P$2") (pinfunction "1_P$2") (pintype "passive"))
    )
    (net (code "140") (name "/23_1439385741") (class "Default")
      (node (ref "JP1184") (pin "P$2") (pinfunction "1_P$2") (pintype "passive"))
      (node (ref "JP285") (pin "1") (pinfunction "1_1") (pintype "passive"))
    )
    (net (code "141") (name "/23_1439385772") (class "Default")
      (node (ref "JP154") (pin "1") (pinfunction "1_1") (pintype "passive"))
      (node (ref "JP924") (pin "P$2") (pinfunction "1_P$2") (pintype "passive"))
    )
    (net (code "142") (name "/23_1439385798") (class "Default")
      (node (ref "JP1044") (pin "P$2") (pinfunction "1_P$2") (pintype "passive"))
      (node (ref "JP119") (pin "1") (pinfunction "1_1") (pintype "passive"))
    )
    (net (code "143") (name "/23_1439385823") (class "Default")
      (node (ref "JP1194") (pin "P$2") (pinfunction "1_P$2") (pintype "passive"))
      (node (ref "JP286") (pin "1") (pinfunction "1_1") (pintype "passive"))
    )
    (net (code "144") (name "/23_1439385849") (class "Default")
      (node (ref "JP1104") (pin "P$2") (pinfunction "1_P$2") (pintype "passive"))
      (node (ref "JP168") (pin "1") (pinfunction "1_1") (pintype "passive"))
    )
    (net (code "145") (name "/24_1439385713") (class "Default")
      (node (ref "JP141") (pin "1") (pinfunction "1_1") (pintype "passive"))
      (node (ref "JP985") (pin "P$2") (pinfunction "1_P$2") (pintype "passive"))
    )
    (net (code "146") (name "/24_1439385741") (class "Default")
      (node (ref "JP1185") (pin "P$2") (pinfunction "1_P$2") (pintype "passive"))
      (node (ref "JP273") (pin "1") (pinfunction "1_1") (pintype "passive"))
    )
    (net (code "147") (name "/24_1439385772") (class "Default")
      (node (ref "JP173") (pin "1") (pinfunction "1_1") (pintype "passive"))
      (node (ref "JP925") (pin "P$2") (pinfunction "1_P$2") (pintype "passive"))
    )
    (net (code "148") (name "/24_1439385798") (class "Default")
      (node (ref "JP1045") (pin "P$2") (pinfunction "1_P$2") (pintype "passive"))
      (node (ref "JP150") (pin "1") (pinfunction "1_1") (pintype "passive"))
    )
    (net (code "149") (name "/24_1439385823") (class "Default")
      (node (ref "JP1195") (pin "P$2") (pinfunction "1_P$2") (pintype "passive"))
      (node (ref "JP278") (pin "1") (pinfunction "1_1") (pintype "passive"))
    )
    (net (code "150") (name "/24_1439385849") (class "Default")
      (node (ref "JP1105") (pin "P$2") (pinfunction "1_P$2") (pintype "passive"))
      (node (ref "JP157") (pin "1") (pinfunction "1_1") (pintype "passive"))
    )
    (net (code "151") (name "/25_1439385713") (class "Default")
      (node (ref "JP122") (pin "1") (pinfunction "1_1") (pintype "passive"))
      (node (ref "JP986") (pin "P$2") (pinfunction "1_P$2") (pintype "passive"))
    )
    (net (code "152") (name "/25_1439385741") (class "Default")
      (node (ref "JP1186") (pin "P$2") (pinfunction "1_P$2") (pintype "passive"))
      (node (ref "JP274") (pin "1") (pinfunction "1_1") (pintype "passive"))
    )
    (net (code "153") (name "/25_1439385772") (class "Default")
      (node (ref "JP164") (pin "1") (pinfunction "1_1") (pintype "passive"))
      (node (ref "JP926") (pin "P$2") (pinfunction "1_P$2") (pintype "passive"))
    )
    (net (code "154") (name "/25_1439385798") (class "Default")
      (node (ref "JP1046") (pin "P$2") (pinfunction "1_P$2") (pintype "passive"))
      (node (ref "JP129") (pin "1") (pinfunction "1_1") (pintype "passive"))
    )
    (net (code "155") (name "/25_1439385823") (class "Default")
      (node (ref "JP1196") (pin "P$2") (pinfunction "1_P$2") (pintype "passive"))
      (node (ref "JP277") (pin "1") (pinfunction "1_1") (pintype "passive"))
    )
    (net (code "156") (name "/25_1439385849") (class "Default")
      (node (ref "JP1106") (pin "P$2") (pinfunction "1_P$2") (pintype "passive"))
      (node (ref "JP178") (pin "1") (pinfunction "1_1") (pintype "passive"))
    )
    (net (code "157") (name "/26_1439385713") (class "Default")
      (node (ref "JP151") (pin "1") (pinfunction "1_1") (pintype "passive"))
      (node (ref "JP987") (pin "P$2") (pinfunction "1_P$2") (pintype "passive"))
    )
    (net (code "158") (name "/26_1439385741") (class "Default")
      (node (ref "JP1187") (pin "P$2") (pinfunction "1_P$2") (pintype "passive"))
      (node (ref "JP275") (pin "1") (pinfunction "1_1") (pintype "passive"))
    )
    (net (code "159") (name "/26_1439385772") (class "Default")
      (node (ref "JP183") (pin "1") (pinfunction "1_1") (pintype "passive"))
      (node (ref "JP927") (pin "P$2") (pinfunction "1_P$2") (pintype "passive"))
    )
    (net (code "160") (name "/26_1439385798") (class "Default")
      (node (ref "JP1047") (pin "P$2") (pinfunction "1_P$2") (pintype "passive"))
      (node (ref "JP160") (pin "1") (pinfunction "1_1") (pintype "passive"))
    )
    (net (code "161") (name "/26_1439385823") (class "Default")
      (node (ref "JP1197") (pin "P$2") (pinfunction "1_P$2") (pintype "passive"))
      (node (ref "JP276") (pin "1") (pinfunction "1_1") (pintype "passive"))
    )
    (net (code "162") (name "/26_1439385849") (class "Default")
      (node (ref "JP1107") (pin "P$2") (pinfunction "1_P$2") (pintype "passive"))
      (node (ref "JP167") (pin "1") (pinfunction "1_1") (pintype "passive"))
    )
    (net (code "163") (name "/27_1439385713") (class "Default")
      (node (ref "JP132") (pin "1") (pinfunction "1_1") (pintype "passive"))
      (node (ref "JP988") (pin "P$2") (pinfunction "1_P$2") (pintype "passive"))
    )
    (net (code "164") (name "/27_1439385741") (class "Default")
      (node (ref "JP1188") (pin "P$2") (pinfunction "1_P$2") (pintype "passive"))
      (node (ref "JP264") (pin "1") (pinfunction "1_1") (pintype "passive"))
    )
    (net (code "165") (name "/27_1439385772") (class "Default")
      (node (ref "JP174") (pin "1") (pinfunction "1_1") (pintype "passive"))
      (node (ref "JP928") (pin "P$2") (pinfunction "1_P$2") (pintype "passive"))
    )
    (net (code "166") (name "/27_1439385798") (class "Default")
      (node (ref "JP1048") (pin "P$2") (pinfunction "1_P$2") (pintype "passive"))
      (node (ref "JP139") (pin "1") (pinfunction "1_1") (pintype "passive"))
    )
    (net (code "167") (name "/27_1439385823") (class "Default")
      (node (ref "JP1198") (pin "P$2") (pinfunction "1_P$2") (pintype "passive"))
      (node (ref "JP268") (pin "1") (pinfunction "1_1") (pintype "passive"))
    )
    (net (code "168") (name "/27_1439385849") (class "Default")
      (node (ref "JP1108") (pin "P$2") (pinfunction "1_P$2") (pintype "passive"))
      (node (ref "JP188") (pin "1") (pinfunction "1_1") (pintype "passive"))
    )
    (net (code "169") (name "/28_1439385713") (class "Default")
      (node (ref "JP161") (pin "1") (pinfunction "1_1") (pintype "passive"))
      (node (ref "JP989") (pin "P$2") (pinfunction "1_P$2") (pintype "passive"))
    )
    (net (code "170") (name "/28_1439385741") (class "Default")
      (node (ref "JP1189") (pin "P$2") (pinfunction "1_P$2") (pintype "passive"))
      (node (ref "JP265") (pin "1") (pinfunction "1_1") (pintype "passive"))
    )
    (net (code "171") (name "/28_1439385772") (class "Default")
      (node (ref "JP193") (pin "1") (pinfunction "1_1") (pintype "passive"))
      (node (ref "JP929") (pin "P$2") (pinfunction "1_P$2") (pintype "passive"))
    )
    (net (code "172") (name "/28_1439385798") (class "Default")
      (node (ref "JP1049") (pin "P$2") (pinfunction "1_P$2") (pintype "passive"))
      (node (ref "JP170") (pin "1") (pinfunction "1_1") (pintype "passive"))
    )
    (net (code "173") (name "/28_1439385823") (class "Default")
      (node (ref "JP1199") (pin "P$2") (pinfunction "1_P$2") (pintype "passive"))
      (node (ref "JP267") (pin "1") (pinfunction "1_1") (pintype "passive"))
    )
    (net (code "174") (name "/28_1439385849") (class "Default")
      (node (ref "JP1109") (pin "P$2") (pinfunction "1_P$2") (pintype "passive"))
      (node (ref "JP177") (pin "1") (pinfunction "1_1") (pintype "passive"))
    )
    (net (code "175") (name "/29_1439385713") (class "Default")
      (node (ref "JP142") (pin "1") (pinfunction "1_1") (pintype "passive"))
      (node (ref "JP990") (pin "P$2") (pinfunction "1_P$2") (pintype "passive"))
    )
    (net (code "176") (name "/29_1439385741") (class "Default")
      (node (ref "JP1190") (pin "P$2") (pinfunction "1_P$2") (pintype "passive"))
      (node (ref "JP263") (pin "1") (pinfunction "1_1") (pintype "passive"))
    )
    (net (code "177") (name "/29_1439385772") (class "Default")
      (node (ref "JP184") (pin "1") (pinfunction "1_1") (pintype "passive"))
      (node (ref "JP930") (pin "P$2") (pinfunction "1_P$2") (pintype "passive"))
    )
    (net (code "178") (name "/29_1439385798") (class "Default")
      (node (ref "JP1050") (pin "P$2") (pinfunction "1_P$2") (pintype "passive"))
      (node (ref "JP149") (pin "1") (pinfunction "1_1") (pintype "passive"))
    )
    (net (code "179") (name "/29_1439385823") (class "Default")
      (node (ref "JP1200") (pin "P$2") (pinfunction "1_P$2") (pintype "passive"))
      (node (ref "JP258") (pin "1") (pinfunction "1_1") (pintype "passive"))
    )
    (net (code "180") (name "/29_1439385849") (class "Default")
      (node (ref "JP1110") (pin "P$2") (pinfunction "1_P$2") (pintype "passive"))
      (node (ref "JP198") (pin "1") (pinfunction "1_1") (pintype "passive"))
    )
    (net (code "181") (name "/30_1439385713") (class "Default")
      (node (ref "JP171") (pin "1") (pinfunction "1_1") (pintype "passive"))
      (node (ref "JP991") (pin "P$2") (pinfunction "1_P$2") (pintype "passive"))
    )
    (net (code "182") (name "/30_1439385772") (class "Default")
      (node (ref "JP203") (pin "1") (pinfunction "1_1") (pintype "passive"))
      (node (ref "JP931") (pin "P$2") (pinfunction "1_P$2") (pintype "passive"))
    )
    (net (code "183") (name "/30_1439385798") (class "Default")
      (node (ref "JP1051") (pin "P$2") (pinfunction "1_P$2") (pintype "passive"))
      (node (ref "JP180") (pin "1") (pinfunction "1_1") (pintype "passive"))
    )
    (net (code "184") (name "/30_1439385849") (class "Default")
      (node (ref "JP1111") (pin "P$2") (pinfunction "1_P$2") (pintype "passive"))
      (node (ref "JP187") (pin "1") (pinfunction "1_1") (pintype "passive"))
    )
    (net (code "185") (name "/31_1439385713") (class "Default")
      (node (ref "JP152") (pin "1") (pinfunction "1_1") (pintype "passive"))
      (node (ref "JP992") (pin "P$2") (pinfunction "1_P$2") (pintype "passive"))
    )
    (net (code "186") (name "/31_1439385772") (class "Default")
      (node (ref "JP194") (pin "1") (pinfunction "1_1") (pintype "passive"))
      (node (ref "JP932") (pin "P$2") (pinfunction "1_P$2") (pintype "passive"))
    )
    (net (code "187") (name "/31_1439385798") (class "Default")
      (node (ref "JP1052") (pin "P$2") (pinfunction "1_P$2") (pintype "passive"))
      (node (ref "JP159") (pin "1") (pinfunction "1_1") (pintype "passive"))
    )
    (net (code "188") (name "/31_1439385849") (class "Default")
      (node (ref "JP1112") (pin "P$2") (pinfunction "1_P$2") (pintype "passive"))
      (node (ref "JP208") (pin "1") (pinfunction "1_1") (pintype "passive"))
    )
    (net (code "189") (name "/32_1439385713") (class "Default")
      (node (ref "JP181") (pin "1") (pinfunction "1_1") (pintype "passive"))
      (node (ref "JP993") (pin "P$2") (pinfunction "1_P$2") (pintype "passive"))
    )
    (net (code "190") (name "/32_1439385772") (class "Default")
      (node (ref "JP213") (pin "1") (pinfunction "1_1") (pintype "passive"))
      (node (ref "JP933") (pin "P$2") (pinfunction "1_P$2") (pintype "passive"))
    )
    (net (code "191") (name "/32_1439385798") (class "Default")
      (node (ref "JP1053") (pin "P$2") (pinfunction "1_P$2") (pintype "passive"))
      (node (ref "JP190") (pin "1") (pinfunction "1_1") (pintype "passive"))
    )
    (net (code "192") (name "/32_1439385849") (class "Default")
      (node (ref "JP1113") (pin "P$2") (pinfunction "1_P$2") (pintype "passive"))
      (node (ref "JP197") (pin "1") (pinfunction "1_1") (pintype "passive"))
    )
    (net (code "193") (name "/33_1439385713") (class "Default")
      (node (ref "JP162") (pin "1") (pinfunction "1_1") (pintype "passive"))
      (node (ref "JP994") (pin "P$2") (pinfunction "1_P$2") (pintype "passive"))
    )
    (net (code "194") (name "/33_1439385772") (class "Default")
      (node (ref "JP204") (pin "1") (pinfunction "1_1") (pintype "passive"))
      (node (ref "JP934") (pin "P$2") (pinfunction "1_P$2") (pintype "passive"))
    )
    (net (code "195") (name "/33_1439385798") (class "Default")
      (node (ref "JP1054") (pin "P$2") (pinfunction "1_P$2") (pintype "passive"))
      (node (ref "JP169") (pin "1") (pinfunction "1_1") (pintype "passive"))
    )
    (net (code "196") (name "/33_1439385849") (class "Default")
      (node (ref "JP1114") (pin "P$2") (pinfunction "1_P$2") (pintype "passive"))
      (node (ref "JP218") (pin "1") (pinfunction "1_1") (pintype "passive"))
    )
    (net (code "197") (name "/34_1439385713") (class "Default")
      (node (ref "JP191") (pin "1") (pinfunction "1_1") (pintype "passive"))
      (node (ref "JP995") (pin "P$2") (pinfunction "1_P$2") (pintype "passive"))
    )
    (net (code "198") (name "/34_1439385772") (class "Default")
      (node (ref "JP223") (pin "1") (pinfunction "1_1") (pintype "passive"))
      (node (ref "JP935") (pin "P$2") (pinfunction "1_P$2") (pintype "passive"))
    )
    (net (code "199") (name "/34_1439385798") (class "Default")
      (node (ref "JP1055") (pin "P$2") (pinfunction "1_P$2") (pintype "passive"))
      (node (ref "JP200") (pin "1") (pinfunction "1_1") (pintype "passive"))
    )
    (net (code "200") (name "/34_1439385849") (class "Default")
      (node (ref "JP1115") (pin "P$2") (pinfunction "1_P$2") (pintype "passive"))
      (node (ref "JP207") (pin "1") (pinfunction "1_1") (pintype "passive"))
    )
    (net (code "201") (name "/35_1439385713") (class "Default")
      (node (ref "JP172") (pin "1") (pinfunction "1_1") (pintype "passive"))
      (node (ref "JP996") (pin "P$2") (pinfunction "1_P$2") (pintype "passive"))
    )
    (net (code "202") (name "/35_1439385772") (class "Default")
      (node (ref "JP214") (pin "1") (pinfunction "1_1") (pintype "passive"))
      (node (ref "JP936") (pin "P$2") (pinfunction "1_P$2") (pintype "passive"))
    )
    (net (code "203") (name "/35_1439385798") (class "Default")
      (node (ref "JP1056") (pin "P$2") (pinfunction "1_P$2") (pintype "passive"))
      (node (ref "JP179") (pin "1") (pinfunction "1_1") (pintype "passive"))
    )
    (net (code "204") (name "/35_1439385849") (class "Default")
      (node (ref "JP1116") (pin "P$2") (pinfunction "1_P$2") (pintype "passive"))
      (node (ref "JP228") (pin "1") (pinfunction "1_1") (pintype "passive"))
    )
    (net (code "205") (name "/36_1439385713") (class "Default")
      (node (ref "JP201") (pin "1") (pinfunction "1_1") (pintype "passive"))
      (node (ref "JP997") (pin "P$2") (pinfunction "1_P$2") (pintype "passive"))
    )
    (net (code "206") (name "/36_1439385772") (class "Default")
      (node (ref "JP233") (pin "1") (pinfunction "1_1") (pintype "passive"))
      (node (ref "JP937") (pin "P$2") (pinfunction "1_P$2") (pintype "passive"))
    )
    (net (code "207") (name "/36_1439385798") (class "Default")
      (node (ref "JP1057") (pin "P$2") (pinfunction "1_P$2") (pintype "passive"))
      (node (ref "JP210") (pin "1") (pinfunction "1_1") (pintype "passive"))
    )
    (net (code "208") (name "/36_1439385849") (class "Default")
      (node (ref "JP1117") (pin "P$2") (pinfunction "1_P$2") (pintype "passive"))
      (node (ref "JP217") (pin "1") (pinfunction "1_1") (pintype "passive"))
    )
    (net (code "209") (name "/37_1439385713") (class "Default")
      (node (ref "JP182") (pin "1") (pinfunction "1_1") (pintype "passive"))
      (node (ref "JP998") (pin "P$2") (pinfunction "1_P$2") (pintype "passive"))
    )
    (net (code "210") (name "/37_1439385772") (class "Default")
      (node (ref "JP224") (pin "1") (pinfunction "1_1") (pintype "passive"))
      (node (ref "JP938") (pin "P$2") (pinfunction "1_P$2") (pintype "passive"))
    )
    (net (code "211") (name "/37_1439385798") (class "Default")
      (node (ref "JP1058") (pin "P$2") (pinfunction "1_P$2") (pintype "passive"))
      (node (ref "JP189") (pin "1") (pinfunction "1_1") (pintype "passive"))
    )
    (net (code "212") (name "/37_1439385849") (class "Default")
      (node (ref "JP1118") (pin "P$2") (pinfunction "1_P$2") (pintype "passive"))
      (node (ref "JP238") (pin "1") (pinfunction "1_1") (pintype "passive"))
    )
    (net (code "213") (name "/38_1439385713") (class "Default")
      (node (ref "JP211") (pin "1") (pinfunction "1_1") (pintype "passive"))
      (node (ref "JP999") (pin "P$2") (pinfunction "1_P$2") (pintype "passive"))
    )
    (net (code "214") (name "/38_1439385772") (class "Default")
      (node (ref "JP243") (pin "1") (pinfunction "1_1") (pintype "passive"))
      (node (ref "JP939") (pin "P$2") (pinfunction "1_P$2") (pintype "passive"))
    )
    (net (code "215") (name "/38_1439385798") (class "Default")
      (node (ref "JP1059") (pin "P$2") (pinfunction "1_P$2") (pintype "passive"))
      (node (ref "JP220") (pin "1") (pinfunction "1_1") (pintype "passive"))
    )
    (net (code "216") (name "/38_1439385849") (class "Default")
      (node (ref "JP1119") (pin "P$2") (pinfunction "1_P$2") (pintype "passive"))
      (node (ref "JP227") (pin "1") (pinfunction "1_1") (pintype "passive"))
    )
    (net (code "217") (name "/39_1439385713") (class "Default")
      (node (ref "JP1000") (pin "P$2") (pinfunction "1_P$2") (pintype "passive"))
      (node (ref "JP192") (pin "1") (pinfunction "1_1") (pintype "passive"))
    )
    (net (code "218") (name "/39_1439385772") (class "Default")
      (node (ref "JP234") (pin "1") (pinfunction "1_1") (pintype "passive"))
      (node (ref "JP940") (pin "P$2") (pinfunction "1_P$2") (pintype "passive"))
    )
    (net (code "219") (name "/39_1439385798") (class "Default")
      (node (ref "JP1060") (pin "P$2") (pinfunction "1_P$2") (pintype "passive"))
      (node (ref "JP199") (pin "1") (pinfunction "1_1") (pintype "passive"))
    )
    (net (code "220") (name "/39_1439385849") (class "Default")
      (node (ref "JP1120") (pin "P$2") (pinfunction "1_P$2") (pintype "passive"))
      (node (ref "JP248") (pin "1") (pinfunction "1_1") (pintype "passive"))
    )
    (net (code "221") (name "/40_1439385713") (class "Default")
      (node (ref "JP1001") (pin "P$2") (pinfunction "1_P$2") (pintype "passive"))
      (node (ref "JP221") (pin "1") (pinfunction "1_1") (pintype "passive"))
    )
    (net (code "222") (name "/40_1439385772") (class "Default")
      (node (ref "JP253") (pin "1") (pinfunction "1_1") (pintype "passive"))
      (node (ref "JP941") (pin "P$2") (pinfunction "1_P$2") (pintype "passive"))
    )
    (net (code "223") (name "/40_1439385798") (class "Default")
      (node (ref "JP1061") (pin "P$2") (pinfunction "1_P$2") (pintype "passive"))
      (node (ref "JP230") (pin "1") (pinfunction "1_1") (pintype "passive"))
    )
    (net (code "224") (name "/40_1439385849") (class "Default")
      (node (ref "JP1121") (pin "P$2") (pinfunction "1_P$2") (pintype "passive"))
      (node (ref "JP237") (pin "1") (pinfunction "1_1") (pintype "passive"))
    )
    (net (code "225") (name "/41_1439385713") (class "Default")
      (node (ref "JP1002") (pin "P$2") (pinfunction "1_P$2") (pintype "passive"))
      (node (ref "JP202") (pin "1") (pinfunction "1_1") (pintype "passive"))
    )
    (net (code "226") (name "/41_1439385772") (class "Default")
      (node (ref "JP244") (pin "1") (pinfunction "1_1") (pintype "passive"))
      (node (ref "JP942") (pin "P$2") (pinfunction "1_P$2") (pintype "passive"))
    )
    (net (code "227") (name "/41_1439385798") (class "Default")
      (node (ref "JP1062") (pin "P$2") (pinfunction "1_P$2") (pintype "passive"))
      (node (ref "JP209") (pin "1") (pinfunction "1_1") (pintype "passive"))
    )
    (net (code "228") (name "/41_1439385849") (class "Default")
      (node (ref "JP1122") (pin "P$2") (pinfunction "1_P$2") (pintype "passive"))
      (node (ref "JP247") (pin "1") (pinfunction "1_1") (pintype "passive"))
    )
    (net (code "229") (name "/42_1439385713") (class "Default")
      (node (ref "JP1003") (pin "P$2") (pinfunction "1_P$2") (pintype "passive"))
      (node (ref "JP231") (pin "1") (pinfunction "1_1") (pintype "passive"))
    )
    (net (code "230") (name "/42_1439385772") (class "Default")
      (node (ref "JP215") (pin "1") (pinfunction "1_1") (pintype "passive"))
      (node (ref "JP943") (pin "P$2") (pinfunction "1_P$2") (pintype "passive"))
    )
    (net (code "231") (name "/42_1439385798") (class "Default")
      (node (ref "JP1063") (pin "P$2") (pinfunction "1_P$2") (pintype "passive"))
      (node (ref "JP240") (pin "1") (pinfunction "1_1") (pintype "passive"))
    )
    (net (code "232") (name "/42_1439385849") (class "Default")
      (node (ref "JP1123") (pin "P$2") (pinfunction "1_P$2") (pintype "passive"))
      (node (ref "JP216") (pin "1") (pinfunction "1_1") (pintype "passive"))
    )
    (net (code "233") (name "/43_1439385713") (class "Default")
      (node (ref "JP1004") (pin "P$2") (pinfunction "1_P$2") (pintype "passive"))
      (node (ref "JP212") (pin "1") (pinfunction "1_1") (pintype "passive"))
    )
    (net (code "234") (name "/43_1439385772") (class "Default")
      (node (ref "JP254") (pin "1") (pinfunction "1_1") (pintype "passive"))
      (node (ref "JP944") (pin "P$2") (pinfunction "1_P$2") (pintype "passive"))
    )
    (net (code "235") (name "/43_1439385798") (class "Default")
      (node (ref "JP1064") (pin "P$2") (pinfunction "1_P$2") (pintype "passive"))
      (node (ref "JP219") (pin "1") (pinfunction "1_1") (pintype "passive"))
    )
    (net (code "236") (name "/43_1439385849") (class "Default")
      (node (ref "JP1124") (pin "P$2") (pinfunction "1_P$2") (pintype "passive"))
      (node (ref "JP257") (pin "1") (pinfunction "1_1") (pintype "passive"))
    )
    (net (code "237") (name "/44_1439385713") (class "Default")
      (node (ref "JP1005") (pin "P$2") (pinfunction "1_P$2") (pintype "passive"))
      (node (ref "JP241") (pin "1") (pinfunction "1_1") (pintype "passive"))
    )
    (net (code "238") (name "/44_1439385772") (class "Default")
      (node (ref "JP225") (pin "1") (pinfunction "1_1") (pintype "passive"))
      (node (ref "JP945") (pin "P$2") (pinfunction "1_P$2") (pintype "passive"))
    )
    (net (code "239") (name "/44_1439385798") (class "Default")
      (node (ref "JP1065") (pin "P$2") (pinfunction "1_P$2") (pintype "passive"))
      (node (ref "JP250") (pin "1") (pinfunction "1_1") (pintype "passive"))
    )
    (net (code "240") (name "/44_1439385849") (class "Default")
      (node (ref "JP1125") (pin "P$2") (pinfunction "1_P$2") (pintype "passive"))
      (node (ref "JP226") (pin "1") (pinfunction "1_1") (pintype "passive"))
    )
    (net (code "241") (name "/45_1439385713") (class "Default")
      (node (ref "JP1006") (pin "P$2") (pinfunction "1_P$2") (pintype "passive"))
      (node (ref "JP222") (pin "1") (pinfunction "1_1") (pintype "passive"))
    )
    (net (code "242") (name "/45_1439385772") (class "Default")
      (node (ref "JP235") (pin "1") (pinfunction "1_1") (pintype "passive"))
      (node (ref "JP946") (pin "P$2") (pinfunction "1_P$2") (pintype "passive"))
    )
    (net (code "243") (name "/45_1439385798") (class "Default")
      (node (ref "JP1066") (pin "P$2") (pinfunction "1_P$2") (pintype "passive"))
      (node (ref "JP229") (pin "1") (pinfunction "1_1") (pintype "passive"))
    )
    (net (code "244") (name "/45_1439385849") (class "Default")
      (node (ref "JP1126") (pin "P$2") (pinfunction "1_P$2") (pintype "passive"))
      (node (ref "JP236") (pin "1") (pinfunction "1_1") (pintype "passive"))
    )
    (net (code "245") (name "/46_1439385713") (class "Default")
      (node (ref "JP1007") (pin "P$2") (pinfunction "1_P$2") (pintype "passive"))
      (node (ref "JP251") (pin "1") (pinfunction "1_1") (pintype "passive"))
    )
    (net (code "246") (name "/46_1439385772") (class "Default")
      (node (ref "JP245") (pin "1") (pinfunction "1_1") (pintype "passive"))
      (node (ref "JP947") (pin "P$2") (pinfunction "1_P$2") (pintype "passive"))
    )
    (net (code "247") (name "/46_1439385798") (class "Default")
      (node (ref "JP1067") (pin "P$2") (pinfunction "1_P$2") (pintype "passive"))
      (node (ref "JP260") (pin "1") (pinfunction "1_1") (pintype "passive"))
    )
    (net (code "248") (name "/46_1439385849") (class "Default")
      (node (ref "JP1127") (pin "P$2") (pinfunction "1_P$2") (pintype "passive"))
      (node (ref "JP246") (pin "1") (pinfunction "1_1") (pintype "passive"))
    )
    (net (code "249") (name "/47_1439385713") (class "Default")
      (node (ref "JP1008") (pin "P$2") (pinfunction "1_P$2") (pintype "passive"))
      (node (ref "JP232") (pin "1") (pinfunction "1_1") (pintype "passive"))
    )
    (net (code "250") (name "/47_1439385772") (class "Default")
      (node (ref "JP255") (pin "1") (pinfunction "1_1") (pintype "passive"))
      (node (ref "JP948") (pin "P$2") (pinfunction "1_P$2") (pintype "passive"))
    )
    (net (code "251") (name "/47_1439385798") (class "Default")
      (node (ref "JP1068") (pin "P$2") (pinfunction "1_P$2") (pintype "passive"))
      (node (ref "JP239") (pin "1") (pinfunction "1_1") (pintype "passive"))
    )
    (net (code "252") (name "/47_1439385849") (class "Default")
      (node (ref "JP1128") (pin "P$2") (pinfunction "1_P$2") (pintype "passive"))
      (node (ref "JP256") (pin "1") (pinfunction "1_1") (pintype "passive"))
    )
    (net (code "253") (name "/48_1439385713") (class "Default")
      (node (ref "JP1009") (pin "P$2") (pinfunction "1_P$2") (pintype "passive"))
      (node (ref "JP261") (pin "1") (pinfunction "1_1") (pintype "passive"))
    )
    (net (code "254") (name "/48_1439385772") (class "Default")
      (node (ref "JP205") (pin "1") (pinfunction "1_1") (pintype "passive"))
      (node (ref "JP949") (pin "P$2") (pinfunction "1_P$2") (pintype "passive"))
    )
    (net (code "255") (name "/48_1439385798") (class "Default")
      (node (ref "JP1069") (pin "P$2") (pinfunction "1_P$2") (pintype "passive"))
      (node (ref "JP270") (pin "1") (pinfunction "1_1") (pintype "passive"))
    )
    (net (code "256") (name "/48_1439385849") (class "Default")
      (node (ref "JP1129") (pin "P$2") (pinfunction "1_P$2") (pintype "passive"))
      (node (ref "JP266") (pin "1") (pinfunction "1_1") (pintype "passive"))
    )
    (net (code "257") (name "/49_1439385713") (class "Default")
      (node (ref "JP1010") (pin "P$2") (pinfunction "1_P$2") (pintype "passive"))
      (node (ref "JP242") (pin "1") (pinfunction "1_1") (pintype "passive"))
    )
    (net (code "258") (name "/49_1439385772") (class "Default")
      (node (ref "JP195") (pin "1") (pinfunction "1_1") (pintype "passive"))
      (node (ref "JP950") (pin "P$2") (pinfunction "1_P$2") (pintype "passive"))
    )
    (net (code "259") (name "/49_1439385798") (class "Default")
      (node (ref "JP1070") (pin "P$2") (pinfunction "1_P$2") (pintype "passive"))
      (node (ref "JP249") (pin "1") (pinfunction "1_1") (pintype "passive"))
    )
    (net (code "260") (name "/49_1439385849") (class "Default")
      (node (ref "JP1130") (pin "P$2") (pinfunction "1_P$2") (pintype "passive"))
      (node (ref "JP206") (pin "1") (pinfunction "1_1") (pintype "passive"))
    )
    (net (code "261") (name "/50_1439385713") (class "Default")
      (node (ref "JP1011") (pin "P$2") (pinfunction "1_P$2") (pintype "passive"))
      (node (ref "JP271") (pin "1") (pinfunction "1_1") (pintype "passive"))
    )
    (net (code "262") (name "/50_1439385772") (class "Default")
      (node (ref "JP185") (pin "1") (pinfunction "1_1") (pintype "passive"))
      (node (ref "JP951") (pin "P$2") (pinfunction "1_P$2") (pintype "passive"))
    )
    (net (code "263") (name "/50_1439385798") (class "Default")
      (node (ref "JP1071") (pin "P$2") (pinfunction "1_P$2") (pintype "passive"))
      (node (ref "JP280") (pin "1") (pinfunction "1_1") (pintype "passive"))
    )
    (net (code "264") (name "/50_1439385849") (class "Default")
      (node (ref "JP1131") (pin "P$2") (pinfunction "1_P$2") (pintype "passive"))
      (node (ref "JP196") (pin "1") (pinfunction "1_1") (pintype "passive"))
    )
    (net (code "265") (name "/51_1439385713") (class "Default")
      (node (ref "JP1012") (pin "P$2") (pinfunction "1_P$2") (pintype "passive"))
      (node (ref "JP252") (pin "1") (pinfunction "1_1") (pintype "passive"))
    )
    (net (code "266") (name "/51_1439385772") (class "Default")
      (node (ref "JP175") (pin "1") (pinfunction "1_1") (pintype "passive"))
      (node (ref "JP952") (pin "P$2") (pinfunction "1_P$2") (pintype "passive"))
    )
    (net (code "267") (name "/51_1439385798") (class "Default")
      (node (ref "JP1072") (pin "P$2") (pinfunction "1_P$2") (pintype "passive"))
      (node (ref "JP259") (pin "1") (pinfunction "1_1") (pintype "passive"))
    )
    (net (code "268") (name "/51_1439385849") (class "Default")
      (node (ref "JP1132") (pin "P$2") (pinfunction "1_P$2") (pintype "passive"))
      (node (ref "JP186") (pin "1") (pinfunction "1_1") (pintype "passive"))
    )
    (net (code "269") (name "/52_1439385713") (class "Default")
      (node (ref "JP1013") (pin "P$2") (pinfunction "1_P$2") (pintype "passive"))
      (node (ref "JP281") (pin "1") (pinfunction "1_1") (pintype "passive"))
    )
    (net (code "270") (name "/52_1439385772") (class "Default")
      (node (ref "JP165") (pin "1") (pinfunction "1_1") (pintype "passive"))
      (node (ref "JP953") (pin "P$2") (pinfunction "1_P$2") (pintype "passive"))
    )
    (net (code "271") (name "/52_1439385798") (class "Default")
      (node (ref "JP1073") (pin "P$2") (pinfunction "1_P$2") (pintype "passive"))
      (node (ref "JP290") (pin "1") (pinfunction "1_1") (pintype "passive"))
    )
    (net (code "272") (name "/52_1439385849") (class "Default")
      (node (ref "JP1133") (pin "P$2") (pinfunction "1_P$2") (pintype "passive"))
      (node (ref "JP176") (pin "1") (pinfunction "1_1") (pintype "passive"))
    )
    (net (code "273") (name "/53_1439385713") (class "Default")
      (node (ref "JP1014") (pin "P$2") (pinfunction "1_P$2") (pintype "passive"))
      (node (ref "JP262") (pin "1") (pinfunction "1_1") (pintype "passive"))
    )
    (net (code "274") (name "/53_1439385772") (class "Default")
      (node (ref "JP155") (pin "1") (pinfunction "1_1") (pintype "passive"))
      (node (ref "JP954") (pin "P$2") (pinfunction "1_P$2") (pintype "passive"))
    )
    (net (code "275") (name "/53_1439385798") (class "Default")
      (node (ref "JP1074") (pin "P$2") (pinfunction "1_P$2") (pintype "passive"))
      (node (ref "JP269") (pin "1") (pinfunction "1_1") (pintype "passive"))
    )
    (net (code "276") (name "/53_1439385849") (class "Default")
      (node (ref "JP1134") (pin "P$2") (pinfunction "1_P$2") (pintype "passive"))
      (node (ref "JP166") (pin "1") (pinfunction "1_1") (pintype "passive"))
    )
    (net (code "277") (name "/54_1439385713") (class "Default")
      (node (ref "JP1015") (pin "P$2") (pinfunction "1_P$2") (pintype "passive"))
      (node (ref "JP291") (pin "1") (pinfunction "1_1") (pintype "passive"))
    )
    (net (code "278") (name "/54_1439385772") (class "Default")
      (node (ref "JP145") (pin "1") (pinfunction "1_1") (pintype "passive"))
      (node (ref "JP955") (pin "P$2") (pinfunction "1_P$2") (pintype "passive"))
    )
    (net (code "279") (name "/54_1439385798") (class "Default")
      (node (ref "JP1075") (pin "P$2") (pinfunction "1_P$2") (pintype "passive"))
      (node (ref "JP300") (pin "1") (pinfunction "1_1") (pintype "passive"))
    )
    (net (code "280") (name "/54_1439385849") (class "Default")
      (node (ref "JP1135") (pin "P$2") (pinfunction "1_P$2") (pintype "passive"))
      (node (ref "JP156") (pin "1") (pinfunction "1_1") (pintype "passive"))
    )
    (net (code "281") (name "/55_1439385713") (class "Default")
      (node (ref "JP1016") (pin "P$2") (pinfunction "1_P$2") (pintype "passive"))
      (node (ref "JP272") (pin "1") (pinfunction "1_1") (pintype "passive"))
    )
    (net (code "282") (name "/55_1439385772") (class "Default")
      (node (ref "JP135") (pin "1") (pinfunction "1_1") (pintype "passive"))
      (node (ref "JP956") (pin "P$2") (pinfunction "1_P$2") (pintype "passive"))
    )
    (net (code "283") (name "/55_1439385798") (class "Default")
      (node (ref "JP1076") (pin "P$2") (pinfunction "1_P$2") (pintype "passive"))
      (node (ref "JP279") (pin "1") (pinfunction "1_1") (pintype "passive"))
    )
    (net (code "284") (name "/55_1439385849") (class "Default")
      (node (ref "JP1136") (pin "P$2") (pinfunction "1_P$2") (pintype "passive"))
      (node (ref "JP146") (pin "1") (pinfunction "1_1") (pintype "passive"))
    )
    (net (code "285") (name "/56_1439385713") (class "Default")
      (node (ref "JP1017") (pin "P$2") (pinfunction "1_P$2") (pintype "passive"))
      (node (ref "JP282") (pin "1") (pinfunction "1_1") (pintype "passive"))
    )
    (net (code "286") (name "/56_1439385772") (class "Default")
      (node (ref "JP125") (pin "1") (pinfunction "1_1") (pintype "passive"))
      (node (ref "JP957") (pin "P$2") (pinfunction "1_P$2") (pintype "passive"))
    )
    (net (code "287") (name "/56_1439385798") (class "Default")
      (node (ref "JP1077") (pin "P$2") (pinfunction "1_P$2") (pintype "passive"))
      (node (ref "JP289") (pin "1") (pinfunction "1_1") (pintype "passive"))
    )
    (net (code "288") (name "/56_1439385849") (class "Default")
      (node (ref "JP1137") (pin "P$2") (pinfunction "1_P$2") (pintype "passive"))
      (node (ref "JP136") (pin "1") (pinfunction "1_1") (pintype "passive"))
    )
    (net (code "289") (name "/57_1439385713") (class "Default")
      (node (ref "JP1018") (pin "P$2") (pinfunction "1_P$2") (pintype "passive"))
      (node (ref "JP292") (pin "1") (pinfunction "1_1") (pintype "passive"))
    )
    (net (code "290") (name "/57_1439385772") (class "Default")
      (node (ref "JP115") (pin "1") (pinfunction "1_1") (pintype "passive"))
      (node (ref "JP958") (pin "P$2") (pinfunction "1_P$2") (pintype "passive"))
    )
    (net (code "291") (name "/57_1439385798") (class "Default")
      (node (ref "JP1078") (pin "P$2") (pinfunction "1_P$2") (pintype "passive"))
      (node (ref "JP299") (pin "1") (pinfunction "1_1") (pintype "passive"))
    )
    (net (code "292") (name "/57_1439385849") (class "Default")
      (node (ref "JP1138") (pin "P$2") (pinfunction "1_P$2") (pintype "passive"))
      (node (ref "JP126") (pin "1") (pinfunction "1_1") (pintype "passive"))
    )
    (net (code "293") (name "/58_1439385713") (class "Default")
      (node (ref "JP1019") (pin "P$2") (pinfunction "1_P$2") (pintype "passive"))
      (node (ref "JP293") (pin "1") (pinfunction "1_1") (pintype "passive"))
    )
    (net (code "294") (name "/58_1439385772") (class "Default")
      (node (ref "JP105") (pin "1") (pinfunction "1_1") (pintype "passive"))
      (node (ref "JP959") (pin "P$2") (pinfunction "1_P$2") (pintype "passive"))
    )
    (net (code "295") (name "/58_1439385798") (class "Default")
      (node (ref "JP1079") (pin "P$2") (pinfunction "1_P$2") (pintype "passive"))
      (node (ref "JP298") (pin "1") (pinfunction "1_1") (pintype "passive"))
    )
    (net (code "296") (name "/58_1439385849") (class "Default")
      (node (ref "JP1139") (pin "P$2") (pinfunction "1_P$2") (pintype "passive"))
      (node (ref "JP116") (pin "1") (pinfunction "1_1") (pintype "passive"))
    )
    (net (code "297") (name "/59_1439385713") (class "Default")
      (node (ref "JP1020") (pin "P$2") (pinfunction "1_P$2") (pintype "passive"))
      (node (ref "JP283") (pin "1") (pinfunction "1_1") (pintype "passive"))
    )
    (net (code "298") (name "/59_1439385772") (class "Default")
      (node (ref "JP95") (pin "1") (pinfunction "1_1") (pintype "passive"))
      (node (ref "JP960") (pin "P$2") (pinfunction "1_P$2") (pintype "passive"))
    )
    (net (code "299") (name "/59_1439385798") (class "Default")
      (node (ref "JP1080") (pin "P$2") (pinfunction "1_P$2") (pintype "passive"))
      (node (ref "JP288") (pin "1") (pinfunction "1_1") (pintype "passive"))
    )
    (net (code "300") (name "/59_1439385849") (class "Default")
      (node (ref "JP106") (pin "1") (pinfunction "1_1") (pintype "passive"))
      (node (ref "JP1140") (pin "P$2") (pinfunction "1_P$2") (pintype "passive"))
    )
  )
)
